# CERBERUS_2100_EasyEDA_Schematics.net
KiCad netlist of a schematic drawn in EasyEDA
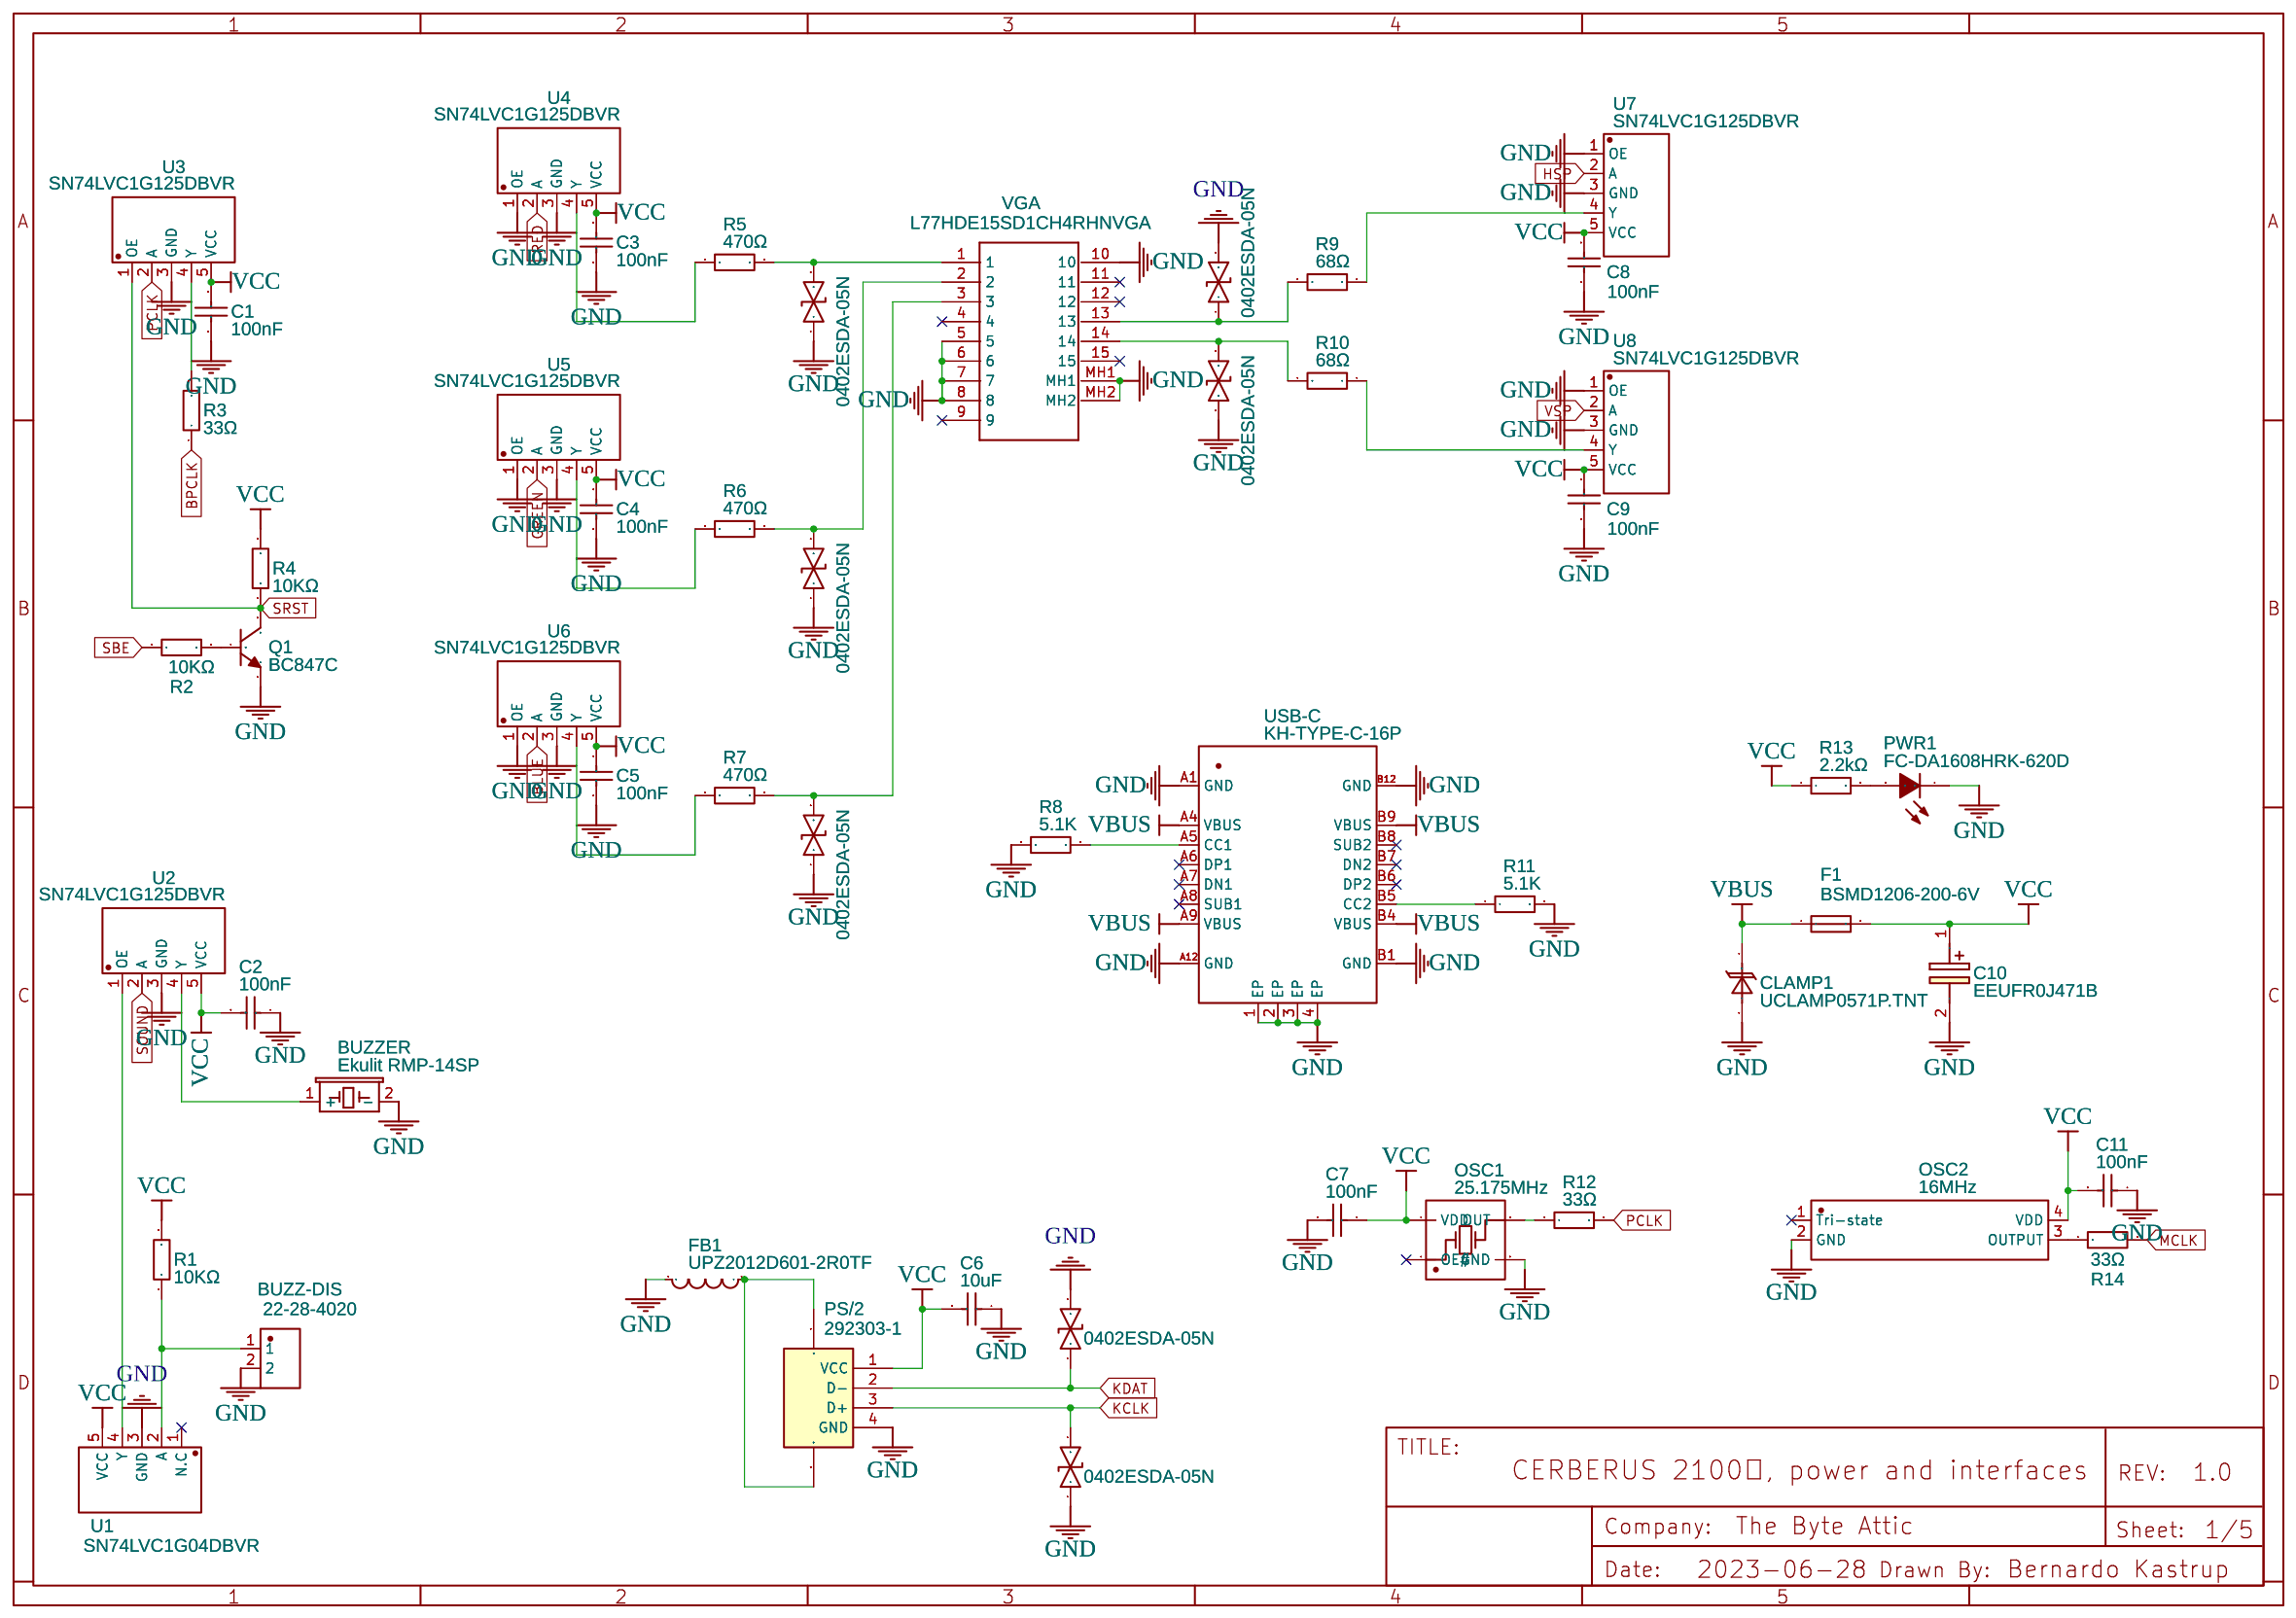
[diagram p0: PSU/IO]
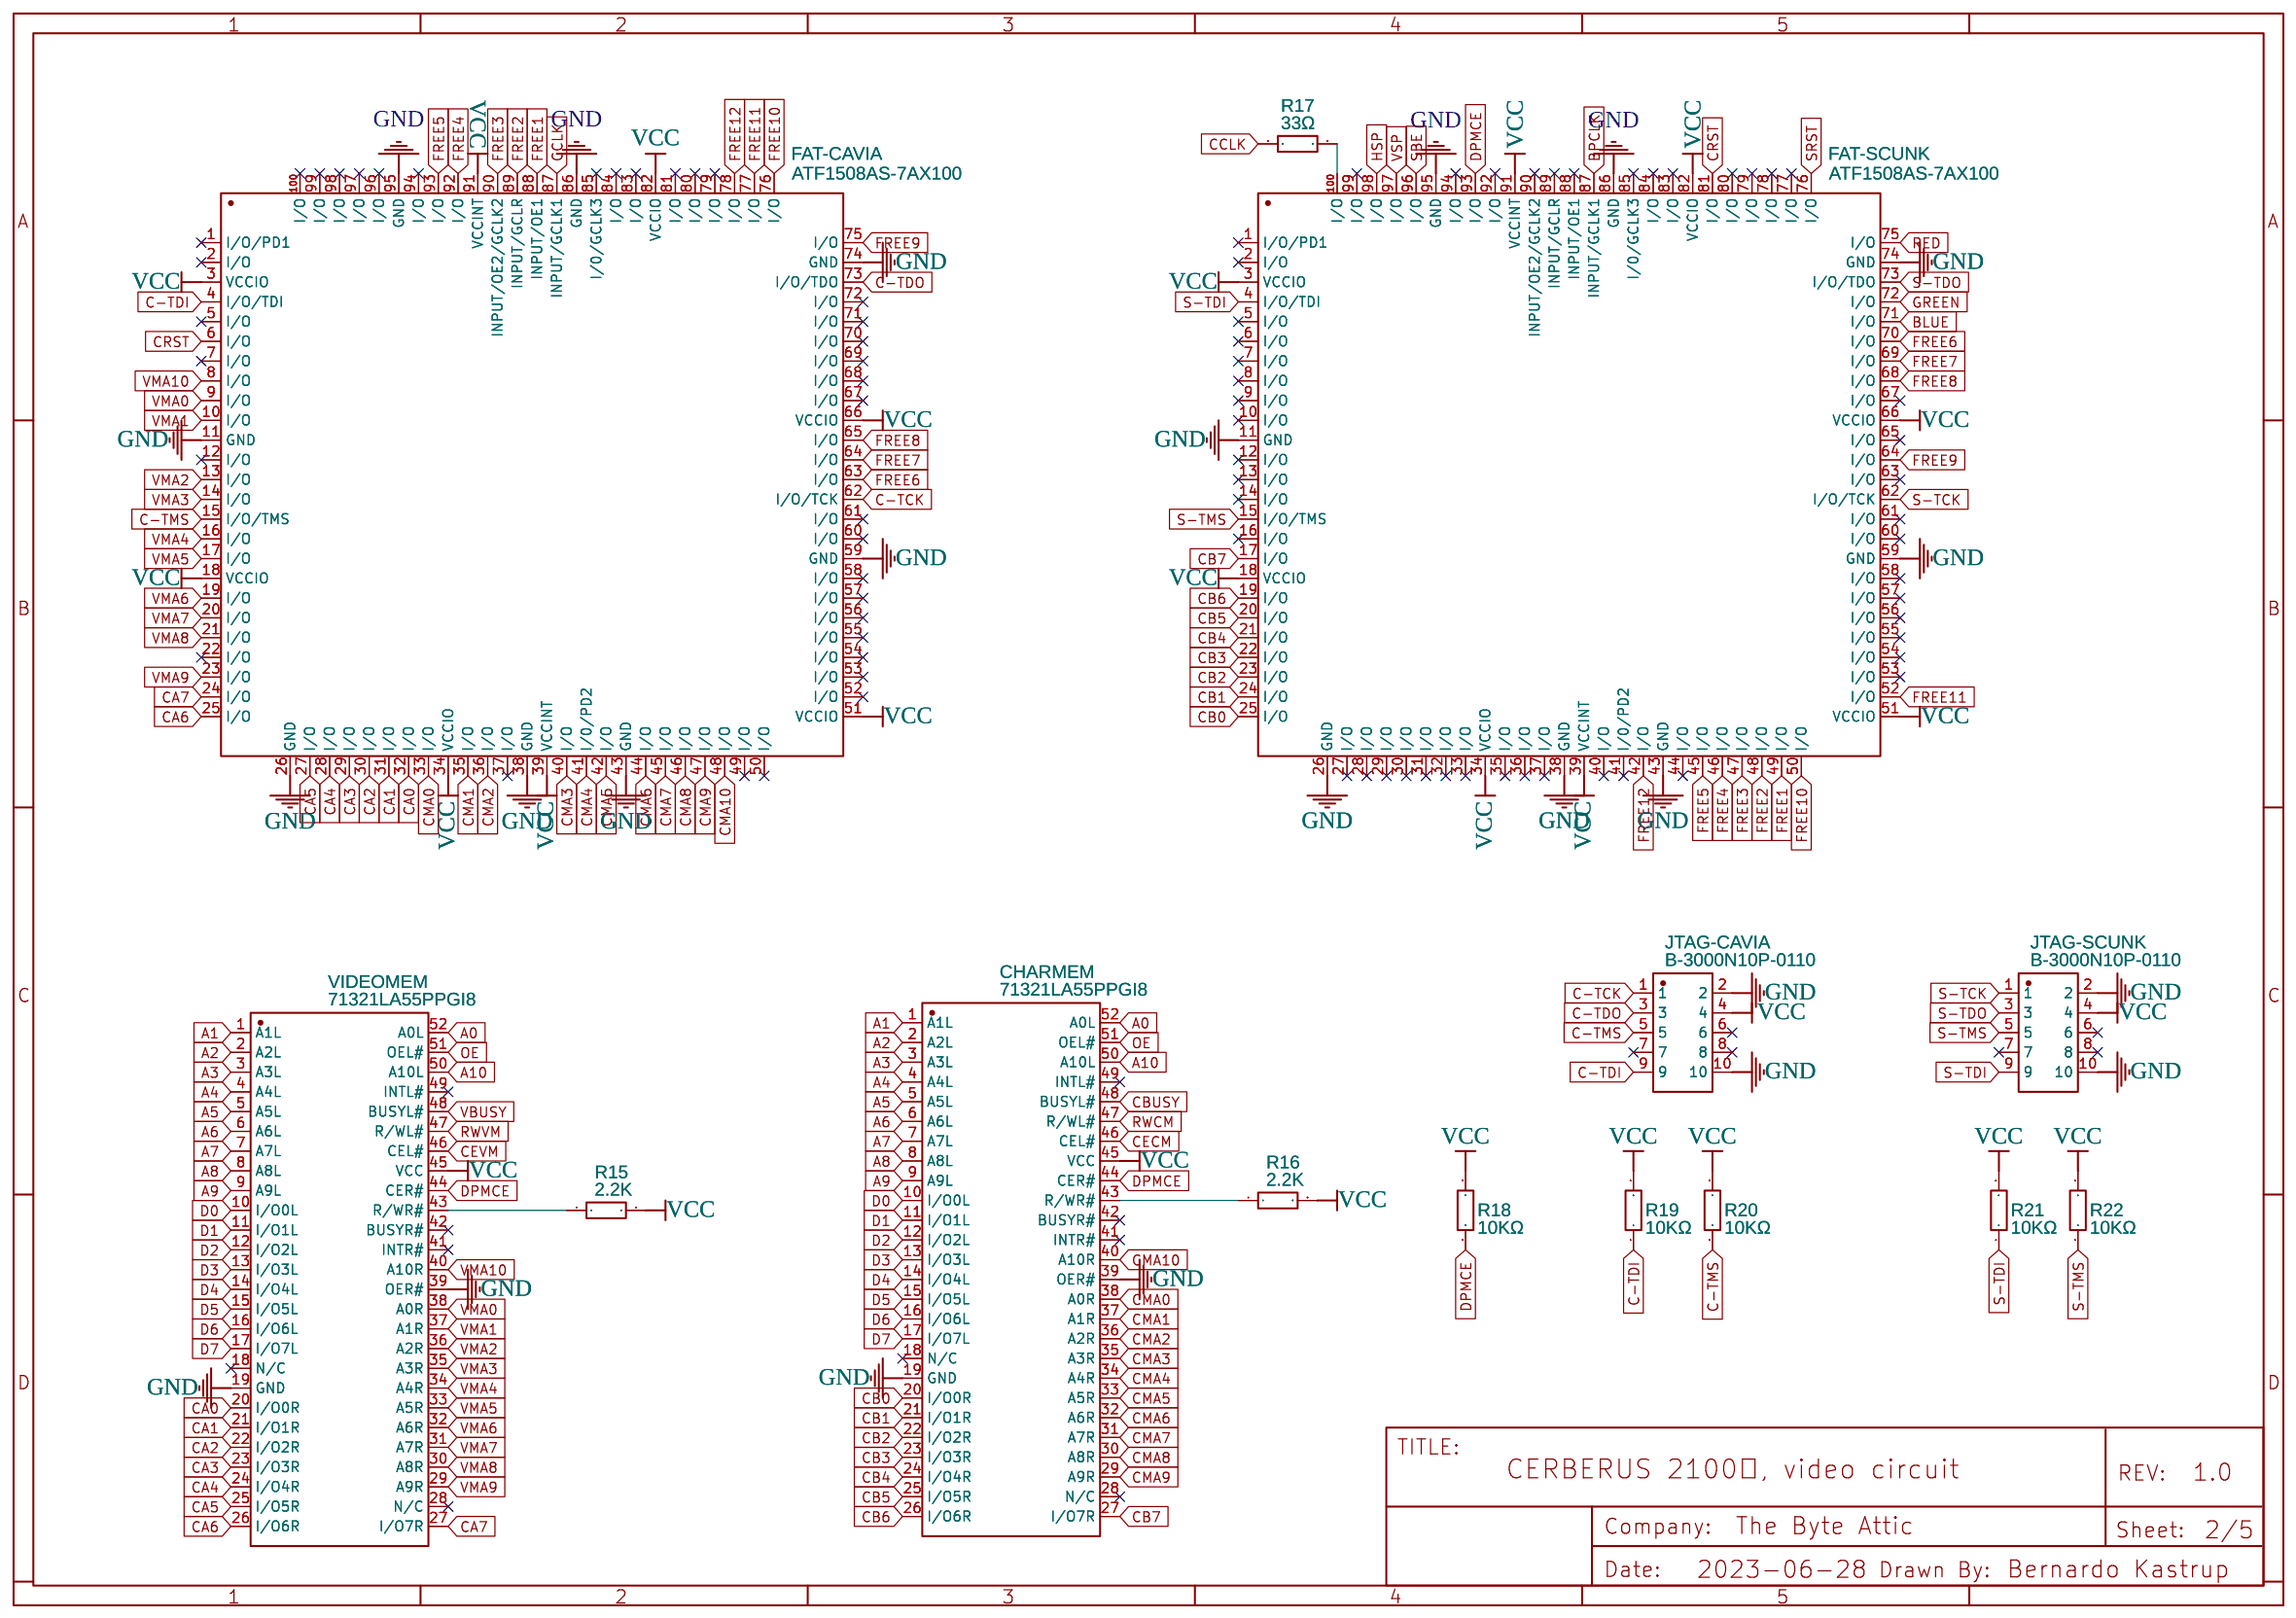
[diagram p1: VIDEO]
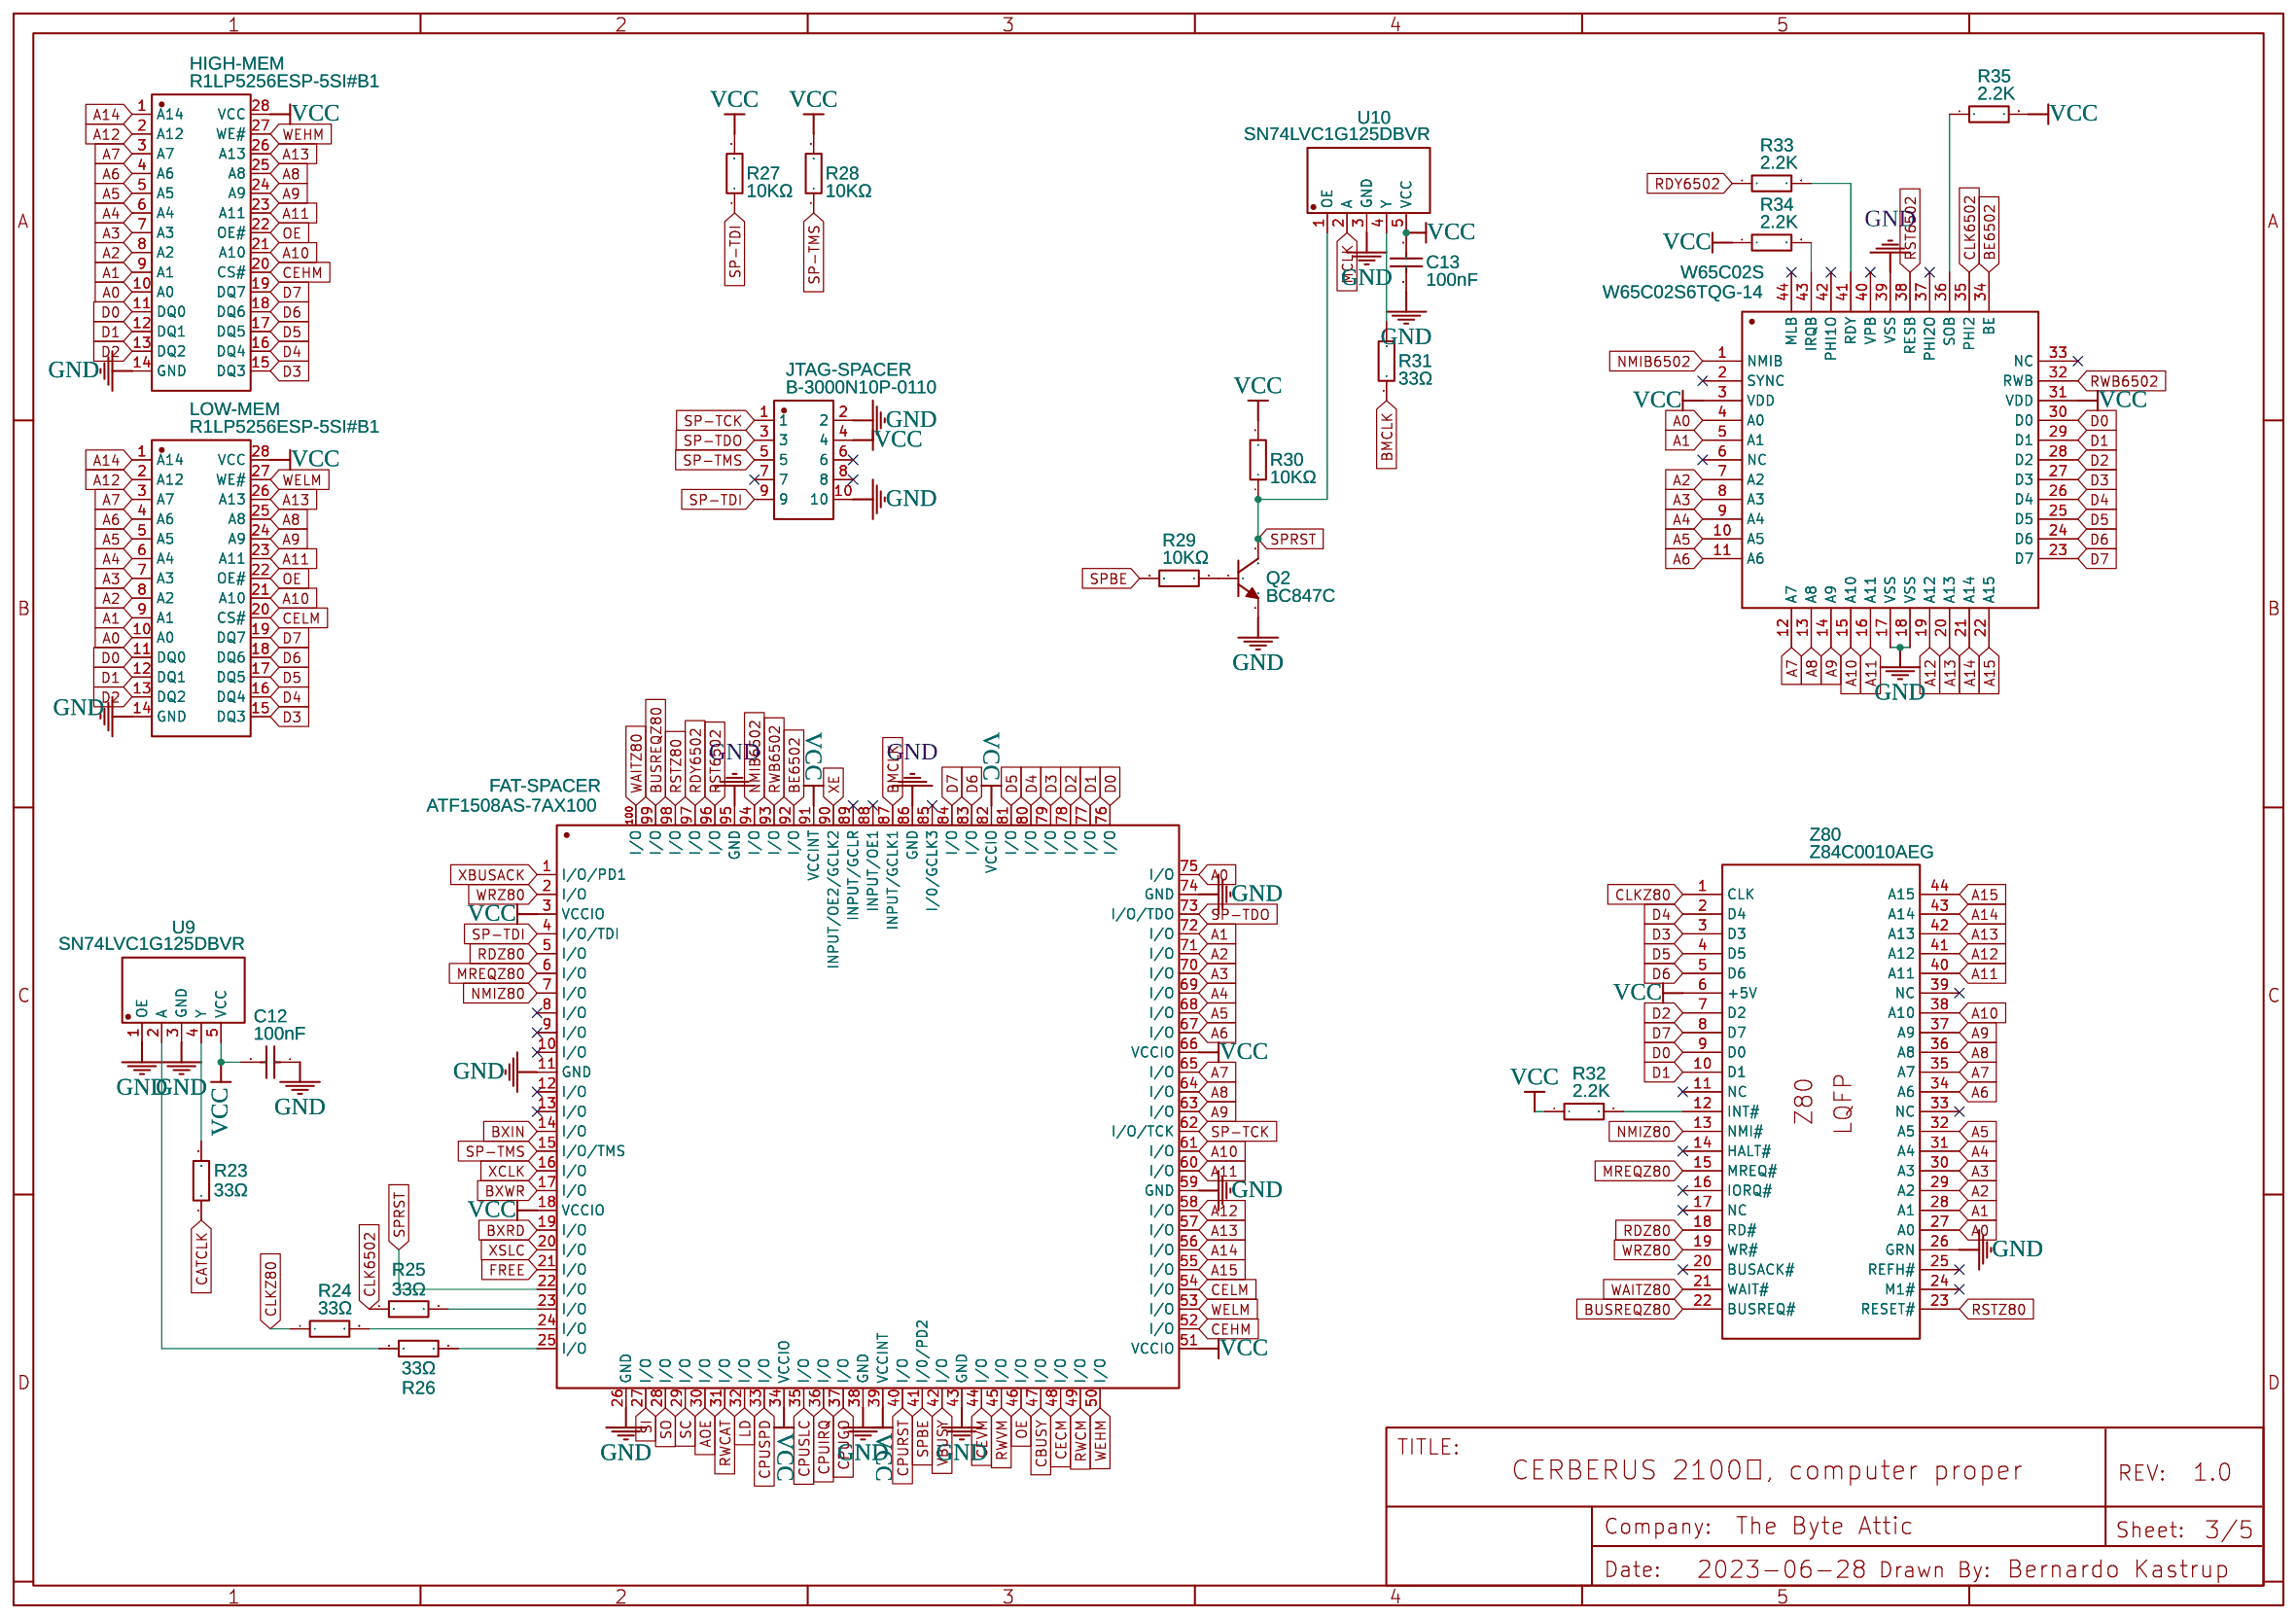
[diagram p2: COMP]
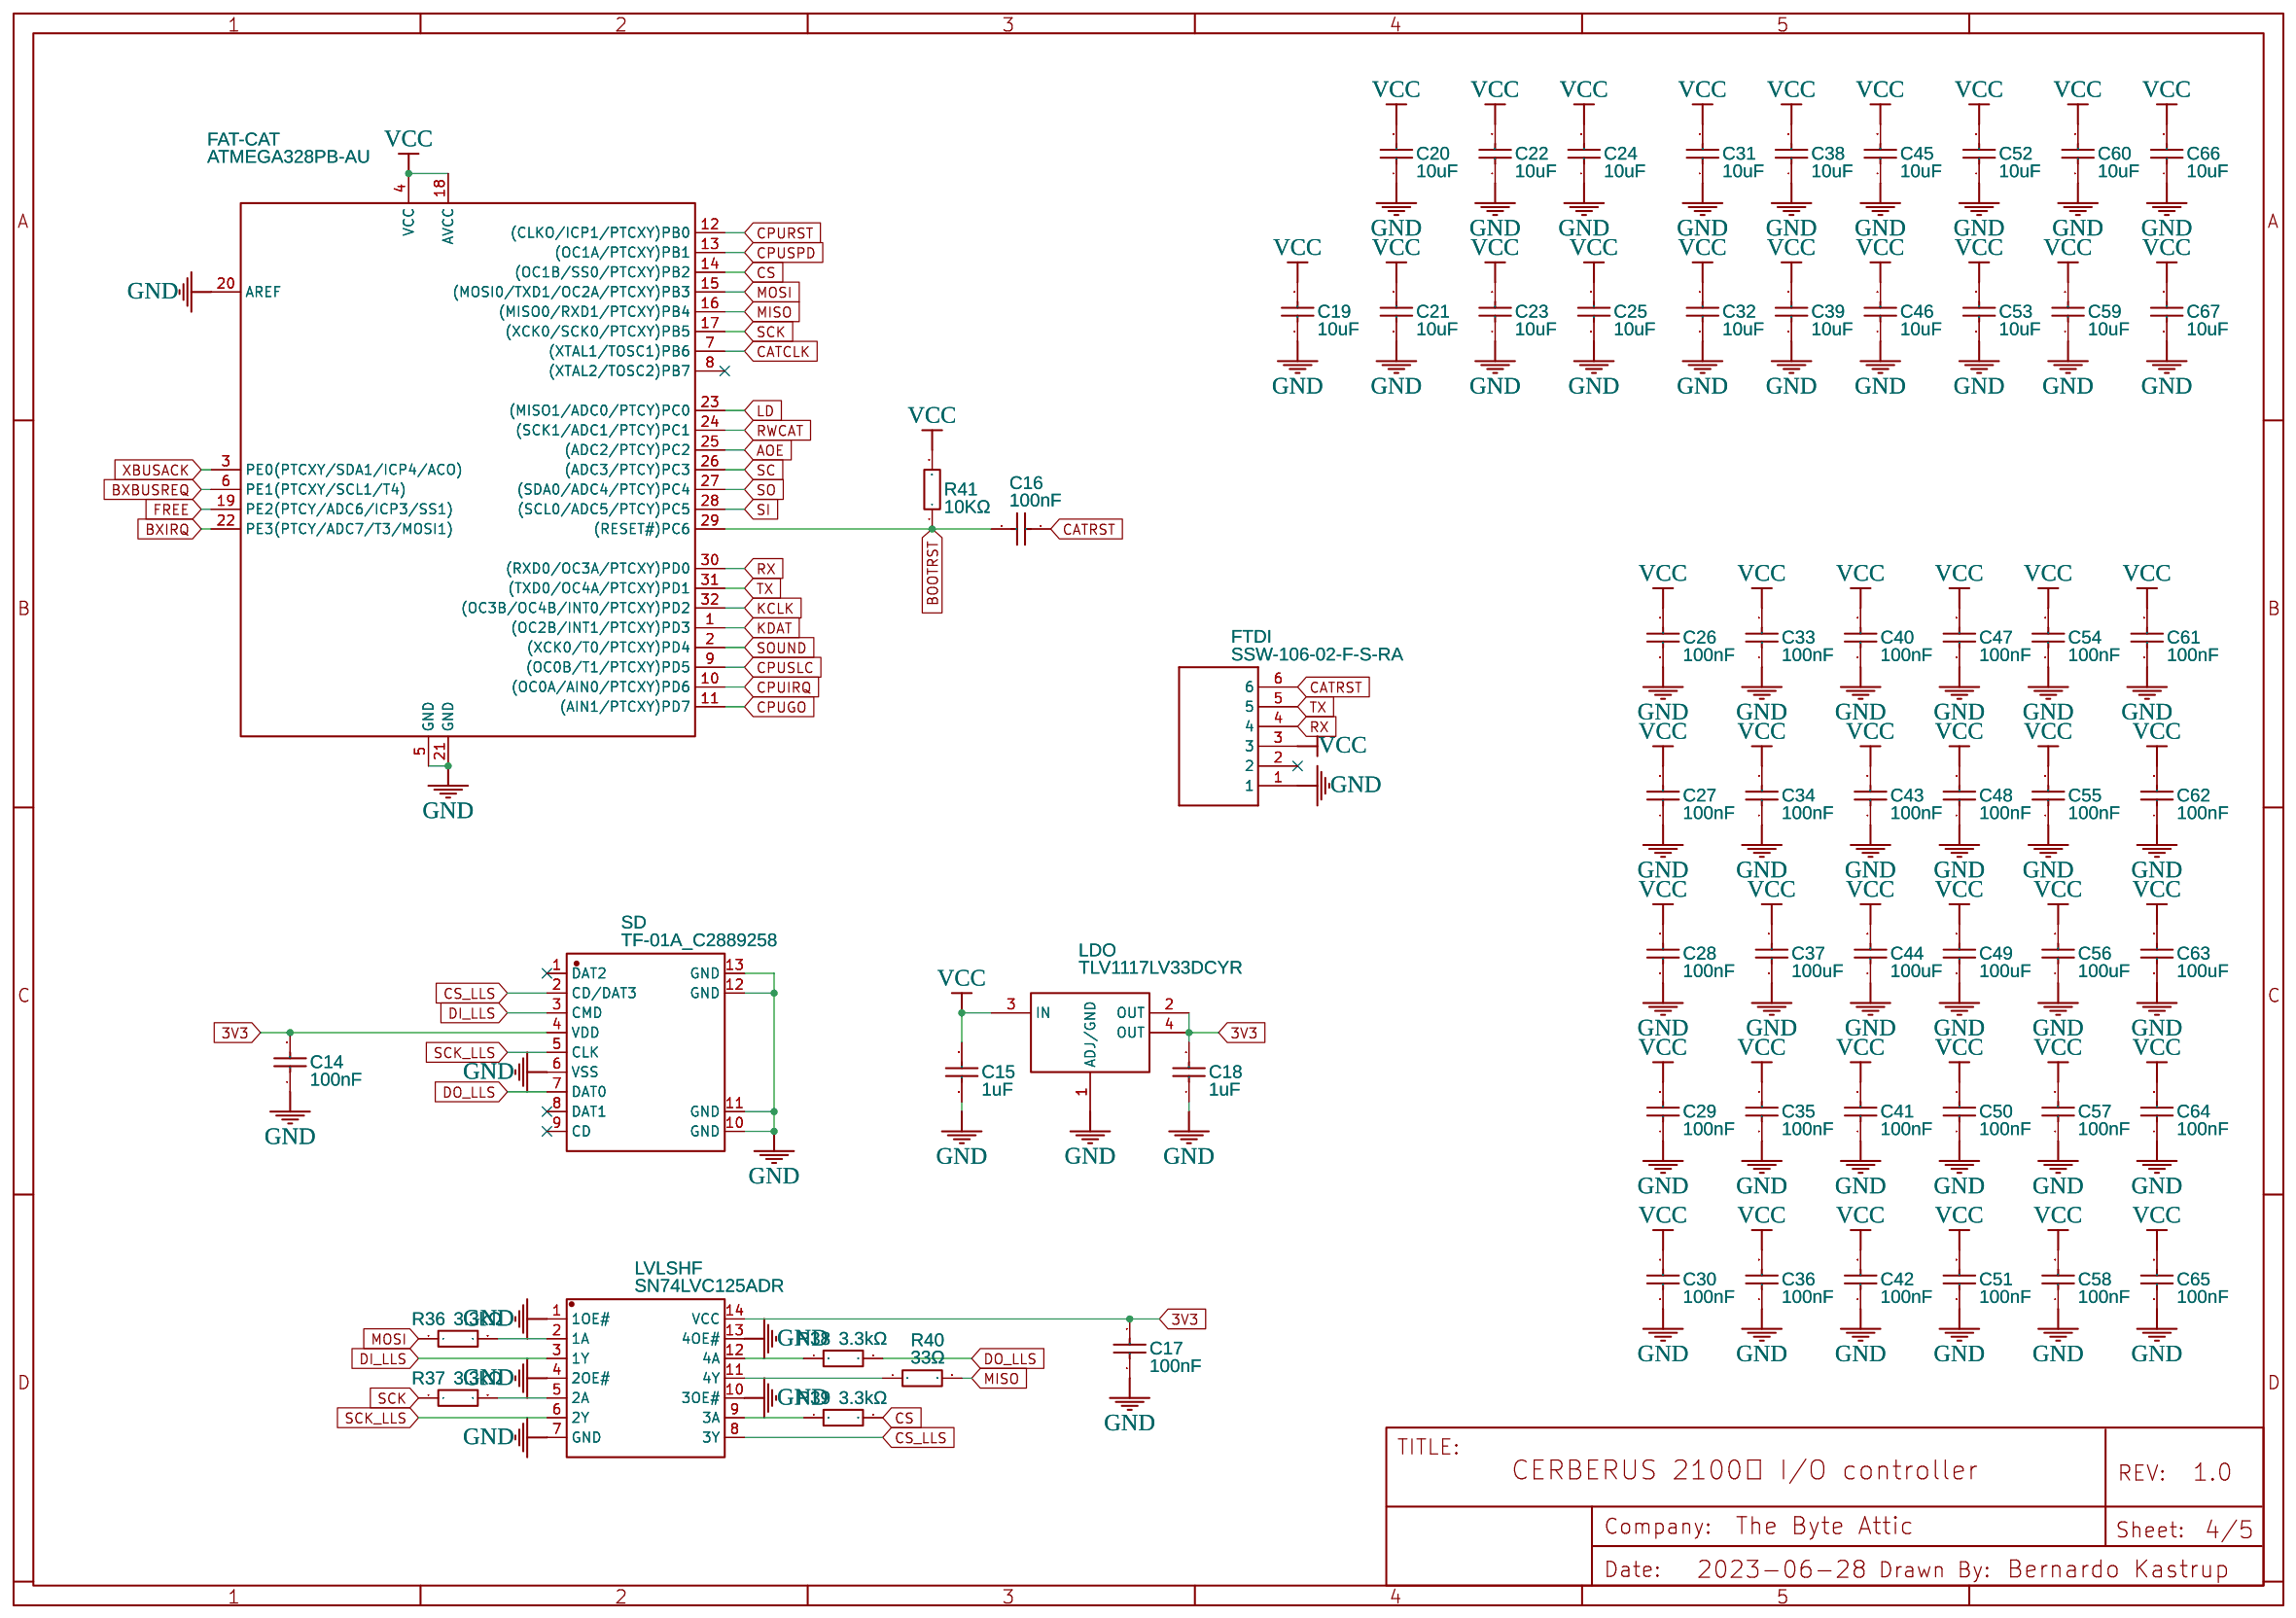
[diagram p3: IO CTRL]
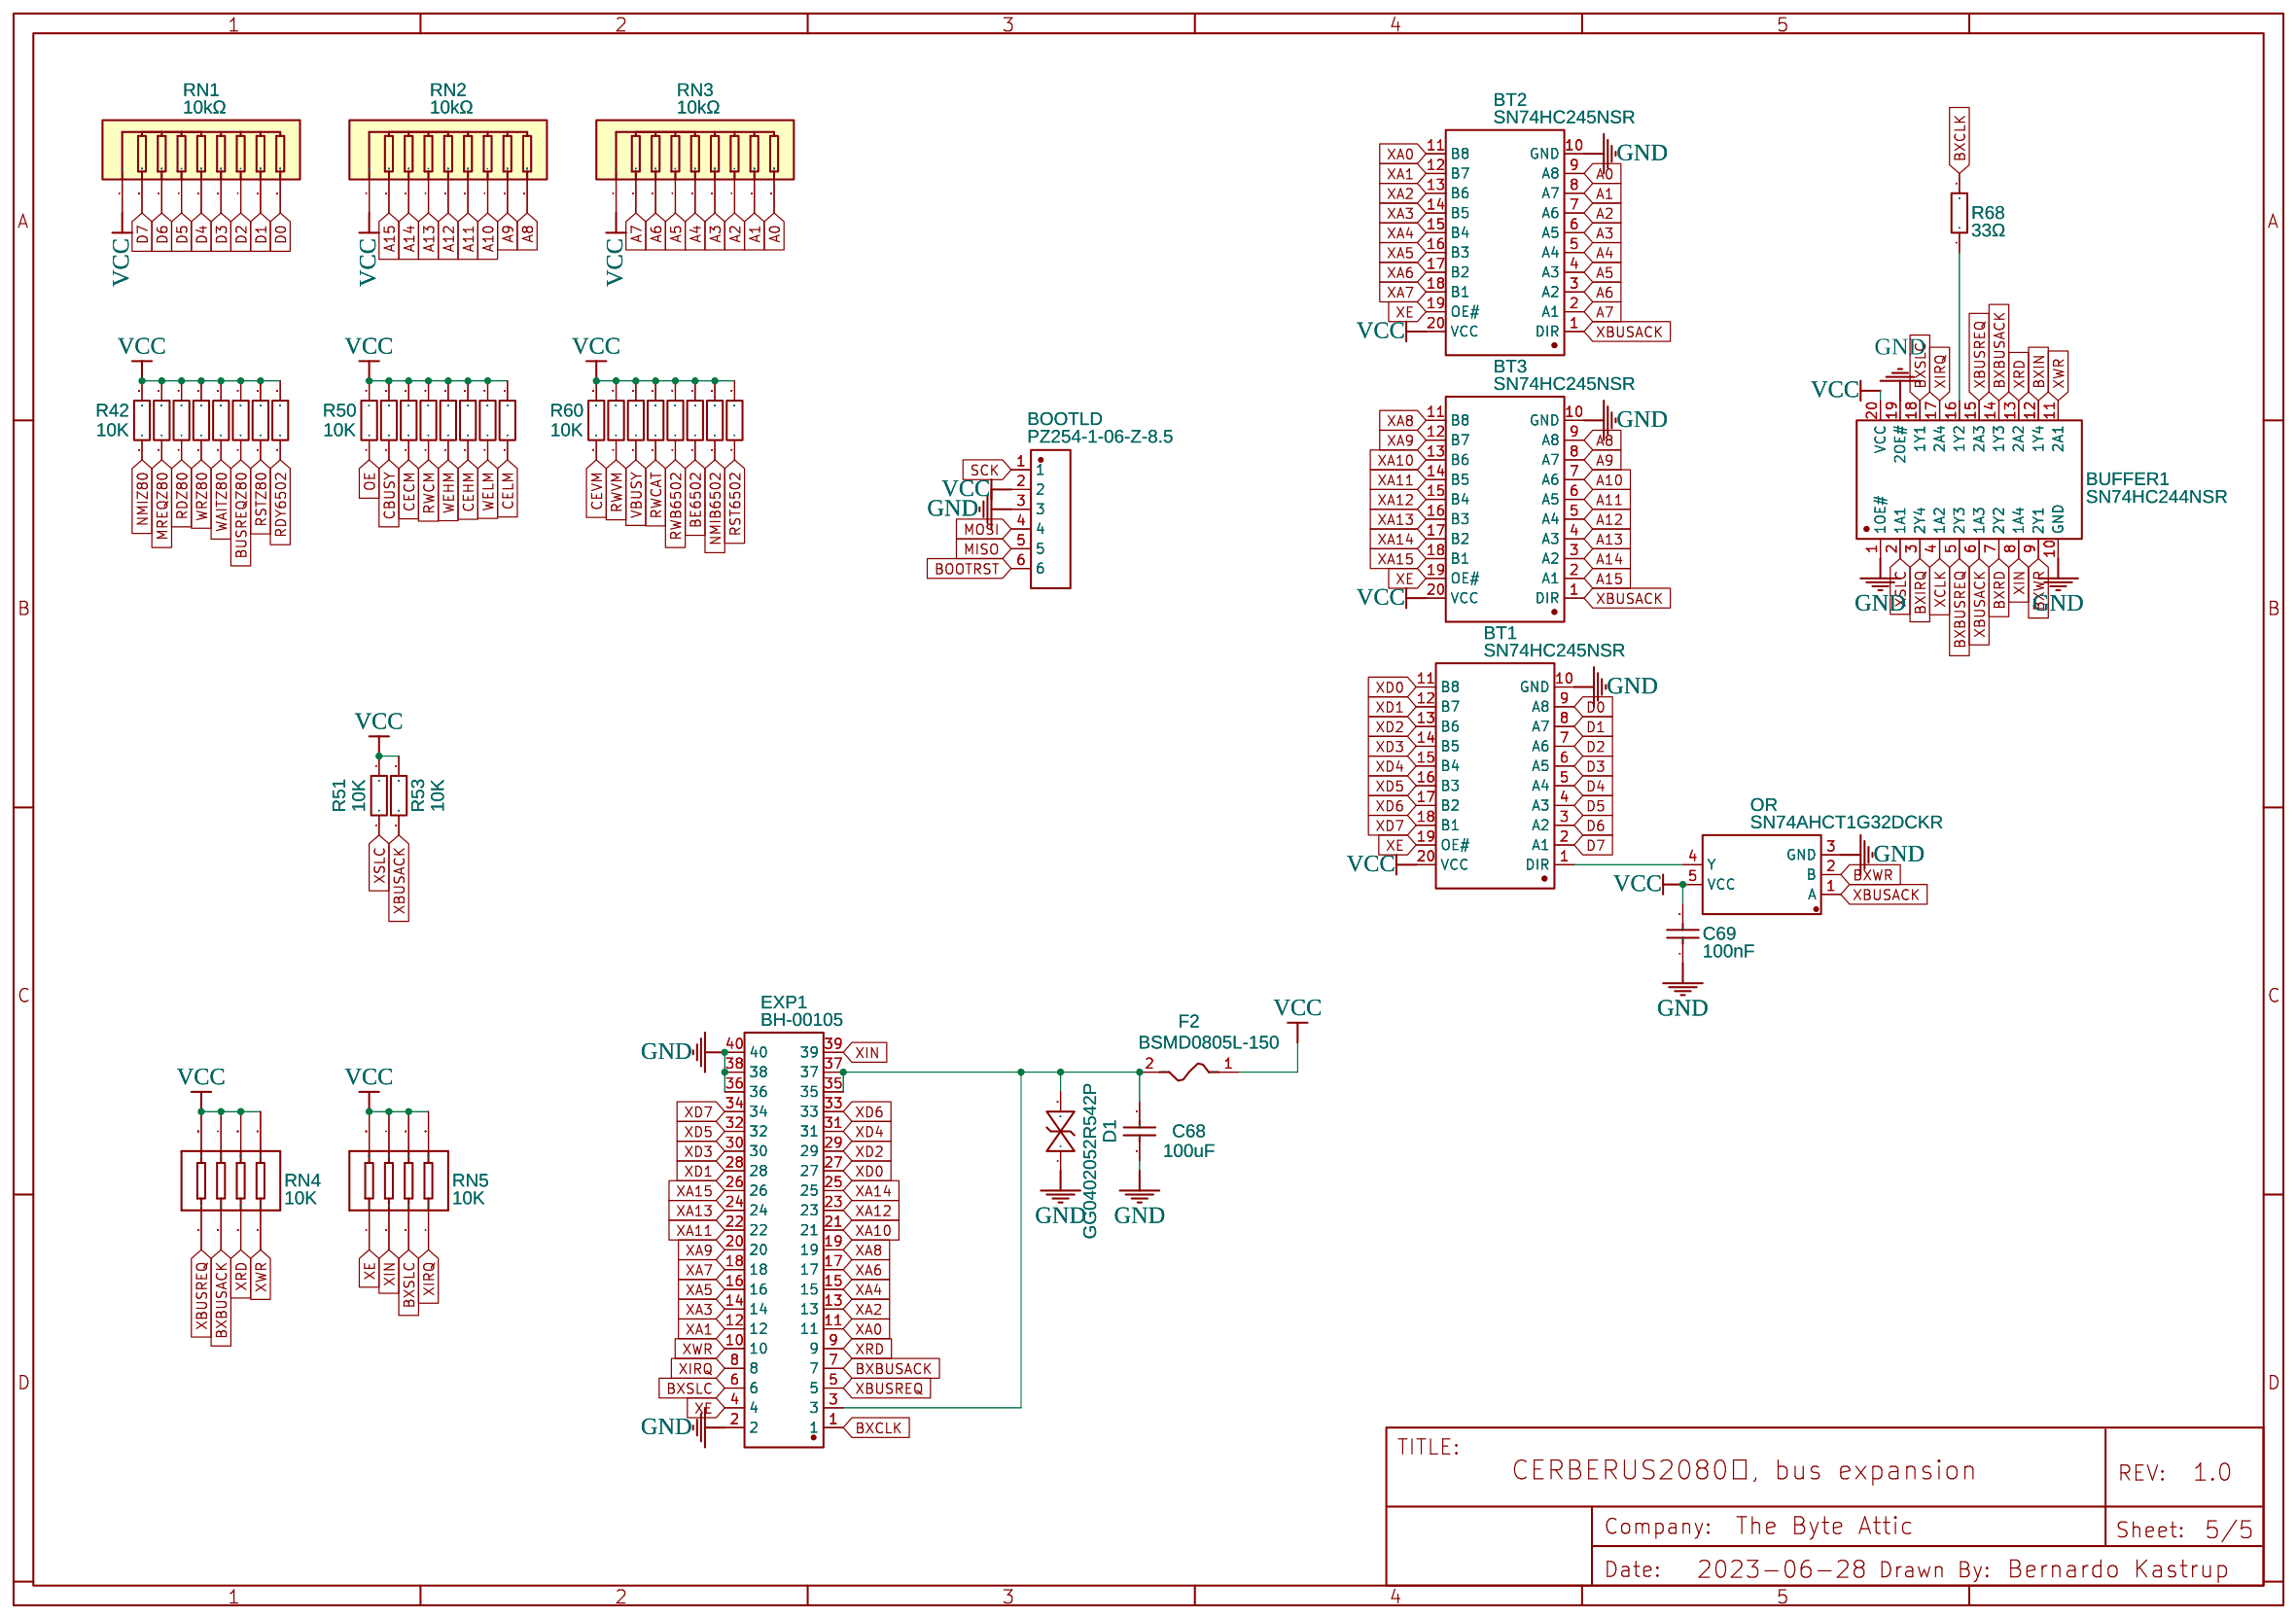
[diagram p4: EXP]

(export (version "E")
  (design (tool "Eeschema 10.0.6"))
  (components
    (comp (ref "BUZZ-DIS")
      (value "22-28-4020")
      (fields (field (name "BOM_Supplier Part") "C234182"))
      (libsource (lib "") (part "22-28-4020"))
    )
    (comp (ref "BUZZER")
      (value "Ekulit RMP-14SP")
      (fields (field (name "BOM_Supplier Part") "RMP-14SP"))
      (libsource (lib "") (part "BUZZER Ekulit RMP-14SP"))
    )
    (comp (ref "C1")
      (value "100nF")
      (fields
        (field (name "BOM_Manufacturer Part") "CL05B104KO5NNNC")
        (field (name "BOM_Supplier Part") "C1525")
      )
      (libsource (lib "") (part "CL05B104KO5NNNC_1"))
    )
    (comp (ref "C2")
      (value "100nF")
      (fields
        (field (name "BOM_Manufacturer Part") "CL05B104KO5NNNC")
        (field (name "BOM_Supplier Part") "C1525")
      )
      (libsource (lib "") (part "CL05B104KO5NNNC"))
    )
    (comp (ref "C3")
      (value "100nF")
      (fields
        (field (name "BOM_Manufacturer Part") "CL05B104KO5NNNC")
        (field (name "BOM_Supplier Part") "C1525")
      )
      (libsource (lib "") (part "CL05B104KO5NNNC_1"))
    )
    (comp (ref "C4")
      (value "100nF")
      (fields
        (field (name "BOM_Manufacturer Part") "CL05B104KO5NNNC")
        (field (name "BOM_Supplier Part") "C1525")
      )
      (libsource (lib "") (part "CL05B104KO5NNNC_1"))
    )
    (comp (ref "C5")
      (value "100nF")
      (fields
        (field (name "BOM_Manufacturer Part") "CL05B104KO5NNNC")
        (field (name "BOM_Supplier Part") "C1525")
      )
      (libsource (lib "") (part "CL05B104KO5NNNC_1"))
    )
    (comp (ref "C6")
      (value "10uF")
      (fields
        (field (name "BOM_Manufacturer Part") "CL05A106MQ5NUNC")
        (field (name "BOM_Supplier Part") "C15525")
      )
      (libsource (lib "") (part "CL05A106MQ5NUNC"))
    )
    (comp (ref "C7")
      (value "100nF")
      (fields
        (field (name "BOM_Manufacturer Part") "CL05B104KO5NNNC")
        (field (name "BOM_Supplier Part") "C1525")
      )
      (libsource (lib "") (part "CL05B104KO5NNNC"))
    )
    (comp (ref "C8")
      (value "100nF")
      (fields
        (field (name "BOM_Manufacturer Part") "CL05B104KO5NNNC")
        (field (name "BOM_Supplier Part") "C1525")
      )
      (libsource (lib "") (part "CL05B104KO5NNNC_1"))
    )
    (comp (ref "C9")
      (value "100nF")
      (fields
        (field (name "BOM_Manufacturer Part") "CL05B104KO5NNNC")
        (field (name "BOM_Supplier Part") "C1525")
      )
      (libsource (lib "") (part "CL05B104KO5NNNC_1"))
    )
    (comp (ref "C10")
      (value "EEUFR0J471B")
      (fields
        (field (name "BOM_Manufacturer Part") "EEU-FR0J471B")
        (field (name "BOM_Supplier Part") "667-EEU-FR0J471B")
      )
      (libsource (lib "") (part "EEUFR0J471B"))
    )
    (comp (ref "C11")
      (value "100nF")
      (fields
        (field (name "BOM_Manufacturer Part") "CL05B104KO5NNNC")
        (field (name "BOM_Supplier Part") "C1525")
      )
      (libsource (lib "") (part "CL05B104KO5NNNC"))
    )
    (comp (ref "CLAMP1")
      (value "UCLAMP0571P.TNT")
      (fields (field (name "BOM_Supplier Part") "C512387"))
      (libsource (lib "") (part "UCLAMP0571P.TNT"))
    )
    (comp (ref "ESD1")
      (value "0402ESDA-05N")
      (fields (field (name "BOM_Supplier Part") "C316049"))
      (libsource (lib "") (part "0402ESDA-05N"))
    )
    (comp (ref "ESD2")
      (value "0402ESDA-05N")
      (fields (field (name "BOM_Supplier Part") "C316049"))
      (libsource (lib "") (part "0402ESDA-05N"))
    )
    (comp (ref "ESD3")
      (value "0402ESDA-05N")
      (fields (field (name "BOM_Supplier Part") "C316049"))
      (libsource (lib "") (part "0402ESDA-05N"))
    )
    (comp (ref "ESD4")
      (value "0402ESDA-05N")
      (fields (field (name "BOM_Supplier Part") "C316049"))
      (libsource (lib "") (part "0402ESDA-05N"))
    )
    (comp (ref "ESD5")
      (value "0402ESDA-05N")
      (fields (field (name "BOM_Supplier Part") "C316049"))
      (libsource (lib "") (part "0402ESDA-05N"))
    )
    (comp (ref "ESD6")
      (value "0402ESDA-05N")
      (fields (field (name "BOM_Supplier Part") "C316049"))
      (libsource (lib "") (part "0402ESDA-05N"))
    )
    (comp (ref "ESD7")
      (value "0402ESDA-05N")
      (fields (field (name "BOM_Supplier Part") "C316049"))
      (libsource (lib "") (part "0402ESDA-05N"))
    )
    (comp (ref "F1")
      (value "BSMD1206-200-6V")
      (fields (field (name "BOM_Supplier Part") "C883134"))
      (libsource (lib "") (part "BSMD1206-200-6V"))
    )
    (comp (ref "FB1")
      (value "UPZ2012D601-2R0TF")
      (fields (field (name "BOM_Supplier Part") "C370578"))
      (libsource (lib "") (part "UPZ2012D601-2R0TF"))
    )
    (comp (ref "OSC1")
      (value "25.175MHz")
      (fields
        (field (name "BOM_Manufacturer Part") "S7D25.175000A20F30T")
        (field (name "BOM_Supplier Part") "C387038")
      )
      (libsource (lib "") (part "S7D25.175000A20F30T"))
    )
    (comp (ref "OSC2")
      (value "16MHz")
      (fields
        (field (name "BOM_Manufacturer Part") "S7D16.000000A20F30T")
        (field (name "BOM_Supplier Part") "C386991")
      )
      (libsource (lib "") (part "S7D16.000000A20F30T"))
    )
    (comp (ref "PS/2")
      (value "292303-1")
      (fields (field (name "BOM_Supplier Part") "C86461"))
      (libsource (lib "") (part "292303-1"))
    )
    (comp (ref "PWR1")
      (value "FC-DA1608HRK-620D")
      (fields (field (name "BOM_Manufacturer Part") "NCD0603R1") (field (name "BOM_Supplier Part") "C84263"))
      (libsource (lib "") (part "FC-DA1608HRK-620D"))
    )
    (comp (ref "Q1")
      (value "BC847C")
      (fields (field (name "BOM_Supplier Part") "C181141"))
      (libsource (lib "") (part "BC847C"))
    )
    (comp (ref "R1")
      (value "10KΩ")
      (fields
        (field (name "BOM_Manufacturer Part") "RC0402FR-0710KL")
        (field (name "BOM_Supplier Part") "C60490")
      )
      (libsource (lib "") (part "RC0402FR-0710KL"))
    )
    (comp (ref "R2")
      (value "10KΩ")
      (fields
        (field (name "BOM_Manufacturer Part") "RC0402FR-0710KL")
        (field (name "BOM_Supplier Part") "C60490")
      )
      (libsource (lib "") (part "RC0402FR-0710KL_1"))
    )
    (comp (ref "R3")
      (value "33Ω")
      (fields
        (field (name "BOM_Manufacturer Part") "0402WGF330JTCE")
        (field (name "BOM_Supplier Part") "C25105")
      )
      (libsource (lib "") (part "0402WGF330JTCE_1"))
    )
    (comp (ref "R4")
      (value "10KΩ")
      (fields
        (field (name "BOM_Manufacturer Part") "RC0402FR-0710KL")
        (field (name "BOM_Supplier Part") "C60490")
      )
      (libsource (lib "") (part "RC0402FR-0710KL"))
    )
    (comp (ref "R5")
      (value "470Ω")
      (fields
        (field (name "BOM_Manufacturer Part") "0603WAF4700T5E")
        (field (name "BOM_Supplier Part") "C23179")
      )
      (libsource (lib "") (part "0603WAF4700T5E"))
    )
    (comp (ref "R6")
      (value "470Ω")
      (fields
        (field (name "BOM_Manufacturer Part") "0603WAF4700T5E")
        (field (name "BOM_Supplier Part") "C23179")
      )
      (libsource (lib "") (part "0603WAF4700T5E"))
    )
    (comp (ref "R7")
      (value "470Ω")
      (fields
        (field (name "BOM_Manufacturer Part") "0603WAF4700T5E")
        (field (name "BOM_Supplier Part") "C23179")
      )
      (libsource (lib "") (part "0603WAF4700T5E"))
    )
    (comp (ref "R8")
      (value "5.1K")
      (fields
        (field (name "BOM_Manufacturer Part") "RC0603FR-075K1L")
        (field (name "BOM_Supplier Part") "C105580")
      )
      (libsource (lib "") (part "RC0603FR-075K1L"))
    )
    (comp (ref "R9")
      (value "68Ω")
      (fields
        (field (name "BOM_Manufacturer Part") "RC0402FR-0768RL")
        (field (name "BOM_Supplier Part") "C163455")
      )
      (libsource (lib "") (part "RC0402FR-0768RL"))
    )
    (comp (ref "R10")
      (value "68Ω")
      (fields
        (field (name "BOM_Manufacturer Part") "RC0402FR-0768RL")
        (field (name "BOM_Supplier Part") "C163455")
      )
      (libsource (lib "") (part "RC0402FR-0768RL"))
    )
    (comp (ref "R11")
      (value "5.1K")
      (fields
        (field (name "BOM_Manufacturer Part") "RC0603FR-075K1L")
        (field (name "BOM_Supplier Part") "C105580")
      )
      (libsource (lib "") (part "RC0603FR-075K1L"))
    )
    (comp (ref "R12")
      (value "33Ω")
      (fields
        (field (name "BOM_Manufacturer Part") "0402WGF330JTCE")
        (field (name "BOM_Supplier Part") "C25105")
      )
      (libsource (lib "") (part "0402WGF330JTCE"))
    )
    (comp (ref "R13")
      (value "2.2kΩ")
      (fields
        (field (name "BOM_Manufacturer Part") "0603WAF2201T5E")
        (field (name "BOM_Supplier Part") "C4190")
      )
      (libsource (lib "") (part "0603WAF2201T5E"))
    )
    (comp (ref "R14")
      (value "33Ω")
      (fields
        (field (name "BOM_Manufacturer Part") "0402WGF330JTCE")
        (field (name "BOM_Supplier Part") "C25105")
      )
      (libsource (lib "") (part "0402WGF330JTCE"))
    )
    (comp (ref "U1")
      (value "SN74LVC1G04DBVR")
      (fields (field (name "BOM_Supplier Part") "C7827"))
      (libsource (lib "") (part "SN74LVC1G04DBVR"))
    )
    (comp (ref "U2")
      (value "SN74LVC1G125DBVR")
      (fields (field (name "BOM_Supplier Part") "C23654"))
      (libsource (lib "") (part "SN74LVC1G125DBVR"))
    )
    (comp (ref "U3")
      (value "SN74LVC1G125DBVR")
      (fields (field (name "BOM_Supplier Part") "C23654"))
      (libsource (lib "") (part "SN74LVC1G125DBVR"))
    )
    (comp (ref "U4")
      (value "SN74LVC1G125DBVR")
      (fields (field (name "BOM_Supplier Part") "C23654"))
      (libsource (lib "") (part "SN74LVC1G125DBVR"))
    )
    (comp (ref "U5")
      (value "SN74LVC1G125DBVR")
      (fields (field (name "BOM_Supplier Part") "C23654"))
      (libsource (lib "") (part "SN74LVC1G125DBVR"))
    )
    (comp (ref "U6")
      (value "SN74LVC1G125DBVR")
      (fields (field (name "BOM_Supplier Part") "C23654"))
      (libsource (lib "") (part "SN74LVC1G125DBVR"))
    )
    (comp (ref "U7")
      (value "SN74LVC1G125DBVR")
      (fields (field (name "BOM_Supplier Part") "C23654"))
      (libsource (lib "") (part "SN74LVC1G125DBVR_1"))
    )
    (comp (ref "U8")
      (value "SN74LVC1G125DBVR")
      (fields (field (name "BOM_Supplier Part") "C23654"))
      (libsource (lib "") (part "SN74LVC1G125DBVR_1"))
    )
    (comp (ref "USB-C")
      (value "KH-TYPE-C-16P")
      (fields (field (name "BOM_Supplier Part") "C709357"))
      (libsource (lib "") (part "KH-TYPE-C-16P"))
    )
    (comp (ref "VGA") (value "L77HDE15SD1CH4RHNVGA") (libsource (lib "") (part "L77HDE15SD1CH4RHNVGA")))
    (comp (ref "CHARMEM")
      (value "71321LA55PPGI8")
      (fields (field (name "BOM_Supplier Part") "C1511714"))
      (libsource (lib "") (part "71321LA55PPGI8"))
    )
    (comp (ref "FAT-CAVIA")
      (value "ATF1508AS-7AX100")
      (fields (field (name "BOM_Supplier Part") "556-AF1508AS7AX100"))
      (libsource (lib "") (part "ATF1508AS-10AU100"))
    )
    (comp (ref "FAT-SCUNK")
      (value "ATF1508AS-7AX100")
      (fields (field (name "BOM_Supplier Part") "556-AF1508AS7AX100"))
      (libsource (lib "") (part "ATF1508AS-10AU100_1"))
    )
    (comp (ref "JTAG-CAVIA")
      (value "B-3000N10P-0110")
      (fields (field (name "BOM_Supplier Part") "C383605"))
      (libsource (lib "") (part "B-3000N10P-0110_1"))
    )
    (comp (ref "JTAG-SCUNK")
      (value "B-3000N10P-0110")
      (fields (field (name "BOM_Supplier Part") "C383605"))
      (libsource (lib "") (part "B-3000N10P-0110"))
    )
    (comp (ref "R15")
      (value "2.2K")
      (fields
        (field (name "BOM_Manufacturer Part") "RC0402FR-072K2L")
        (field (name "BOM_Supplier Part") "C114762")
      )
      (libsource (lib "") (part "RC0402FR-072K2L"))
    )
    (comp (ref "R16")
      (value "2.2K")
      (fields
        (field (name "BOM_Manufacturer Part") "RC0402FR-072K2L")
        (field (name "BOM_Supplier Part") "C114762")
      )
      (libsource (lib "") (part "RC0402FR-072K2L"))
    )
    (comp (ref "R17")
      (value "33Ω")
      (fields
        (field (name "BOM_Manufacturer Part") "0402WGF330JTCE")
        (field (name "BOM_Supplier Part") "C25105")
      )
      (libsource (lib "") (part "0402WGF330JTCE"))
    )
    (comp (ref "R18")
      (value "10KΩ")
      (fields
        (field (name "BOM_Manufacturer Part") "RC0402FR-0710KL")
        (field (name "BOM_Supplier Part") "C60490")
      )
      (libsource (lib "") (part "RC0402FR-0710KL"))
    )
    (comp (ref "R19")
      (value "10KΩ")
      (fields
        (field (name "BOM_Manufacturer Part") "RC0402FR-0710KL")
        (field (name "BOM_Supplier Part") "C60490")
      )
      (libsource (lib "") (part "RC0402FR-0710KL"))
    )
    (comp (ref "R20")
      (value "10KΩ")
      (fields
        (field (name "BOM_Manufacturer Part") "RC0402FR-0710KL")
        (field (name "BOM_Supplier Part") "C60490")
      )
      (libsource (lib "") (part "RC0402FR-0710KL"))
    )
    (comp (ref "R21")
      (value "10KΩ")
      (fields
        (field (name "BOM_Manufacturer Part") "RC0402FR-0710KL")
        (field (name "BOM_Supplier Part") "C60490")
      )
      (libsource (lib "") (part "RC0402FR-0710KL"))
    )
    (comp (ref "R22")
      (value "10KΩ")
      (fields
        (field (name "BOM_Manufacturer Part") "RC0402FR-0710KL")
        (field (name "BOM_Supplier Part") "C60490")
      )
      (libsource (lib "") (part "RC0402FR-0710KL"))
    )
    (comp (ref "VIDEOMEM")
      (value "71321LA55PPGI8")
      (fields (field (name "BOM_Supplier Part") "C1511714"))
      (libsource (lib "") (part "71321LA55PPGI8_1"))
    )
    (comp (ref "C12")
      (value "100nF")
      (fields
        (field (name "BOM_Manufacturer Part") "CL05B104KO5NNNC")
        (field (name "BOM_Supplier Part") "C1525")
      )
      (libsource (lib "") (part "CL05B104KO5NNNC"))
    )
    (comp (ref "C13")
      (value "100nF")
      (fields
        (field (name "BOM_Manufacturer Part") "CL05B104KO5NNNC")
        (field (name "BOM_Supplier Part") "C1525")
      )
      (libsource (lib "") (part "CL05B104KO5NNNC_1"))
    )
    (comp (ref "FAT-SPACER")
      (value "ATF1508AS-7AX100")
      (fields (field (name "BOM_Supplier Part") "556-AF1508AS7AX100"))
      (libsource (lib "") (part "ATF1508AS-10AU100"))
    )
    (comp (ref "HIGH-MEM")
      (value "R1LP5256ESP-5SI#B1")
      (fields (field (name "BOM_Supplier Part") "C1136813"))
      (libsource (lib "") (part "R1LP5256ESP-5SI#B1"))
    )
    (comp (ref "JTAG-SPACER")
      (value "B-3000N10P-0110")
      (fields (field (name "BOM_Supplier Part") "C383605"))
      (libsource (lib "") (part "B-3000N10P-0110"))
    )
    (comp (ref "LOW-MEM")
      (value "R1LP5256ESP-5SI#B1")
      (fields (field (name "BOM_Supplier Part") "C1136813"))
      (libsource (lib "") (part "R1LP5256ESP-5SI#B1_1"))
    )
    (comp (ref "Q2")
      (value "BC847C")
      (fields (field (name "BOM_Supplier Part") "C181141"))
      (libsource (lib "") (part "BC847C"))
    )
    (comp (ref "R23")
      (value "33Ω")
      (fields
        (field (name "BOM_Manufacturer Part") "0402WGF330JTCE")
        (field (name "BOM_Supplier Part") "C25105")
      )
      (libsource (lib "") (part "0402WGF330JTCE_1"))
    )
    (comp (ref "R24")
      (value "33Ω")
      (fields
        (field (name "BOM_Manufacturer Part") "0402WGF330JTCE")
        (field (name "BOM_Supplier Part") "C25105")
      )
      (libsource (lib "") (part "0402WGF330JTCE"))
    )
    (comp (ref "R25")
      (value "33Ω")
      (fields
        (field (name "BOM_Manufacturer Part") "0402WGF330JTCE")
        (field (name "BOM_Supplier Part") "C25105")
      )
      (libsource (lib "") (part "0402WGF330JTCE"))
    )
    (comp (ref "R26")
      (value "33Ω")
      (fields
        (field (name "BOM_Manufacturer Part") "0402WGF330JTCE")
        (field (name "BOM_Supplier Part") "C25105")
      )
      (libsource (lib "") (part "0402WGF330JTCE"))
    )
    (comp (ref "R27")
      (value "10KΩ")
      (fields
        (field (name "BOM_Manufacturer Part") "RC0402FR-0710KL")
        (field (name "BOM_Supplier Part") "C60490")
      )
      (libsource (lib "") (part "RC0402FR-0710KL"))
    )
    (comp (ref "R28")
      (value "10KΩ")
      (fields
        (field (name "BOM_Manufacturer Part") "RC0402FR-0710KL")
        (field (name "BOM_Supplier Part") "C60490")
      )
      (libsource (lib "") (part "RC0402FR-0710KL"))
    )
    (comp (ref "R29")
      (value "10KΩ")
      (fields
        (field (name "BOM_Manufacturer Part") "RC0402FR-0710KL")
        (field (name "BOM_Supplier Part") "C60490")
      )
      (libsource (lib "") (part "RC0402FR-0710KL_1"))
    )
    (comp (ref "R30")
      (value "10KΩ")
      (fields
        (field (name "BOM_Manufacturer Part") "RC0402FR-0710KL")
        (field (name "BOM_Supplier Part") "C60490")
      )
      (libsource (lib "") (part "RC0402FR-0710KL"))
    )
    (comp (ref "R31")
      (value "33Ω")
      (fields
        (field (name "BOM_Manufacturer Part") "0402WGF330JTCE")
        (field (name "BOM_Supplier Part") "C25105")
      )
      (libsource (lib "") (part "0402WGF330JTCE_1"))
    )
    (comp (ref "R32")
      (value "2.2K")
      (fields
        (field (name "BOM_Manufacturer Part") "RC0402FR-072K2L")
        (field (name "BOM_Supplier Part") "C114762")
      )
      (libsource (lib "") (part "RC0402FR-072K2L"))
    )
    (comp (ref "R33")
      (value "2.2K")
      (fields
        (field (name "BOM_Manufacturer Part") "RC0402FR-072K2L")
        (field (name "BOM_Supplier Part") "C114762")
      )
      (libsource (lib "") (part "RC0402FR-072K2L"))
    )
    (comp (ref "R34")
      (value "2.2K")
      (fields
        (field (name "BOM_Manufacturer Part") "RC0402FR-072K2L")
        (field (name "BOM_Supplier Part") "C114762")
      )
      (libsource (lib "") (part "RC0402FR-072K2L"))
    )
    (comp (ref "R35")
      (value "2.2K")
      (fields
        (field (name "BOM_Manufacturer Part") "RC0402FR-072K2L")
        (field (name "BOM_Supplier Part") "C114762")
      )
      (libsource (lib "") (part "RC0402FR-072K2L"))
    )
    (comp (ref "U9")
      (value "SN74LVC1G125DBVR")
      (fields (field (name "BOM_Supplier Part") "C23654"))
      (libsource (lib "") (part "SN74LVC1G125DBVR"))
    )
    (comp (ref "U10")
      (value "SN74LVC1G125DBVR")
      (fields (field (name "BOM_Supplier Part") "C23654"))
      (libsource (lib "") (part "SN74LVC1G125DBVR"))
    )
    (comp (ref "W65C02S")
      (value "W65C02S6TQG-14")
      (fields (field (name "BOM_Supplier Part") "955-W65C02S6TQG-14"))
      (libsource (lib "") (part "W65C02S6TQG-14"))
    )
    (comp (ref "Z80")
      (value "Z84C0010AEG")
      (fields (field (name "BOM_Supplier Part") "692-Z84C0010AEG"))
      (libsource (lib "") (part "Z80 LQFP 44"))
    )
    (comp (ref "C14")
      (value "100nF")
      (fields
        (field (name "BOM_Manufacturer Part") "CL05B104KO5NNNC")
        (field (name "BOM_Supplier Part") "C1525")
      )
      (libsource (lib "") (part "CL05B104KO5NNNC"))
    )
    (comp (ref "C15")
      (value "1uF")
      (fields
        (field (name "BOM_Manufacturer Part") "CL05A105KP5NNNC")
        (field (name "BOM_Supplier Part") "C14445")
      )
      (libsource (lib "") (part "CL05A105KP5NNNC"))
    )
    (comp (ref "C16")
      (value "100nF")
      (fields
        (field (name "BOM_Manufacturer Part") "CL05B104KO5NNNC")
        (field (name "BOM_Supplier Part") "C1525")
      )
      (libsource (lib "") (part "CL05B104KO5NNNC_1"))
    )
    (comp (ref "C17")
      (value "100nF")
      (fields
        (field (name "BOM_Manufacturer Part") "CL05B104KO5NNNC")
        (field (name "BOM_Supplier Part") "C1525")
      )
      (libsource (lib "") (part "CL05B104KO5NNNC"))
    )
    (comp (ref "C18")
      (value "1uF")
      (fields
        (field (name "BOM_Manufacturer Part") "CL05A105KP5NNNC")
        (field (name "BOM_Supplier Part") "C14445")
      )
      (libsource (lib "") (part "CL05A105KP5NNNC"))
    )
    (comp (ref "C19")
      (value "10uF")
      (fields
        (field (name "BOM_Manufacturer Part") "CL05A106MQ5NUNC")
        (field (name "BOM_Supplier Part") "C15525")
      )
      (libsource (lib "") (part "CL05A106MQ5NUNC"))
    )
    (comp (ref "C20")
      (value "10uF")
      (fields
        (field (name "BOM_Manufacturer Part") "CL05A106MQ5NUNC")
        (field (name "BOM_Supplier Part") "C15525")
      )
      (libsource (lib "") (part "CL05A106MQ5NUNC"))
    )
    (comp (ref "C21")
      (value "10uF")
      (fields
        (field (name "BOM_Manufacturer Part") "CL05A106MQ5NUNC")
        (field (name "BOM_Supplier Part") "C15525")
      )
      (libsource (lib "") (part "CL05A106MQ5NUNC"))
    )
    (comp (ref "C22")
      (value "10uF")
      (fields
        (field (name "BOM_Manufacturer Part") "CL05A106MQ5NUNC")
        (field (name "BOM_Supplier Part") "C15525")
      )
      (libsource (lib "") (part "CL05A106MQ5NUNC"))
    )
    (comp (ref "C23")
      (value "10uF")
      (fields
        (field (name "BOM_Manufacturer Part") "CL05A106MQ5NUNC")
        (field (name "BOM_Supplier Part") "C15525")
      )
      (libsource (lib "") (part "CL05A106MQ5NUNC"))
    )
    (comp (ref "C24")
      (value "10uF")
      (fields
        (field (name "BOM_Manufacturer Part") "CL05A106MQ5NUNC")
        (field (name "BOM_Supplier Part") "C15525")
      )
      (libsource (lib "") (part "CL05A106MQ5NUNC"))
    )
    (comp (ref "C25")
      (value "10uF")
      (fields
        (field (name "BOM_Manufacturer Part") "CL05A106MQ5NUNC")
        (field (name "BOM_Supplier Part") "C15525")
      )
      (libsource (lib "") (part "CL05A106MQ5NUNC"))
    )
    (comp (ref "C26")
      (value "100nF")
      (fields
        (field (name "BOM_Manufacturer Part") "CL05B104KO5NNNC")
        (field (name "BOM_Supplier Part") "C1525")
      )
      (libsource (lib "") (part "CL05B104KO5NNNC"))
    )
    (comp (ref "C27")
      (value "100nF")
      (fields
        (field (name "BOM_Manufacturer Part") "CL05B104KO5NNNC")
        (field (name "BOM_Supplier Part") "C1525")
      )
      (libsource (lib "") (part "CL05B104KO5NNNC"))
    )
    (comp (ref "C28")
      (value "100nF")
      (fields
        (field (name "BOM_Manufacturer Part") "CL05B104KO5NNNC")
        (field (name "BOM_Supplier Part") "C1525")
      )
      (libsource (lib "") (part "CL05B104KO5NNNC"))
    )
    (comp (ref "C29")
      (value "100nF")
      (fields
        (field (name "BOM_Manufacturer Part") "CL05B104KO5NNNC")
        (field (name "BOM_Supplier Part") "C1525")
      )
      (libsource (lib "") (part "CL05B104KO5NNNC"))
    )
    (comp (ref "C30")
      (value "100nF")
      (fields
        (field (name "BOM_Manufacturer Part") "CL05B104KO5NNNC")
        (field (name "BOM_Supplier Part") "C1525")
      )
      (libsource (lib "") (part "CL05B104KO5NNNC"))
    )
    (comp (ref "C31")
      (value "10uF")
      (fields
        (field (name "BOM_Manufacturer Part") "CL05A106MQ5NUNC")
        (field (name "BOM_Supplier Part") "C15525")
      )
      (libsource (lib "") (part "CL05A106MQ5NUNC"))
    )
    (comp (ref "C32")
      (value "10uF")
      (fields
        (field (name "BOM_Manufacturer Part") "CL05A106MQ5NUNC")
        (field (name "BOM_Supplier Part") "C15525")
      )
      (libsource (lib "") (part "CL05A106MQ5NUNC"))
    )
    (comp (ref "C33")
      (value "100nF")
      (fields
        (field (name "BOM_Manufacturer Part") "CL05B104KO5NNNC")
        (field (name "BOM_Supplier Part") "C1525")
      )
      (libsource (lib "") (part "CL05B104KO5NNNC"))
    )
    (comp (ref "C34")
      (value "100nF")
      (fields
        (field (name "BOM_Manufacturer Part") "CL05B104KO5NNNC")
        (field (name "BOM_Supplier Part") "C1525")
      )
      (libsource (lib "") (part "CL05B104KO5NNNC"))
    )
    (comp (ref "C35")
      (value "100nF")
      (fields
        (field (name "BOM_Manufacturer Part") "CL05B104KO5NNNC")
        (field (name "BOM_Supplier Part") "C1525")
      )
      (libsource (lib "") (part "CL05B104KO5NNNC"))
    )
    (comp (ref "C36")
      (value "100nF")
      (fields
        (field (name "BOM_Manufacturer Part") "CL05B104KO5NNNC")
        (field (name "BOM_Supplier Part") "C1525")
      )
      (libsource (lib "") (part "CL05B104KO5NNNC"))
    )
    (comp (ref "C37")
      (value "100uF")
      (fields
        (field (name "BOM_Manufacturer Part") "CL32A107MPVNNNE")
        (field (name "BOM_Supplier Part") "C23742")
      )
      (libsource (lib "") (part "CL32A107MPVNNNE"))
    )
    (comp (ref "C38")
      (value "10uF")
      (fields
        (field (name "BOM_Manufacturer Part") "CL05A106MQ5NUNC")
        (field (name "BOM_Supplier Part") "C15525")
      )
      (libsource (lib "") (part "CL05A106MQ5NUNC"))
    )
    (comp (ref "C39")
      (value "10uF")
      (fields
        (field (name "BOM_Manufacturer Part") "CL05A106MQ5NUNC")
        (field (name "BOM_Supplier Part") "C15525")
      )
      (libsource (lib "") (part "CL05A106MQ5NUNC"))
    )
    (comp (ref "C40")
      (value "100nF")
      (fields
        (field (name "BOM_Manufacturer Part") "CL05B104KO5NNNC")
        (field (name "BOM_Supplier Part") "C1525")
      )
      (libsource (lib "") (part "CL05B104KO5NNNC"))
    )
    (comp (ref "C41")
      (value "100nF")
      (fields
        (field (name "BOM_Manufacturer Part") "CL05B104KO5NNNC")
        (field (name "BOM_Supplier Part") "C1525")
      )
      (libsource (lib "") (part "CL05B104KO5NNNC"))
    )
    (comp (ref "C42")
      (value "100nF")
      (fields
        (field (name "BOM_Manufacturer Part") "CL05B104KO5NNNC")
        (field (name "BOM_Supplier Part") "C1525")
      )
      (libsource (lib "") (part "CL05B104KO5NNNC"))
    )
    (comp (ref "C43")
      (value "100nF")
      (fields
        (field (name "BOM_Manufacturer Part") "CL05B104KO5NNNC")
        (field (name "BOM_Supplier Part") "C1525")
      )
      (libsource (lib "") (part "CL05B104KO5NNNC"))
    )
    (comp (ref "C44")
      (value "100uF")
      (fields
        (field (name "BOM_Manufacturer Part") "CL32A107MPVNNNE")
        (field (name "BOM_Supplier Part") "C23742")
      )
      (libsource (lib "") (part "CL32A107MPVNNNE"))
    )
    (comp (ref "C45")
      (value "10uF")
      (fields
        (field (name "BOM_Manufacturer Part") "CL05A106MQ5NUNC")
        (field (name "BOM_Supplier Part") "C15525")
      )
      (libsource (lib "") (part "CL05A106MQ5NUNC"))
    )
    (comp (ref "C46")
      (value "10uF")
      (fields
        (field (name "BOM_Manufacturer Part") "CL05A106MQ5NUNC")
        (field (name "BOM_Supplier Part") "C15525")
      )
      (libsource (lib "") (part "CL05A106MQ5NUNC"))
    )
    (comp (ref "C47")
      (value "100nF")
      (fields
        (field (name "BOM_Manufacturer Part") "CL05B104KO5NNNC")
        (field (name "BOM_Supplier Part") "C1525")
      )
      (libsource (lib "") (part "CL05B104KO5NNNC"))
    )
    (comp (ref "C48")
      (value "100nF")
      (fields
        (field (name "BOM_Manufacturer Part") "CL05B104KO5NNNC")
        (field (name "BOM_Supplier Part") "C1525")
      )
      (libsource (lib "") (part "CL05B104KO5NNNC"))
    )
    (comp (ref "C49")
      (value "100uF")
      (fields
        (field (name "BOM_Manufacturer Part") "CL32A107MPVNNNE")
        (field (name "BOM_Supplier Part") "C23742")
      )
      (libsource (lib "") (part "CL32A107MPVNNNE"))
    )
    (comp (ref "C50")
      (value "100nF")
      (fields
        (field (name "BOM_Manufacturer Part") "CL05B104KO5NNNC")
        (field (name "BOM_Supplier Part") "C1525")
      )
      (libsource (lib "") (part "CL05B104KO5NNNC"))
    )
    (comp (ref "C51")
      (value "100nF")
      (fields
        (field (name "BOM_Manufacturer Part") "CL05B104KO5NNNC")
        (field (name "BOM_Supplier Part") "C1525")
      )
      (libsource (lib "") (part "CL05B104KO5NNNC"))
    )
    (comp (ref "C52")
      (value "10uF")
      (fields
        (field (name "BOM_Manufacturer Part") "CL05A106MQ5NUNC")
        (field (name "BOM_Supplier Part") "C15525")
      )
      (libsource (lib "") (part "CL05A106MQ5NUNC"))
    )
    (comp (ref "C53")
      (value "10uF")
      (fields
        (field (name "BOM_Manufacturer Part") "CL05A106MQ5NUNC")
        (field (name "BOM_Supplier Part") "C15525")
      )
      (libsource (lib "") (part "CL05A106MQ5NUNC"))
    )
    (comp (ref "C54")
      (value "100nF")
      (fields
        (field (name "BOM_Manufacturer Part") "CL05B104KO5NNNC")
        (field (name "BOM_Supplier Part") "C1525")
      )
      (libsource (lib "") (part "CL05B104KO5NNNC"))
    )
    (comp (ref "C55")
      (value "100nF")
      (fields
        (field (name "BOM_Manufacturer Part") "CL05B104KO5NNNC")
        (field (name "BOM_Supplier Part") "C1525")
      )
      (libsource (lib "") (part "CL05B104KO5NNNC"))
    )
    (comp (ref "C56")
      (value "100uF")
      (fields
        (field (name "BOM_Manufacturer Part") "CL32A107MPVNNNE")
        (field (name "BOM_Supplier Part") "C23742")
      )
      (libsource (lib "") (part "CL32A107MPVNNNE"))
    )
    (comp (ref "C57")
      (value "100nF")
      (fields
        (field (name "BOM_Manufacturer Part") "CL05B104KO5NNNC")
        (field (name "BOM_Supplier Part") "C1525")
      )
      (libsource (lib "") (part "CL05B104KO5NNNC"))
    )
    (comp (ref "C58")
      (value "100nF")
      (fields
        (field (name "BOM_Manufacturer Part") "CL05B104KO5NNNC")
        (field (name "BOM_Supplier Part") "C1525")
      )
      (libsource (lib "") (part "CL05B104KO5NNNC"))
    )
    (comp (ref "C59")
      (value "10uF")
      (fields
        (field (name "BOM_Manufacturer Part") "CL05A106MQ5NUNC")
        (field (name "BOM_Supplier Part") "C15525")
      )
      (libsource (lib "") (part "CL05A106MQ5NUNC"))
    )
    (comp (ref "C60")
      (value "10uF")
      (fields
        (field (name "BOM_Manufacturer Part") "CL05A106MQ5NUNC")
        (field (name "BOM_Supplier Part") "C15525")
      )
      (libsource (lib "") (part "CL05A106MQ5NUNC"))
    )
    (comp (ref "C61")
      (value "100nF")
      (fields
        (field (name "BOM_Manufacturer Part") "CL05B104KO5NNNC")
        (field (name "BOM_Supplier Part") "C1525")
      )
      (libsource (lib "") (part "CL05B104KO5NNNC"))
    )
    (comp (ref "C62")
      (value "100nF")
      (fields
        (field (name "BOM_Manufacturer Part") "CL05B104KO5NNNC")
        (field (name "BOM_Supplier Part") "C1525")
      )
      (libsource (lib "") (part "CL05B104KO5NNNC"))
    )
    (comp (ref "C63")
      (value "100uF")
      (fields
        (field (name "BOM_Manufacturer Part") "CL32A107MPVNNNE")
        (field (name "BOM_Supplier Part") "C23742")
      )
      (libsource (lib "") (part "CL32A107MPVNNNE"))
    )
    (comp (ref "C64")
      (value "100nF")
      (fields
        (field (name "BOM_Manufacturer Part") "CL05B104KO5NNNC")
        (field (name "BOM_Supplier Part") "C1525")
      )
      (libsource (lib "") (part "CL05B104KO5NNNC"))
    )
    (comp (ref "C65")
      (value "100nF")
      (fields
        (field (name "BOM_Manufacturer Part") "CL05B104KO5NNNC")
        (field (name "BOM_Supplier Part") "C1525")
      )
      (libsource (lib "") (part "CL05B104KO5NNNC"))
    )
    (comp (ref "C66")
      (value "10uF")
      (fields
        (field (name "BOM_Manufacturer Part") "CL05A106MQ5NUNC")
        (field (name "BOM_Supplier Part") "C15525")
      )
      (libsource (lib "") (part "CL05A106MQ5NUNC"))
    )
    (comp (ref "C67")
      (value "10uF")
      (fields
        (field (name "BOM_Manufacturer Part") "CL05A106MQ5NUNC")
        (field (name "BOM_Supplier Part") "C15525")
      )
      (libsource (lib "") (part "CL05A106MQ5NUNC"))
    )
    (comp (ref "FAT-CAT")
      (value "ATMEGA328PB-AU")
      (fields (field (name "BOM_Supplier Part") "C132230"))
      (libsource (lib "") (part "ATMEGA328PB-AU"))
    )
    (comp (ref "FTDI") (value "SSW-106-02-F-S-RA") (libsource (lib "") (part "SSW-106-02-F-S-RA")))
    (comp (ref "LDO")
      (value "TLV1117LV33DCYR")
      (fields (field (name "BOM_Supplier Part") "C15578"))
      (libsource (lib "") (part "TLV1117LV33DCYR"))
    )
    (comp (ref "LVLSHF")
      (value "SN74LVC125ADR")
      (fields (field (name "BOM_Supplier Part") "C7661"))
      (libsource (lib "") (part "SN74LVC125ADR"))
    )
    (comp (ref "R36")
      (value "3.3kΩ")
      (fields
        (field (name "BOM_Manufacturer Part") "0402WGF3301TCE")
        (field (name "BOM_Supplier Part") "C25890")
      )
      (libsource (lib "") (part "0402WGF3301TCE"))
    )
    (comp (ref "R37")
      (value "3.3kΩ")
      (fields
        (field (name "BOM_Manufacturer Part") "0402WGF3301TCE")
        (field (name "BOM_Supplier Part") "C25890")
      )
      (libsource (lib "") (part "0402WGF3301TCE"))
    )
    (comp (ref "R38")
      (value "3.3kΩ")
      (fields
        (field (name "BOM_Manufacturer Part") "0402WGF3301TCE")
        (field (name "BOM_Supplier Part") "C25890")
      )
      (libsource (lib "") (part "0402WGF3301TCE"))
    )
    (comp (ref "R39")
      (value "3.3kΩ")
      (fields
        (field (name "BOM_Manufacturer Part") "0402WGF3301TCE")
        (field (name "BOM_Supplier Part") "C25890")
      )
      (libsource (lib "") (part "0402WGF3301TCE"))
    )
    (comp (ref "R40")
      (value "33Ω")
      (fields
        (field (name "BOM_Manufacturer Part") "0402WGF330JTCE")
        (field (name "BOM_Supplier Part") "C25105")
      )
      (libsource (lib "") (part "0402WGF330JTCE"))
    )
    (comp (ref "R41")
      (value "10KΩ")
      (fields
        (field (name "BOM_Manufacturer Part") "RC0402FR-0710KL")
        (field (name "BOM_Supplier Part") "C60490")
      )
      (libsource (lib "") (part "RC0402FR-0710KL"))
    )
    (comp (ref "SD")
      (value "TF-01A_C2889258")
      (fields (field (name "BOM_Manufacturer Part") "TF-01A") (field (name "BOM_Supplier Part") "C2889258"))
      (libsource (lib "") (part "TF-01A_C2889258"))
    )
    (comp (ref "BOOTLD")
      (value "PZ254-1-06-Z-8.5")
      (fields (field (name "BOM_Supplier Part") "C2894929"))
      (libsource (lib "") (part "PZ254-1-06-Z-8.5"))
    )
    (comp (ref "BT1")
      (value "SN74HC245NSR")
      (fields (field (name "BOM_Supplier Part") "C88578"))
      (libsource (lib "") (part "SN74HC245NSR"))
    )
    (comp (ref "BT2")
      (value "SN74HC245NSR")
      (fields (field (name "BOM_Supplier Part") "C88578"))
      (libsource (lib "") (part "SN74HC245NSR"))
    )
    (comp (ref "BT3")
      (value "SN74HC245NSR")
      (fields (field (name "BOM_Supplier Part") "C88578"))
      (libsource (lib "") (part "SN74HC245NSR"))
    )
    (comp (ref "BUFFER1")
      (value "SN74HC244NSR")
      (fields (field (name "BOM_Supplier Part") "C10094"))
      (libsource (lib "") (part "SN74HC244NSR"))
    )
    (comp (ref "C68")
      (value "100uF")
      (fields
        (field (name "BOM_Manufacturer Part") "CL32A107MPVNNNE")
        (field (name "BOM_Supplier Part") "C23742")
      )
      (libsource (lib "") (part "CL32A107MPVNNNE"))
    )
    (comp (ref "C69")
      (value "100nF")
      (fields
        (field (name "BOM_Manufacturer Part") "CL05B104KO5NNNC")
        (field (name "BOM_Supplier Part") "C1525")
      )
      (libsource (lib "") (part "CL05B104KO5NNNC"))
    )
    (comp (ref "D1")
      (value "GG0402052R542P")
      (fields (field (name "BOM_Supplier Part") "C1973257"))
      (libsource (lib "") (part "GG0402052R542P"))
    )
    (comp (ref "EXP1")
      (value "BH-00105")
      (fields (field (name "BOM_Supplier Part") "C2685065"))
      (libsource (lib "") (part "BH-00105"))
    )
    (comp (ref "F2")
      (value "BSMD0805L-150")
      (fields (field (name "BOM_Supplier Part") "C914095"))
      (libsource (lib "") (part "BSMD0805L-150"))
    )
    (comp (ref "OR")
      (value "SN74AHCT1G32DCKR")
      (fields (field (name "BOM_Supplier Part") "C350558"))
      (libsource (lib "") (part "SN74AHCT1G32DCKR"))
    )
    (comp (ref "R42")
      (value "10K")
      (fields
        (field (name "BOM_Manufacturer Part") "RC0402FR-0710KL")
        (field (name "BOM_Supplier Part") "C60490")
      )
      (libsource (lib "") (part "RC0402FR-0710KL"))
    )
    (comp (ref "R43")
      (value "10K")
      (fields
        (field (name "BOM_Manufacturer Part") "RC0402FR-0710KL")
        (field (name "BOM_Supplier Part") "C60490")
      )
      (libsource (lib "") (part "RC0402FR-0710KL"))
    )
    (comp (ref "R44")
      (value "10K")
      (fields
        (field (name "BOM_Manufacturer Part") "RC0402FR-0710KL")
        (field (name "BOM_Supplier Part") "C60490")
      )
      (libsource (lib "") (part "RC0402FR-0710KL"))
    )
    (comp (ref "R45")
      (value "10K")
      (fields
        (field (name "BOM_Manufacturer Part") "RC0402FR-0710KL")
        (field (name "BOM_Supplier Part") "C60490")
      )
      (libsource (lib "") (part "RC0402FR-0710KL"))
    )
    (comp (ref "R46")
      (value "10K")
      (fields
        (field (name "BOM_Manufacturer Part") "RC0402FR-0710KL")
        (field (name "BOM_Supplier Part") "C60490")
      )
      (libsource (lib "") (part "RC0402FR-0710KL"))
    )
    (comp (ref "R47")
      (value "10K")
      (fields
        (field (name "BOM_Manufacturer Part") "RC0402FR-0710KL")
        (field (name "BOM_Supplier Part") "C60490")
      )
      (libsource (lib "") (part "RC0402FR-0710KL"))
    )
    (comp (ref "R48")
      (value "10K")
      (fields
        (field (name "BOM_Manufacturer Part") "RC0402FR-0710KL")
        (field (name "BOM_Supplier Part") "C60490")
      )
      (libsource (lib "") (part "RC0402FR-0710KL"))
    )
    (comp (ref "R49")
      (value "10K")
      (fields
        (field (name "BOM_Manufacturer Part") "RC0402FR-0710KL")
        (field (name "BOM_Supplier Part") "C60490")
      )
      (libsource (lib "") (part "RC0402FR-0710KL"))
    )
    (comp (ref "R50")
      (value "10K")
      (fields
        (field (name "BOM_Manufacturer Part") "RC0402FR-0710KL")
        (field (name "BOM_Supplier Part") "C60490")
      )
      (libsource (lib "") (part "RC0402FR-0710KL"))
    )
    (comp (ref "R51")
      (value "10K")
      (fields
        (field (name "BOM_Manufacturer Part") "RC0402FR-0710KL")
        (field (name "BOM_Supplier Part") "C60490")
      )
      (libsource (lib "") (part "RC0402FR-0710KL_1"))
    )
    (comp (ref "R52")
      (value "10K")
      (fields
        (field (name "BOM_Manufacturer Part") "RC0402FR-0710KL")
        (field (name "BOM_Supplier Part") "C60490")
      )
      (libsource (lib "") (part "RC0402FR-0710KL"))
    )
    (comp (ref "R53")
      (value "10K")
      (fields
        (field (name "BOM_Manufacturer Part") "RC0402FR-0710KL")
        (field (name "BOM_Supplier Part") "C60490")
      )
      (libsource (lib "") (part "RC0402FR-0710KL_1"))
    )
    (comp (ref "R54")
      (value "10K")
      (fields
        (field (name "BOM_Manufacturer Part") "RC0402FR-0710KL")
        (field (name "BOM_Supplier Part") "C60490")
      )
      (libsource (lib "") (part "RC0402FR-0710KL"))
    )
    (comp (ref "R55")
      (value "10K")
      (fields
        (field (name "BOM_Manufacturer Part") "RC0402FR-0710KL")
        (field (name "BOM_Supplier Part") "C60490")
      )
      (libsource (lib "") (part "RC0402FR-0710KL"))
    )
    (comp (ref "R56")
      (value "10K")
      (fields
        (field (name "BOM_Manufacturer Part") "RC0402FR-0710KL")
        (field (name "BOM_Supplier Part") "C60490")
      )
      (libsource (lib "") (part "RC0402FR-0710KL"))
    )
    (comp (ref "R57")
      (value "10K")
      (fields
        (field (name "BOM_Manufacturer Part") "RC0402FR-0710KL")
        (field (name "BOM_Supplier Part") "C60490")
      )
      (libsource (lib "") (part "RC0402FR-0710KL"))
    )
    (comp (ref "R58")
      (value "10K")
      (fields
        (field (name "BOM_Manufacturer Part") "RC0402FR-0710KL")
        (field (name "BOM_Supplier Part") "C60490")
      )
      (libsource (lib "") (part "RC0402FR-0710KL"))
    )
    (comp (ref "R59")
      (value "10K")
      (fields
        (field (name "BOM_Manufacturer Part") "RC0402FR-0710KL")
        (field (name "BOM_Supplier Part") "C60490")
      )
      (libsource (lib "") (part "RC0402FR-0710KL"))
    )
    (comp (ref "R60")
      (value "10K")
      (fields
        (field (name "BOM_Manufacturer Part") "RC0402FR-0710KL")
        (field (name "BOM_Supplier Part") "C60490")
      )
      (libsource (lib "") (part "RC0402FR-0710KL"))
    )
    (comp (ref "R61")
      (value "10K")
      (fields
        (field (name "BOM_Manufacturer Part") "RC0402FR-0710KL")
        (field (name "BOM_Supplier Part") "C60490")
      )
      (libsource (lib "") (part "RC0402FR-0710KL"))
    )
    (comp (ref "R62")
      (value "10K")
      (fields
        (field (name "BOM_Manufacturer Part") "RC0402FR-0710KL")
        (field (name "BOM_Supplier Part") "C60490")
      )
      (libsource (lib "") (part "RC0402FR-0710KL"))
    )
    (comp (ref "R63")
      (value "10K")
      (fields
        (field (name "BOM_Manufacturer Part") "RC0402FR-0710KL")
        (field (name "BOM_Supplier Part") "C60490")
      )
      (libsource (lib "") (part "RC0402FR-0710KL"))
    )
    (comp (ref "R64")
      (value "10K")
      (fields
        (field (name "BOM_Manufacturer Part") "RC0402FR-0710KL")
        (field (name "BOM_Supplier Part") "C60490")
      )
      (libsource (lib "") (part "RC0402FR-0710KL"))
    )
    (comp (ref "R65")
      (value "10K")
      (fields
        (field (name "BOM_Manufacturer Part") "RC0402FR-0710KL")
        (field (name "BOM_Supplier Part") "C60490")
      )
      (libsource (lib "") (part "RC0402FR-0710KL"))
    )
    (comp (ref "R66")
      (value "10K")
      (fields
        (field (name "BOM_Manufacturer Part") "RC0402FR-0710KL")
        (field (name "BOM_Supplier Part") "C60490")
      )
      (libsource (lib "") (part "RC0402FR-0710KL"))
    )
    (comp (ref "R67")
      (value "10K")
      (fields
        (field (name "BOM_Manufacturer Part") "RC0402FR-0710KL")
        (field (name "BOM_Supplier Part") "C60490")
      )
      (libsource (lib "") (part "RC0402FR-0710KL"))
    )
    (comp (ref "R68")
      (value "33Ω")
      (fields
        (field (name "BOM_Manufacturer Part") "0402WGF330JTCE")
        (field (name "BOM_Supplier Part") "C25105")
      )
      (libsource (lib "") (part "0402WGF330JTCE"))
    )
    (comp (ref "RN1")
      (value "10kΩ")
      (fields (field (name "BOM_Manufacturer Part") "A09-103JP") (field (name "BOM_Supplier Part") "C8692"))
      (libsource (lib "") (part "A09-103JP"))
    )
    (comp (ref "RN2")
      (value "10kΩ")
      (fields (field (name "BOM_Manufacturer Part") "A09-103JP") (field (name "BOM_Supplier Part") "C8692"))
      (libsource (lib "") (part "A09-103JP"))
    )
    (comp (ref "RN3")
      (value "10kΩ")
      (fields (field (name "BOM_Manufacturer Part") "A09-103JP") (field (name "BOM_Supplier Part") "C8692"))
      (libsource (lib "") (part "A09-103JP"))
    )
    (comp (ref "RN4")
      (value "10K")
      (fields
        (field (name "BOM_Manufacturer Part") "YC164-FR-0710KL")
        (field (name "BOM_Supplier Part") "C110924")
      )
      (libsource (lib "") (part "YC164-FR-0710KL"))
    )
    (comp (ref "RN5")
      (value "10K")
      (fields
        (field (name "BOM_Manufacturer Part") "YC164-FR-0710KL")
        (field (name "BOM_Supplier Part") "C110924")
      )
      (libsource (lib "") (part "YC164-FR-0710KL"))
    )
  )
  (nets
    (net (code "1") (name "3V3") (class "Default")
      (node (ref "C14") (pin "2") (pinfunction "2_2") (pintype "input"))
      (node (ref "C17") (pin "2") (pinfunction "2_2") (pintype "input"))
      (node (ref "C18") (pin "2") (pinfunction "2_2") (pintype "input"))
      (node (ref "LDO") (pin "2") (pinfunction "OUT_2") (pintype "passive"))
      (node (ref "LDO") (pin "4") (pinfunction "OUT_4") (pintype "passive"))
      (node (ref "LVLSHF") (pin "14") (pinfunction "VCC_14") (pintype "unspecified"))
      (node (ref "SD") (pin "4") (pinfunction "VDD_4") (pintype "unspecified"))
    )
    (net (code "2") (name "A0") (class "Default")
      (node (ref "BT2") (pin "9") (pinfunction "A8_9") (pintype "unspecified"))
      (node (ref "CHARMEM") (pin "52") (pinfunction "A0L_52") (pintype "unspecified"))
      (node (ref "FAT-SPACER") (pin "75") (pinfunction "I/O_75") (pintype "unspecified"))
      (node (ref "HIGH-MEM") (pin "10") (pinfunction "A0_10") (pintype "unspecified"))
      (node (ref "LOW-MEM") (pin "10") (pinfunction "A0_10") (pintype "unspecified"))
      (node (ref "RN3") (pin "9") (pinfunction "9_9") (pintype "input"))
      (node (ref "VIDEOMEM") (pin "52") (pinfunction "A0L_52") (pintype "unspecified"))
      (node (ref "W65C02S") (pin "4") (pinfunction "A0_4") (pintype "unspecified"))
      (node (ref "Z80") (pin "27") (pinfunction "A0_27") (pintype "unspecified"))
    )
    (net (code "3") (name "A1") (class "Default")
      (node (ref "BT2") (pin "8") (pinfunction "A7_8") (pintype "unspecified"))
      (node (ref "CHARMEM") (pin "1") (pinfunction "A1L_1") (pintype "unspecified"))
      (node (ref "FAT-SPACER") (pin "72") (pinfunction "I/O_72") (pintype "unspecified"))
      (node (ref "HIGH-MEM") (pin "9") (pinfunction "A1_9") (pintype "unspecified"))
      (node (ref "LOW-MEM") (pin "9") (pinfunction "A1_9") (pintype "unspecified"))
      (node (ref "RN3") (pin "8") (pinfunction "8_8") (pintype "input"))
      (node (ref "VIDEOMEM") (pin "1") (pinfunction "A1L_1") (pintype "unspecified"))
      (node (ref "W65C02S") (pin "5") (pinfunction "A1_5") (pintype "unspecified"))
      (node (ref "Z80") (pin "28") (pinfunction "A1_28") (pintype "unspecified"))
    )
    (net (code "4") (name "A2") (class "Default")
      (node (ref "BT2") (pin "7") (pinfunction "A6_7") (pintype "unspecified"))
      (node (ref "CHARMEM") (pin "2") (pinfunction "A2L_2") (pintype "unspecified"))
      (node (ref "FAT-SPACER") (pin "71") (pinfunction "I/O_71") (pintype "unspecified"))
      (node (ref "HIGH-MEM") (pin "8") (pinfunction "A2_8") (pintype "unspecified"))
      (node (ref "LOW-MEM") (pin "8") (pinfunction "A2_8") (pintype "unspecified"))
      (node (ref "RN3") (pin "7") (pinfunction "7_7") (pintype "input"))
      (node (ref "VIDEOMEM") (pin "2") (pinfunction "A2L_2") (pintype "unspecified"))
      (node (ref "W65C02S") (pin "7") (pinfunction "A2_7") (pintype "unspecified"))
      (node (ref "Z80") (pin "29") (pinfunction "A2_29") (pintype "unspecified"))
    )
    (net (code "5") (name "A3") (class "Default")
      (node (ref "BT2") (pin "6") (pinfunction "A5_6") (pintype "unspecified"))
      (node (ref "CHARMEM") (pin "3") (pinfunction "A3L_3") (pintype "unspecified"))
      (node (ref "FAT-SPACER") (pin "70") (pinfunction "I/O_70") (pintype "unspecified"))
      (node (ref "HIGH-MEM") (pin "7") (pinfunction "A3_7") (pintype "unspecified"))
      (node (ref "LOW-MEM") (pin "7") (pinfunction "A3_7") (pintype "unspecified"))
      (node (ref "RN3") (pin "6") (pinfunction "6_6") (pintype "input"))
      (node (ref "VIDEOMEM") (pin "3") (pinfunction "A3L_3") (pintype "unspecified"))
      (node (ref "W65C02S") (pin "8") (pinfunction "A3_8") (pintype "unspecified"))
      (node (ref "Z80") (pin "30") (pinfunction "A3_30") (pintype "unspecified"))
    )
    (net (code "6") (name "A4") (class "Default")
      (node (ref "BT2") (pin "5") (pinfunction "A4_5") (pintype "unspecified"))
      (node (ref "CHARMEM") (pin "4") (pinfunction "A4L_4") (pintype "unspecified"))
      (node (ref "FAT-SPACER") (pin "69") (pinfunction "I/O_69") (pintype "unspecified"))
      (node (ref "HIGH-MEM") (pin "6") (pinfunction "A4_6") (pintype "unspecified"))
      (node (ref "LOW-MEM") (pin "6") (pinfunction "A4_6") (pintype "unspecified"))
      (node (ref "RN3") (pin "5") (pinfunction "5_5") (pintype "input"))
      (node (ref "VIDEOMEM") (pin "4") (pinfunction "A4L_4") (pintype "unspecified"))
      (node (ref "W65C02S") (pin "9") (pinfunction "A4_9") (pintype "unspecified"))
      (node (ref "Z80") (pin "31") (pinfunction "A4_31") (pintype "unspecified"))
    )
    (net (code "7") (name "A5") (class "Default")
      (node (ref "BT2") (pin "4") (pinfunction "A3_4") (pintype "unspecified"))
      (node (ref "CHARMEM") (pin "5") (pinfunction "A5L_5") (pintype "unspecified"))
      (node (ref "FAT-SPACER") (pin "68") (pinfunction "I/O_68") (pintype "unspecified"))
      (node (ref "HIGH-MEM") (pin "5") (pinfunction "A5_5") (pintype "unspecified"))
      (node (ref "LOW-MEM") (pin "5") (pinfunction "A5_5") (pintype "unspecified"))
      (node (ref "RN3") (pin "4") (pinfunction "4_4") (pintype "input"))
      (node (ref "VIDEOMEM") (pin "5") (pinfunction "A5L_5") (pintype "unspecified"))
      (node (ref "W65C02S") (pin "10") (pinfunction "A5_10") (pintype "unspecified"))
      (node (ref "Z80") (pin "32") (pinfunction "A5_32") (pintype "unspecified"))
    )
    (net (code "8") (name "A6") (class "Default")
      (node (ref "BT2") (pin "3") (pinfunction "A2_3") (pintype "unspecified"))
      (node (ref "CHARMEM") (pin "6") (pinfunction "A6L_6") (pintype "unspecified"))
      (node (ref "FAT-SPACER") (pin "67") (pinfunction "I/O_67") (pintype "unspecified"))
      (node (ref "HIGH-MEM") (pin "4") (pinfunction "A6_4") (pintype "unspecified"))
      (node (ref "LOW-MEM") (pin "4") (pinfunction "A6_4") (pintype "unspecified"))
      (node (ref "RN3") (pin "3") (pinfunction "3_3") (pintype "input"))
      (node (ref "VIDEOMEM") (pin "6") (pinfunction "A6L_6") (pintype "unspecified"))
      (node (ref "W65C02S") (pin "11") (pinfunction "A6_11") (pintype "unspecified"))
      (node (ref "Z80") (pin "34") (pinfunction "A6_34") (pintype "unspecified"))
    )
    (net (code "9") (name "A7") (class "Default")
      (node (ref "BT2") (pin "2") (pinfunction "A1_2") (pintype "unspecified"))
      (node (ref "CHARMEM") (pin "7") (pinfunction "A7L_7") (pintype "unspecified"))
      (node (ref "FAT-SPACER") (pin "65") (pinfunction "I/O_65") (pintype "unspecified"))
      (node (ref "HIGH-MEM") (pin "3") (pinfunction "A7_3") (pintype "unspecified"))
      (node (ref "LOW-MEM") (pin "3") (pinfunction "A7_3") (pintype "unspecified"))
      (node (ref "RN3") (pin "2") (pinfunction "2_2") (pintype "input"))
      (node (ref "VIDEOMEM") (pin "7") (pinfunction "A7L_7") (pintype "unspecified"))
      (node (ref "W65C02S") (pin "12") (pinfunction "A7_12") (pintype "unspecified"))
      (node (ref "Z80") (pin "35") (pinfunction "A7_35") (pintype "unspecified"))
    )
    (net (code "10") (name "A8") (class "Default")
      (node (ref "BT3") (pin "9") (pinfunction "A8_9") (pintype "unspecified"))
      (node (ref "CHARMEM") (pin "8") (pinfunction "A8L_8") (pintype "unspecified"))
      (node (ref "FAT-SPACER") (pin "64") (pinfunction "I/O_64") (pintype "unspecified"))
      (node (ref "HIGH-MEM") (pin "25") (pinfunction "A8_25") (pintype "unspecified"))
      (node (ref "LOW-MEM") (pin "25") (pinfunction "A8_25") (pintype "unspecified"))
      (node (ref "RN2") (pin "9") (pinfunction "9_9") (pintype "input"))
      (node (ref "VIDEOMEM") (pin "8") (pinfunction "A8L_8") (pintype "unspecified"))
      (node (ref "W65C02S") (pin "13") (pinfunction "A8_13") (pintype "unspecified"))
      (node (ref "Z80") (pin "36") (pinfunction "A8_36") (pintype "unspecified"))
    )
    (net (code "11") (name "A9") (class "Default")
      (node (ref "BT3") (pin "8") (pinfunction "A7_8") (pintype "unspecified"))
      (node (ref "CHARMEM") (pin "9") (pinfunction "A9L_9") (pintype "unspecified"))
      (node (ref "FAT-SPACER") (pin "63") (pinfunction "I/O_63") (pintype "unspecified"))
      (node (ref "HIGH-MEM") (pin "24") (pinfunction "A9_24") (pintype "unspecified"))
      (node (ref "LOW-MEM") (pin "24") (pinfunction "A9_24") (pintype "unspecified"))
      (node (ref "RN2") (pin "8") (pinfunction "8_8") (pintype "input"))
      (node (ref "VIDEOMEM") (pin "9") (pinfunction "A9L_9") (pintype "unspecified"))
      (node (ref "W65C02S") (pin "14") (pinfunction "A9_14") (pintype "unspecified"))
      (node (ref "Z80") (pin "37") (pinfunction "A9_37") (pintype "unspecified"))
    )
    (net (code "12") (name "A10") (class "Default")
      (node (ref "BT3") (pin "7") (pinfunction "A6_7") (pintype "unspecified"))
      (node (ref "CHARMEM") (pin "50") (pinfunction "A10L_50") (pintype "unspecified"))
      (node (ref "FAT-SPACER") (pin "61") (pinfunction "I/O_61") (pintype "unspecified"))
      (node (ref "HIGH-MEM") (pin "21") (pinfunction "A10_21") (pintype "unspecified"))
      (node (ref "LOW-MEM") (pin "21") (pinfunction "A10_21") (pintype "unspecified"))
      (node (ref "RN2") (pin "7") (pinfunction "7_7") (pintype "input"))
      (node (ref "VIDEOMEM") (pin "50") (pinfunction "A10L_50") (pintype "unspecified"))
      (node (ref "W65C02S") (pin "15") (pinfunction "A10_15") (pintype "unspecified"))
      (node (ref "Z80") (pin "38") (pinfunction "A10_38") (pintype "unspecified"))
    )
    (net (code "13") (name "A11") (class "Default")
      (node (ref "BT3") (pin "6") (pinfunction "A5_6") (pintype "unspecified"))
      (node (ref "FAT-SPACER") (pin "60") (pinfunction "I/O_60") (pintype "unspecified"))
      (node (ref "HIGH-MEM") (pin "23") (pinfunction "A11_23") (pintype "unspecified"))
      (node (ref "LOW-MEM") (pin "23") (pinfunction "A11_23") (pintype "unspecified"))
      (node (ref "RN2") (pin "6") (pinfunction "6_6") (pintype "input"))
      (node (ref "W65C02S") (pin "16") (pinfunction "A11_16") (pintype "unspecified"))
      (node (ref "Z80") (pin "40") (pinfunction "A11_40") (pintype "unspecified"))
    )
    (net (code "14") (name "A12") (class "Default")
      (node (ref "BT3") (pin "5") (pinfunction "A4_5") (pintype "unspecified"))
      (node (ref "FAT-SPACER") (pin "58") (pinfunction "I/O_58") (pintype "unspecified"))
      (node (ref "HIGH-MEM") (pin "2") (pinfunction "A12_2") (pintype "unspecified"))
      (node (ref "LOW-MEM") (pin "2") (pinfunction "A12_2") (pintype "unspecified"))
      (node (ref "RN2") (pin "5") (pinfunction "5_5") (pintype "input"))
      (node (ref "W65C02S") (pin "19") (pinfunction "A12_19") (pintype "unspecified"))
      (node (ref "Z80") (pin "41") (pinfunction "A12_41") (pintype "unspecified"))
    )
    (net (code "15") (name "A13") (class "Default")
      (node (ref "BT3") (pin "4") (pinfunction "A3_4") (pintype "unspecified"))
      (node (ref "FAT-SPACER") (pin "57") (pinfunction "I/O_57") (pintype "unspecified"))
      (node (ref "HIGH-MEM") (pin "26") (pinfunction "A13_26") (pintype "unspecified"))
      (node (ref "LOW-MEM") (pin "26") (pinfunction "A13_26") (pintype "unspecified"))
      (node (ref "RN2") (pin "4") (pinfunction "4_4") (pintype "input"))
      (node (ref "W65C02S") (pin "20") (pinfunction "A13_20") (pintype "unspecified"))
      (node (ref "Z80") (pin "42") (pinfunction "A13_42") (pintype "unspecified"))
    )
    (net (code "16") (name "A14") (class "Default")
      (node (ref "BT3") (pin "3") (pinfunction "A2_3") (pintype "unspecified"))
      (node (ref "FAT-SPACER") (pin "56") (pinfunction "I/O_56") (pintype "unspecified"))
      (node (ref "HIGH-MEM") (pin "1") (pinfunction "A14_1") (pintype "unspecified"))
      (node (ref "LOW-MEM") (pin "1") (pinfunction "A14_1") (pintype "unspecified"))
      (node (ref "RN2") (pin "3") (pinfunction "3_3") (pintype "input"))
      (node (ref "W65C02S") (pin "21") (pinfunction "A14_21") (pintype "unspecified"))
      (node (ref "Z80") (pin "43") (pinfunction "A14_43") (pintype "unspecified"))
    )
    (net (code "17") (name "A15") (class "Default")
      (node (ref "BT3") (pin "2") (pinfunction "A1_2") (pintype "unspecified"))
      (node (ref "FAT-SPACER") (pin "55") (pinfunction "I/O_55") (pintype "unspecified"))
      (node (ref "RN2") (pin "2") (pinfunction "2_2") (pintype "input"))
      (node (ref "W65C02S") (pin "22") (pinfunction "A15_22") (pintype "unspecified"))
      (node (ref "Z80") (pin "44") (pinfunction "A15_44") (pintype "unspecified"))
    )
    (net (code "18") (name "AOE") (class "Default")
      (node (ref "FAT-CAT") (pin "25") (pinfunction "(ADC2/PTCY)PC2_25") (pintype "bidirectional"))
      (node (ref "FAT-SPACER") (pin "30") (pinfunction "I/O_30") (pintype "unspecified"))
    )
    (net (code "19") (name "BE6502") (class "Default")
      (node (ref "FAT-SPACER") (pin "92") (pinfunction "I/O_92") (pintype "unspecified"))
      (node (ref "R65") (pin "1") (pinfunction "1_1") (pintype "input"))
      (node (ref "W65C02S") (pin "34") (pinfunction "BE_34") (pintype "unspecified"))
    )
    (net (code "20") (name "BLUE") (class "Default")
      (node (ref "FAT-SCUNK") (pin "71") (pinfunction "I/O_71") (pintype "unspecified"))
      (node (ref "U6") (pin "2") (pinfunction "A_2") (pintype "unspecified"))
    )
    (net (code "21") (name "BMCLK") (class "Default")
      (node (ref "FAT-SPACER") (pin "87") (pinfunction "INPUT/GCLK1_87") (pintype "unspecified"))
      (node (ref "R31") (pin "1") (pinfunction "1_1") (pintype "input"))
    )
    (net (code "22") (name "BOOTRST") (class "Default")
      (node (ref "BOOTLD") (pin "6") (pinfunction "6_6") (pintype "unspecified"))
      (node (ref "C16") (pin "2") (pinfunction "2_2") (pintype "input"))
      (node (ref "FAT-CAT") (pin "29") (pinfunction "(RESET#)PC6_29") (pintype "bidirectional"))
      (node (ref "R41") (pin "1") (pinfunction "1_1") (pintype "input"))
    )
    (net (code "23") (name "BPCLK") (class "Default")
      (node (ref "FAT-SCUNK") (pin "87") (pinfunction "INPUT/GCLK1_87") (pintype "unspecified"))
      (node (ref "R3") (pin "1") (pinfunction "1_1") (pintype "input"))
    )
    (net (code "24") (name "BUSREQZ80") (class "Default")
      (node (ref "FAT-SPACER") (pin "99") (pinfunction "I/O_99") (pintype "unspecified"))
      (node (ref "R47") (pin "1") (pinfunction "1_1") (pintype "input"))
      (node (ref "Z80") (pin "22") (pinfunction "BUSREQ#_22") (pintype "unspecified"))
    )
    (net (code "25") (name "BXBUSACK") (class "Default")
      (node (ref "BUFFER1") (pin "14") (pinfunction "1Y3_14") (pintype "unspecified"))
      (node (ref "EXP1") (pin "7") (pinfunction "7_7") (pintype "unspecified"))
      (node (ref "RN4") (pin "2") (pinfunction "2_2") (pintype "input"))
    )
    (net (code "26") (name "BXBUSREQ") (class "Default")
      (node (ref "BUFFER1") (pin "5") (pinfunction "2Y3_5") (pintype "unspecified"))
      (node (ref "FAT-CAT") (pin "6") (pinfunction "PE1(PTCXY/SCL1/T4)_6") (pintype "bidirectional"))
    )
    (net (code "27") (name "BXCLK") (class "Default")
      (node (ref "EXP1") (pin "1") (pinfunction "1_1") (pintype "unspecified"))
      (node (ref "R68") (pin "2") (pinfunction "2_2") (pintype "input"))
    )
    (net (code "28") (name "BXIN") (class "Default")
      (node (ref "BUFFER1") (pin "12") (pinfunction "1Y4_12") (pintype "unspecified"))
      (node (ref "FAT-SPACER") (pin "14") (pinfunction "I/O_14") (pintype "unspecified"))
    )
    (net (code "29") (name "BXIRQ") (class "Default")
      (node (ref "BUFFER1") (pin "3") (pinfunction "2Y4_3") (pintype "unspecified"))
      (node (ref "FAT-CAT") (pin "22") (pinfunction "PE3(PTCY/ADC7/T3/MOSI1)_22") (pintype "bidirectional"))
    )
    (net (code "30") (name "BXRD") (class "Default")
      (node (ref "BUFFER1") (pin "7") (pinfunction "2Y2_7") (pintype "unspecified"))
      (node (ref "FAT-SPACER") (pin "19") (pinfunction "I/O_19") (pintype "unspecified"))
    )
    (net (code "31") (name "BXSLC") (class "Default")
      (node (ref "BUFFER1") (pin "18") (pinfunction "1Y1_18") (pintype "unspecified"))
      (node (ref "EXP1") (pin "6") (pinfunction "6_6") (pintype "unspecified"))
      (node (ref "RN5") (pin "3") (pinfunction "3_3") (pintype "input"))
    )
    (net (code "32") (name "BXWR") (class "Default")
      (node (ref "BUFFER1") (pin "9") (pinfunction "2Y1_9") (pintype "unspecified"))
      (node (ref "FAT-SPACER") (pin "17") (pinfunction "I/O_17") (pintype "unspecified"))
      (node (ref "OR") (pin "2") (pinfunction "B_2") (pintype "unspecified"))
    )
    (net (code "33") (name "C-TCK") (class "Default")
      (node (ref "FAT-CAVIA") (pin "62") (pinfunction "I/O/TCK_62") (pintype "unspecified"))
      (node (ref "JTAG-CAVIA") (pin "1") (pinfunction "1_1") (pintype "unspecified"))
    )
    (net (code "34") (name "C-TDI") (class "Default")
      (node (ref "FAT-CAVIA") (pin "4") (pinfunction "I/O/TDI_4") (pintype "unspecified"))
      (node (ref "JTAG-CAVIA") (pin "9") (pinfunction "9_9") (pintype "unspecified"))
      (node (ref "R19") (pin "1") (pinfunction "1_1") (pintype "input"))
    )
    (net (code "35") (name "C-TDO") (class "Default")
      (node (ref "FAT-CAVIA") (pin "73") (pinfunction "I/O/TDO_73") (pintype "unspecified"))
      (node (ref "JTAG-CAVIA") (pin "3") (pinfunction "3_3") (pintype "unspecified"))
    )
    (net (code "36") (name "C-TMS") (class "Default")
      (node (ref "FAT-CAVIA") (pin "15") (pinfunction "I/O/TMS_15") (pintype "unspecified"))
      (node (ref "JTAG-CAVIA") (pin "5") (pinfunction "5_5") (pintype "unspecified"))
      (node (ref "R20") (pin "1") (pinfunction "1_1") (pintype "input"))
    )
    (net (code "37") (name "CA0") (class "Default")
      (node (ref "FAT-CAVIA") (pin "32") (pinfunction "I/O_32") (pintype "unspecified"))
      (node (ref "VIDEOMEM") (pin "20") (pinfunction "I/O0R_20") (pintype "unspecified"))
    )
    (net (code "38") (name "CA1") (class "Default")
      (node (ref "FAT-CAVIA") (pin "31") (pinfunction "I/O_31") (pintype "unspecified"))
      (node (ref "VIDEOMEM") (pin "21") (pinfunction "I/O1R_21") (pintype "unspecified"))
    )
    (net (code "39") (name "CA2") (class "Default")
      (node (ref "FAT-CAVIA") (pin "30") (pinfunction "I/O_30") (pintype "unspecified"))
      (node (ref "VIDEOMEM") (pin "22") (pinfunction "I/O2R_22") (pintype "unspecified"))
    )
    (net (code "40") (name "CA3") (class "Default")
      (node (ref "FAT-CAVIA") (pin "29") (pinfunction "I/O_29") (pintype "unspecified"))
      (node (ref "VIDEOMEM") (pin "23") (pinfunction "I/O3R_23") (pintype "unspecified"))
    )
    (net (code "41") (name "CA4") (class "Default")
      (node (ref "FAT-CAVIA") (pin "28") (pinfunction "I/O_28") (pintype "unspecified"))
      (node (ref "VIDEOMEM") (pin "24") (pinfunction "I/O4R_24") (pintype "unspecified"))
    )
    (net (code "42") (name "CA5") (class "Default")
      (node (ref "FAT-CAVIA") (pin "27") (pinfunction "I/O_27") (pintype "unspecified"))
      (node (ref "VIDEOMEM") (pin "25") (pinfunction "I/O5R_25") (pintype "unspecified"))
    )
    (net (code "43") (name "CA6") (class "Default")
      (node (ref "FAT-CAVIA") (pin "25") (pinfunction "I/O_25") (pintype "unspecified"))
      (node (ref "VIDEOMEM") (pin "26") (pinfunction "I/O6R_26") (pintype "unspecified"))
    )
    (net (code "44") (name "CA7") (class "Default")
      (node (ref "FAT-CAVIA") (pin "24") (pinfunction "I/O_24") (pintype "unspecified"))
      (node (ref "VIDEOMEM") (pin "27") (pinfunction "I/O7R_27") (pintype "unspecified"))
    )
    (net (code "45") (name "CATCLK") (class "Default")
      (node (ref "FAT-CAT") (pin "7") (pinfunction "(XTAL1/TOSC1)PB6_7") (pintype "bidirectional"))
      (node (ref "R23") (pin "1") (pinfunction "1_1") (pintype "input"))
    )
    (net (code "46") (name "CATRST") (class "Default")
      (node (ref "C16") (pin "1") (pinfunction "1_1") (pintype "input"))
      (node (ref "FTDI") (pin "6") (pinfunction "6_6") (pintype "bidirectional"))
    )
    (net (code "47") (name "CB0") (class "Default")
      (node (ref "CHARMEM") (pin "20") (pinfunction "I/O0R_20") (pintype "unspecified"))
      (node (ref "FAT-SCUNK") (pin "25") (pinfunction "I/O_25") (pintype "unspecified"))
    )
    (net (code "48") (name "CB1") (class "Default")
      (node (ref "CHARMEM") (pin "21") (pinfunction "I/O1R_21") (pintype "unspecified"))
      (node (ref "FAT-SCUNK") (pin "24") (pinfunction "I/O_24") (pintype "unspecified"))
    )
    (net (code "49") (name "CB2") (class "Default")
      (node (ref "CHARMEM") (pin "22") (pinfunction "I/O2R_22") (pintype "unspecified"))
      (node (ref "FAT-SCUNK") (pin "23") (pinfunction "I/O_23") (pintype "unspecified"))
    )
    (net (code "50") (name "CB3") (class "Default")
      (node (ref "CHARMEM") (pin "23") (pinfunction "I/O3R_23") (pintype "unspecified"))
      (node (ref "FAT-SCUNK") (pin "22") (pinfunction "I/O_22") (pintype "unspecified"))
    )
    (net (code "51") (name "CB4") (class "Default")
      (node (ref "CHARMEM") (pin "24") (pinfunction "I/O4R_24") (pintype "unspecified"))
      (node (ref "FAT-SCUNK") (pin "21") (pinfunction "I/O_21") (pintype "unspecified"))
    )
    (net (code "52") (name "CB5") (class "Default")
      (node (ref "CHARMEM") (pin "25") (pinfunction "I/O5R_25") (pintype "unspecified"))
      (node (ref "FAT-SCUNK") (pin "20") (pinfunction "I/O_20") (pintype "unspecified"))
    )
    (net (code "53") (name "CB6") (class "Default")
      (node (ref "CHARMEM") (pin "26") (pinfunction "I/O6R_26") (pintype "unspecified"))
      (node (ref "FAT-SCUNK") (pin "19") (pinfunction "I/O_19") (pintype "unspecified"))
    )
    (net (code "54") (name "CB7") (class "Default")
      (node (ref "CHARMEM") (pin "27") (pinfunction "I/O7R_27") (pintype "unspecified"))
      (node (ref "FAT-SCUNK") (pin "17") (pinfunction "I/O_17") (pintype "unspecified"))
    )
    (net (code "55") (name "CBUSY") (class "Default")
      (node (ref "CHARMEM") (pin "48") (pinfunction "BUSYL#_48") (pintype "unspecified"))
      (node (ref "FAT-SPACER") (pin "47") (pinfunction "I/O_47") (pintype "unspecified"))
      (node (ref "R52") (pin "1") (pinfunction "1_1") (pintype "input"))
    )
    (net (code "56") (name "CCLK") (class "Default")
      (node (ref "FAT-CAVIA") (pin "87") (pinfunction "INPUT/GCLK1_87") (pintype "unspecified"))
      (node (ref "R17") (pin "1") (pinfunction "1_1") (pintype "input"))
    )
    (net (code "57") (name "CECM") (class "Default")
      (node (ref "CHARMEM") (pin "46") (pinfunction "CEL#_46") (pintype "unspecified"))
      (node (ref "FAT-SPACER") (pin "48") (pinfunction "I/O_48") (pintype "unspecified"))
      (node (ref "R54") (pin "1") (pinfunction "1_1") (pintype "input"))
    )
    (net (code "58") (name "CEHM") (class "Default")
      (node (ref "FAT-SPACER") (pin "52") (pinfunction "I/O_52") (pintype "unspecified"))
      (node (ref "HIGH-MEM") (pin "20") (pinfunction "CS#_20") (pintype "unspecified"))
      (node (ref "R57") (pin "1") (pinfunction "1_1") (pintype "input"))
    )
    (net (code "59") (name "CELM") (class "Default")
      (node (ref "FAT-SPACER") (pin "54") (pinfunction "I/O_54") (pintype "unspecified"))
      (node (ref "LOW-MEM") (pin "20") (pinfunction "CS#_20") (pintype "unspecified"))
      (node (ref "R59") (pin "1") (pinfunction "1_1") (pintype "input"))
    )
    (net (code "60") (name "CEVM") (class "Default")
      (node (ref "FAT-SPACER") (pin "44") (pinfunction "I/O_44") (pintype "unspecified"))
      (node (ref "R60") (pin "1") (pinfunction "1_1") (pintype "input"))
      (node (ref "VIDEOMEM") (pin "46") (pinfunction "CEL#_46") (pintype "unspecified"))
    )
    (net (code "61") (name "CLK6502") (class "Default")
      (node (ref "R25") (pin "1") (pinfunction "1_1") (pintype "input"))
      (node (ref "W65C02S") (pin "35") (pinfunction "PHI2_35") (pintype "unspecified"))
    )
    (net (code "62") (name "CLKZ80") (class "Default")
      (node (ref "R24") (pin "1") (pinfunction "1_1") (pintype "input"))
      (node (ref "Z80") (pin "1") (pinfunction "CLK_1") (pintype "unspecified"))
    )
    (net (code "63") (name "CMA0") (class "Default")
      (node (ref "CHARMEM") (pin "38") (pinfunction "A0R_38") (pintype "unspecified"))
      (node (ref "FAT-CAVIA") (pin "33") (pinfunction "I/O_33") (pintype "unspecified"))
    )
    (net (code "64") (name "CMA1") (class "Default")
      (node (ref "CHARMEM") (pin "37") (pinfunction "A1R_37") (pintype "unspecified"))
      (node (ref "FAT-CAVIA") (pin "35") (pinfunction "I/O_35") (pintype "unspecified"))
    )
    (net (code "65") (name "CMA2") (class "Default")
      (node (ref "CHARMEM") (pin "36") (pinfunction "A2R_36") (pintype "unspecified"))
      (node (ref "FAT-CAVIA") (pin "36") (pinfunction "I/O_36") (pintype "unspecified"))
    )
    (net (code "66") (name "CMA3") (class "Default")
      (node (ref "CHARMEM") (pin "35") (pinfunction "A3R_35") (pintype "unspecified"))
      (node (ref "FAT-CAVIA") (pin "40") (pinfunction "I/O_40") (pintype "unspecified"))
    )
    (net (code "67") (name "CMA4") (class "Default")
      (node (ref "CHARMEM") (pin "34") (pinfunction "A4R_34") (pintype "unspecified"))
      (node (ref "FAT-CAVIA") (pin "41") (pinfunction "I/0/PD2_41") (pintype "unspecified"))
    )
    (net (code "68") (name "CMA5") (class "Default")
      (node (ref "CHARMEM") (pin "33") (pinfunction "A5R_33") (pintype "unspecified"))
      (node (ref "FAT-CAVIA") (pin "42") (pinfunction "I/O_42") (pintype "unspecified"))
    )
    (net (code "69") (name "CMA6") (class "Default")
      (node (ref "CHARMEM") (pin "32") (pinfunction "A6R_32") (pintype "unspecified"))
      (node (ref "FAT-CAVIA") (pin "44") (pinfunction "I/O_44") (pintype "unspecified"))
    )
    (net (code "70") (name "CMA7") (class "Default")
      (node (ref "CHARMEM") (pin "31") (pinfunction "A7R_31") (pintype "unspecified"))
      (node (ref "FAT-CAVIA") (pin "45") (pinfunction "I/O_45") (pintype "unspecified"))
    )
    (net (code "71") (name "CMA8") (class "Default")
      (node (ref "CHARMEM") (pin "30") (pinfunction "A8R_30") (pintype "unspecified"))
      (node (ref "FAT-CAVIA") (pin "46") (pinfunction "I/O_46") (pintype "unspecified"))
    )
    (net (code "72") (name "CMA9") (class "Default")
      (node (ref "CHARMEM") (pin "29") (pinfunction "A9R_29") (pintype "unspecified"))
      (node (ref "FAT-CAVIA") (pin "47") (pinfunction "I/O_47") (pintype "unspecified"))
    )
    (net (code "73") (name "CMA10") (class "Default")
      (node (ref "CHARMEM") (pin "40") (pinfunction "A10R_40") (pintype "unspecified"))
      (node (ref "FAT-CAVIA") (pin "48") (pinfunction "I/O_48") (pintype "unspecified"))
    )
    (net (code "74") (name "CPUGO") (class "Default")
      (node (ref "FAT-CAT") (pin "11") (pinfunction "(AIN1/PTCXY)PD7_11") (pintype "bidirectional"))
      (node (ref "FAT-SPACER") (pin "37") (pinfunction "I/O_37") (pintype "unspecified"))
    )
    (net (code "75") (name "CPUIRQ") (class "Default")
      (node (ref "FAT-CAT") (pin "10") (pinfunction "(OC0A/AIN0/PTCXY)PD6_10") (pintype "bidirectional"))
      (node (ref "FAT-SPACER") (pin "36") (pinfunction "I/O_36") (pintype "unspecified"))
    )
    (net (code "76") (name "CPURST") (class "Default")
      (node (ref "FAT-CAT") (pin "12") (pinfunction "(CLKO/ICP1/PTCXY)PB0_12") (pintype "bidirectional"))
      (node (ref "FAT-SPACER") (pin "40") (pinfunction "I/O_40") (pintype "unspecified"))
    )
    (net (code "77") (name "CPUSLC") (class "Default")
      (node (ref "FAT-CAT") (pin "9") (pinfunction "(OC0B/T1/PTCXY)PD5_9") (pintype "bidirectional"))
      (node (ref "FAT-SPACER") (pin "35") (pinfunction "I/O_35") (pintype "unspecified"))
    )
    (net (code "78") (name "CPUSPD") (class "Default")
      (node (ref "FAT-CAT") (pin "13") (pinfunction "(OC1A/PTCXY)PB1_13") (pintype "bidirectional"))
      (node (ref "FAT-SPACER") (pin "33") (pinfunction "I/O_33") (pintype "unspecified"))
    )
    (net (code "79") (name "CRST") (class "Default")
      (node (ref "FAT-CAVIA") (pin "6") (pinfunction "I/O_6") (pintype "unspecified"))
      (node (ref "FAT-SCUNK") (pin "81") (pinfunction "I/O_81") (pintype "unspecified"))
    )
    (net (code "80") (name "CS") (class "Default")
      (node (ref "FAT-CAT") (pin "14") (pinfunction "(OC1B/SS0/PTCXY)PB2_14") (pintype "bidirectional"))
      (node (ref "R39") (pin "2") (pinfunction "2_2") (pintype "input"))
    )
    (net (code "81") (name "CS_LLS") (class "Default")
      (node (ref "LVLSHF") (pin "8") (pinfunction "3Y_8") (pintype "unspecified"))
      (node (ref "SD") (pin "2") (pinfunction "CD/DAT3_2") (pintype "unspecified"))
    )
    (net (code "82") (name "D0") (class "Default")
      (node (ref "BT1") (pin "9") (pinfunction "A8_9") (pintype "unspecified"))
      (node (ref "CHARMEM") (pin "10") (pinfunction "I/O0L_10") (pintype "unspecified"))
      (node (ref "FAT-SPACER") (pin "76") (pinfunction "I/O_76") (pintype "unspecified"))
      (node (ref "HIGH-MEM") (pin "11") (pinfunction "DQ0_11") (pintype "unspecified"))
      (node (ref "LOW-MEM") (pin "11") (pinfunction "DQ0_11") (pintype "unspecified"))
      (node (ref "RN1") (pin "9") (pinfunction "9_9") (pintype "input"))
      (node (ref "VIDEOMEM") (pin "10") (pinfunction "I/O0L_10") (pintype "unspecified"))
      (node (ref "W65C02S") (pin "30") (pinfunction "D0_30") (pintype "unspecified"))
      (node (ref "Z80") (pin "9") (pinfunction "D0_9") (pintype "unspecified"))
    )
    (net (code "83") (name "D1") (class "Default")
      (node (ref "BT1") (pin "8") (pinfunction "A7_8") (pintype "unspecified"))
      (node (ref "CHARMEM") (pin "11") (pinfunction "I/O1L_11") (pintype "unspecified"))
      (node (ref "FAT-SPACER") (pin "77") (pinfunction "I/O_77") (pintype "unspecified"))
      (node (ref "HIGH-MEM") (pin "12") (pinfunction "DQ1_12") (pintype "unspecified"))
      (node (ref "LOW-MEM") (pin "12") (pinfunction "DQ1_12") (pintype "unspecified"))
      (node (ref "RN1") (pin "8") (pinfunction "8_8") (pintype "input"))
      (node (ref "VIDEOMEM") (pin "11") (pinfunction "I/O1L_11") (pintype "unspecified"))
      (node (ref "W65C02S") (pin "29") (pinfunction "D1_29") (pintype "unspecified"))
      (node (ref "Z80") (pin "10") (pinfunction "D1_10") (pintype "unspecified"))
    )
    (net (code "84") (name "D2") (class "Default")
      (node (ref "BT1") (pin "7") (pinfunction "A6_7") (pintype "unspecified"))
      (node (ref "CHARMEM") (pin "12") (pinfunction "I/O2L_12") (pintype "unspecified"))
      (node (ref "FAT-SPACER") (pin "78") (pinfunction "I/O_78") (pintype "unspecified"))
      (node (ref "HIGH-MEM") (pin "13") (pinfunction "DQ2_13") (pintype "unspecified"))
      (node (ref "LOW-MEM") (pin "13") (pinfunction "DQ2_13") (pintype "unspecified"))
      (node (ref "RN1") (pin "7") (pinfunction "7_7") (pintype "input"))
      (node (ref "VIDEOMEM") (pin "12") (pinfunction "I/O2L_12") (pintype "unspecified"))
      (node (ref "W65C02S") (pin "28") (pinfunction "D2_28") (pintype "unspecified"))
      (node (ref "Z80") (pin "7") (pinfunction "D2_7") (pintype "unspecified"))
    )
    (net (code "85") (name "D3") (class "Default")
      (node (ref "BT1") (pin "6") (pinfunction "A5_6") (pintype "unspecified"))
      (node (ref "CHARMEM") (pin "13") (pinfunction "I/O3L_13") (pintype "unspecified"))
      (node (ref "FAT-SPACER") (pin "79") (pinfunction "I/O_79") (pintype "unspecified"))
      (node (ref "HIGH-MEM") (pin "15") (pinfunction "DQ3_15") (pintype "unspecified"))
      (node (ref "LOW-MEM") (pin "15") (pinfunction "DQ3_15") (pintype "unspecified"))
      (node (ref "RN1") (pin "6") (pinfunction "6_6") (pintype "input"))
      (node (ref "VIDEOMEM") (pin "13") (pinfunction "I/O3L_13") (pintype "unspecified"))
      (node (ref "W65C02S") (pin "27") (pinfunction "D3_27") (pintype "unspecified"))
      (node (ref "Z80") (pin "3") (pinfunction "D3_3") (pintype "unspecified"))
    )
    (net (code "86") (name "D4") (class "Default")
      (node (ref "BT1") (pin "5") (pinfunction "A4_5") (pintype "unspecified"))
      (node (ref "CHARMEM") (pin "14") (pinfunction "I/O4L_14") (pintype "unspecified"))
      (node (ref "FAT-SPACER") (pin "80") (pinfunction "I/O_80") (pintype "unspecified"))
      (node (ref "HIGH-MEM") (pin "16") (pinfunction "DQ4_16") (pintype "unspecified"))
      (node (ref "LOW-MEM") (pin "16") (pinfunction "DQ4_16") (pintype "unspecified"))
      (node (ref "RN1") (pin "5") (pinfunction "5_5") (pintype "input"))
      (node (ref "VIDEOMEM") (pin "14") (pinfunction "I/O4L_14") (pintype "unspecified"))
      (node (ref "W65C02S") (pin "26") (pinfunction "D4_26") (pintype "unspecified"))
      (node (ref "Z80") (pin "2") (pinfunction "D4_2") (pintype "unspecified"))
    )
    (net (code "87") (name "D5") (class "Default")
      (node (ref "BT1") (pin "4") (pinfunction "A3_4") (pintype "unspecified"))
      (node (ref "CHARMEM") (pin "15") (pinfunction "I/O5L_15") (pintype "unspecified"))
      (node (ref "FAT-SPACER") (pin "81") (pinfunction "I/O_81") (pintype "unspecified"))
      (node (ref "HIGH-MEM") (pin "17") (pinfunction "DQ5_17") (pintype "unspecified"))
      (node (ref "LOW-MEM") (pin "17") (pinfunction "DQ5_17") (pintype "unspecified"))
      (node (ref "RN1") (pin "4") (pinfunction "4_4") (pintype "input"))
      (node (ref "VIDEOMEM") (pin "15") (pinfunction "I/O5L_15") (pintype "unspecified"))
      (node (ref "W65C02S") (pin "25") (pinfunction "D5_25") (pintype "unspecified"))
      (node (ref "Z80") (pin "4") (pinfunction "D5_4") (pintype "unspecified"))
    )
    (net (code "88") (name "D6") (class "Default")
      (node (ref "BT1") (pin "3") (pinfunction "A2_3") (pintype "unspecified"))
      (node (ref "CHARMEM") (pin "16") (pinfunction "I/O6L_16") (pintype "unspecified"))
      (node (ref "FAT-SPACER") (pin "83") (pinfunction "I/O_83") (pintype "unspecified"))
      (node (ref "HIGH-MEM") (pin "18") (pinfunction "DQ6_18") (pintype "unspecified"))
      (node (ref "LOW-MEM") (pin "18") (pinfunction "DQ6_18") (pintype "unspecified"))
      (node (ref "RN1") (pin "3") (pinfunction "3_3") (pintype "input"))
      (node (ref "VIDEOMEM") (pin "16") (pinfunction "I/O6L_16") (pintype "unspecified"))
      (node (ref "W65C02S") (pin "24") (pinfunction "D6_24") (pintype "unspecified"))
      (node (ref "Z80") (pin "5") (pinfunction "D6_5") (pintype "unspecified"))
    )
    (net (code "89") (name "D7") (class "Default")
      (node (ref "BT1") (pin "2") (pinfunction "A1_2") (pintype "unspecified"))
      (node (ref "CHARMEM") (pin "17") (pinfunction "I/O7L_17") (pintype "unspecified"))
      (node (ref "FAT-SPACER") (pin "84") (pinfunction "I/O_84") (pintype "unspecified"))
      (node (ref "HIGH-MEM") (pin "19") (pinfunction "DQ7_19") (pintype "unspecified"))
      (node (ref "LOW-MEM") (pin "19") (pinfunction "DQ7_19") (pintype "unspecified"))
      (node (ref "RN1") (pin "2") (pinfunction "2_2") (pintype "input"))
      (node (ref "VIDEOMEM") (pin "17") (pinfunction "I/O7L_17") (pintype "unspecified"))
      (node (ref "W65C02S") (pin "23") (pinfunction "D7_23") (pintype "unspecified"))
      (node (ref "Z80") (pin "8") (pinfunction "D7_8") (pintype "unspecified"))
    )
    (net (code "90") (name "DI_LLS") (class "Default")
      (node (ref "LVLSHF") (pin "3") (pinfunction "1Y_3") (pintype "unspecified"))
      (node (ref "SD") (pin "3") (pinfunction "CMD_3") (pintype "unspecified"))
    )
    (net (code "91") (name "DO_LLS") (class "Default")
      (node (ref "R38") (pin "2") (pinfunction "2_2") (pintype "input"))
      (node (ref "SD") (pin "7") (pinfunction "DAT0_7") (pintype "unspecified"))
    )
    (net (code "92") (name "DPMCE") (class "Default")
      (node (ref "CHARMEM") (pin "44") (pinfunction "CER#_44") (pintype "unspecified"))
      (node (ref "FAT-SCUNK") (pin "93") (pinfunction "I/O_93") (pintype "unspecified"))
      (node (ref "R18") (pin "1") (pinfunction "1_1") (pintype "input"))
      (node (ref "VIDEOMEM") (pin "44") (pinfunction "CER#_44") (pintype "unspecified"))
    )
    (net (code "93") (name "FREE") (class "Default")
      (node (ref "FAT-CAT") (pin "19") (pinfunction "PE2(PTCY/ADC6/ICP3/SS1)_19") (pintype "bidirectional"))
      (node (ref "FAT-SPACER") (pin "21") (pinfunction "I/O_21") (pintype "unspecified"))
    )
    (net (code "94") (name "FREE1") (class "Default")
      (node (ref "FAT-CAVIA") (pin "88") (pinfunction "INPUT/OE1_88") (pintype "unspecified"))
      (node (ref "FAT-SCUNK") (pin "49") (pinfunction "I/O_49") (pintype "unspecified"))
    )
    (net (code "95") (name "FREE2") (class "Default")
      (node (ref "FAT-CAVIA") (pin "89") (pinfunction "INPUT/GCLR_89") (pintype "unspecified"))
      (node (ref "FAT-SCUNK") (pin "48") (pinfunction "I/O_48") (pintype "unspecified"))
    )
    (net (code "96") (name "FREE3") (class "Default")
      (node (ref "FAT-CAVIA") (pin "90") (pinfunction "INPUT/OE2/GCLK2_90") (pintype "unspecified"))
      (node (ref "FAT-SCUNK") (pin "47") (pinfunction "I/O_47") (pintype "unspecified"))
    )
    (net (code "97") (name "FREE4") (class "Default")
      (node (ref "FAT-CAVIA") (pin "92") (pinfunction "I/O_92") (pintype "unspecified"))
      (node (ref "FAT-SCUNK") (pin "46") (pinfunction "I/O_46") (pintype "unspecified"))
    )
    (net (code "98") (name "FREE5") (class "Default")
      (node (ref "FAT-CAVIA") (pin "93") (pinfunction "I/O_93") (pintype "unspecified"))
      (node (ref "FAT-SCUNK") (pin "45") (pinfunction "I/O_45") (pintype "unspecified"))
    )
    (net (code "99") (name "FREE6") (class "Default")
      (node (ref "FAT-CAVIA") (pin "63") (pinfunction "I/O_63") (pintype "unspecified"))
      (node (ref "FAT-SCUNK") (pin "70") (pinfunction "I/O_70") (pintype "unspecified"))
    )
    (net (code "100") (name "FREE7") (class "Default")
      (node (ref "FAT-CAVIA") (pin "64") (pinfunction "I/O_64") (pintype "unspecified"))
      (node (ref "FAT-SCUNK") (pin "69") (pinfunction "I/O_69") (pintype "unspecified"))
    )
    (net (code "101") (name "FREE8") (class "Default")
      (node (ref "FAT-CAVIA") (pin "65") (pinfunction "I/O_65") (pintype "unspecified"))
      (node (ref "FAT-SCUNK") (pin "68") (pinfunction "I/O_68") (pintype "unspecified"))
    )
    (net (code "102") (name "FREE9") (class "Default")
      (node (ref "FAT-CAVIA") (pin "75") (pinfunction "I/O_75") (pintype "unspecified"))
      (node (ref "FAT-SCUNK") (pin "64") (pinfunction "I/O_64") (pintype "unspecified"))
    )
    (net (code "103") (name "FREE10") (class "Default")
      (node (ref "FAT-CAVIA") (pin "76") (pinfunction "I/O_76") (pintype "unspecified"))
      (node (ref "FAT-SCUNK") (pin "50") (pinfunction "I/O_50") (pintype "unspecified"))
    )
    (net (code "104") (name "FREE11") (class "Default")
      (node (ref "FAT-CAVIA") (pin "77") (pinfunction "I/O_77") (pintype "unspecified"))
      (node (ref "FAT-SCUNK") (pin "52") (pinfunction "I/O_52") (pintype "unspecified"))
    )
    (net (code "105") (name "FREE12") (class "Default")
      (node (ref "FAT-CAVIA") (pin "78") (pinfunction "I/O_78") (pintype "unspecified"))
      (node (ref "FAT-SCUNK") (pin "42") (pinfunction "I/O_42") (pintype "unspecified"))
    )
    (net (code "106") (name "GND") (class "Default")
      (node (ref "BOOTLD") (pin "3") (pinfunction "3_3") (pintype "unspecified"))
      (node (ref "BT1") (pin "10") (pinfunction "GND_10") (pintype "unspecified"))
      (node (ref "BT2") (pin "10") (pinfunction "GND_10") (pintype "unspecified"))
      (node (ref "BT3") (pin "10") (pinfunction "GND_10") (pintype "unspecified"))
      (node (ref "BUFFER1") (pin "1") (pinfunction "1OE#_1") (pintype "unspecified"))
      (node (ref "BUFFER1") (pin "10") (pinfunction "GND_10") (pintype "unspecified"))
      (node (ref "BUFFER1") (pin "19") (pinfunction "2OE#_19") (pintype "unspecified"))
      (node (ref "BUZZ-DIS") (pin "2") (pinfunction "2_2") (pintype "unspecified"))
      (node (ref "BUZZER") (pin "2") (pinfunction "-_2") (pintype "unspecified"))
      (node (ref "C1") (pin "1") (pinfunction "1_1") (pintype "input"))
      (node (ref "C10") (pin "2") (pinfunction "-_2") (pintype "bidirectional"))
      (node (ref "C11") (pin "1") (pinfunction "1_1") (pintype "input"))
      (node (ref "C12") (pin "1") (pinfunction "1_1") (pintype "input"))
      (node (ref "C13") (pin "1") (pinfunction "1_1") (pintype "input"))
      (node (ref "C14") (pin "1") (pinfunction "1_1") (pintype "input"))
      (node (ref "C15") (pin "1") (pinfunction "1_1") (pintype "input"))
      (node (ref "C17") (pin "1") (pinfunction "1_1") (pintype "input"))
      (node (ref "C18") (pin "1") (pinfunction "1_1") (pintype "input"))
      (node (ref "C19") (pin "1") (pinfunction "1_1") (pintype "input"))
      (node (ref "C2") (pin "1") (pinfunction "1_1") (pintype "input"))
      (node (ref "C20") (pin "1") (pinfunction "1_1") (pintype "input"))
      (node (ref "C21") (pin "1") (pinfunction "1_1") (pintype "input"))
      (node (ref "C22") (pin "1") (pinfunction "1_1") (pintype "input"))
      (node (ref "C23") (pin "1") (pinfunction "1_1") (pintype "input"))
      (node (ref "C24") (pin "1") (pinfunction "1_1") (pintype "input"))
      (node (ref "C25") (pin "1") (pinfunction "1_1") (pintype "input"))
      (node (ref "C26") (pin "1") (pinfunction "1_1") (pintype "input"))
      (node (ref "C27") (pin "1") (pinfunction "1_1") (pintype "input"))
      (node (ref "C28") (pin "1") (pinfunction "1_1") (pintype "input"))
      (node (ref "C29") (pin "1") (pinfunction "1_1") (pintype "input"))
      (node (ref "C3") (pin "1") (pinfunction "1_1") (pintype "input"))
      (node (ref "C30") (pin "1") (pinfunction "1_1") (pintype "input"))
      (node (ref "C31") (pin "1") (pinfunction "1_1") (pintype "input"))
      (node (ref "C32") (pin "1") (pinfunction "1_1") (pintype "input"))
      (node (ref "C33") (pin "1") (pinfunction "1_1") (pintype "input"))
      (node (ref "C34") (pin "1") (pinfunction "1_1") (pintype "input"))
      (node (ref "C35") (pin "1") (pinfunction "1_1") (pintype "input"))
      (node (ref "C36") (pin "1") (pinfunction "1_1") (pintype "input"))
      (node (ref "C37") (pin "1") (pinfunction "1_1") (pintype "input"))
      (node (ref "C38") (pin "1") (pinfunction "1_1") (pintype "input"))
      (node (ref "C39") (pin "1") (pinfunction "1_1") (pintype "input"))
      (node (ref "C4") (pin "1") (pinfunction "1_1") (pintype "input"))
      (node (ref "C40") (pin "1") (pinfunction "1_1") (pintype "input"))
      (node (ref "C41") (pin "1") (pinfunction "1_1") (pintype "input"))
      (node (ref "C42") (pin "1") (pinfunction "1_1") (pintype "input"))
      (node (ref "C43") (pin "1") (pinfunction "1_1") (pintype "input"))
      (node (ref "C44") (pin "1") (pinfunction "1_1") (pintype "input"))
      (node (ref "C45") (pin "1") (pinfunction "1_1") (pintype "input"))
      (node (ref "C46") (pin "1") (pinfunction "1_1") (pintype "input"))
      (node (ref "C47") (pin "1") (pinfunction "1_1") (pintype "input"))
      (node (ref "C48") (pin "1") (pinfunction "1_1") (pintype "input"))
      (node (ref "C49") (pin "1") (pinfunction "1_1") (pintype "input"))
      (node (ref "C5") (pin "1") (pinfunction "1_1") (pintype "input"))
      (node (ref "C50") (pin "1") (pinfunction "1_1") (pintype "input"))
      (node (ref "C51") (pin "1") (pinfunction "1_1") (pintype "input"))
      (node (ref "C52") (pin "1") (pinfunction "1_1") (pintype "input"))
      (node (ref "C53") (pin "1") (pinfunction "1_1") (pintype "input"))
      (node (ref "C54") (pin "1") (pinfunction "1_1") (pintype "input"))
      (node (ref "C55") (pin "1") (pinfunction "1_1") (pintype "input"))
      (node (ref "C56") (pin "1") (pinfunction "1_1") (pintype "input"))
      (node (ref "C57") (pin "1") (pinfunction "1_1") (pintype "input"))
      (node (ref "C58") (pin "1") (pinfunction "1_1") (pintype "input"))
      (node (ref "C59") (pin "1") (pinfunction "1_1") (pintype "input"))
      (node (ref "C6") (pin "1") (pinfunction "1_1") (pintype "input"))
      (node (ref "C60") (pin "1") (pinfunction "1_1") (pintype "input"))
      (node (ref "C61") (pin "1") (pinfunction "1_1") (pintype "input"))
      (node (ref "C62") (pin "1") (pinfunction "1_1") (pintype "input"))
      (node (ref "C63") (pin "1") (pinfunction "1_1") (pintype "input"))
      (node (ref "C64") (pin "1") (pinfunction "1_1") (pintype "input"))
      (node (ref "C65") (pin "1") (pinfunction "1_1") (pintype "input"))
      (node (ref "C66") (pin "1") (pinfunction "1_1") (pintype "input"))
      (node (ref "C67") (pin "1") (pinfunction "1_1") (pintype "input"))
      (node (ref "C68") (pin "1") (pinfunction "1_1") (pintype "input"))
      (node (ref "C69") (pin "1") (pinfunction "1_1") (pintype "input"))
      (node (ref "C7") (pin "2") (pinfunction "2_2") (pintype "input"))
      (node (ref "C8") (pin "1") (pinfunction "1_1") (pintype "input"))
      (node (ref "C9") (pin "1") (pinfunction "1_1") (pintype "input"))
      (node (ref "CHARMEM") (pin "19") (pinfunction "GND_19") (pintype "unspecified"))
      (node (ref "CHARMEM") (pin "39") (pinfunction "OER#_39") (pintype "unspecified"))
      (node (ref "CLAMP1") (pin "2") (pinfunction "A_2") (pintype "unspecified"))
      (node (ref "D1") (pin "1") (pinfunction "1_1") (pintype "unspecified"))
      (node (ref "ESD1") (pin "1") (pinfunction "1_1") (pintype "unspecified"))
      (node (ref "ESD2") (pin "1") (pinfunction "1_1") (pintype "unspecified"))
      (node (ref "ESD3") (pin "1") (pinfunction "1_1") (pintype "unspecified"))
      (node (ref "ESD4") (pin "2") (pinfunction "2_2") (pintype "unspecified"))
      (node (ref "ESD5") (pin "1") (pinfunction "1_1") (pintype "unspecified"))
      (node (ref "ESD6") (pin "2") (pinfunction "2_2") (pintype "unspecified"))
      (node (ref "ESD7") (pin "1") (pinfunction "1_1") (pintype "unspecified"))
      (node (ref "EXP1") (pin "2") (pinfunction "2_2") (pintype "unspecified"))
      (node (ref "EXP1") (pin "36") (pinfunction "36_36") (pintype "unspecified"))
      (node (ref "EXP1") (pin "38") (pinfunction "38_38") (pintype "unspecified"))
      (node (ref "EXP1") (pin "40") (pinfunction "40_40") (pintype "unspecified"))
      (node (ref "FAT-CAT") (pin "20") (pinfunction "AREF_20") (pintype "bidirectional"))
      (node (ref "FAT-CAT") (pin "21") (pinfunction "GND_21") (pintype "bidirectional"))
      (node (ref "FAT-CAT") (pin "5") (pinfunction "GND_5") (pintype "bidirectional"))
      (node (ref "FAT-CAVIA") (pin "11") (pinfunction "GND_11") (pintype "unspecified"))
      (node (ref "FAT-CAVIA") (pin "26") (pinfunction "GND_26") (pintype "unspecified"))
      (node (ref "FAT-CAVIA") (pin "38") (pinfunction "GND_38") (pintype "unspecified"))
      (node (ref "FAT-CAVIA") (pin "43") (pinfunction "GND_43") (pintype "unspecified"))
      (node (ref "FAT-CAVIA") (pin "59") (pinfunction "GND_59") (pintype "unspecified"))
      (node (ref "FAT-CAVIA") (pin "74") (pinfunction "GND_74") (pintype "unspecified"))
      (node (ref "FAT-CAVIA") (pin "86") (pinfunction "GND_86") (pintype "unspecified"))
      (node (ref "FAT-CAVIA") (pin "95") (pinfunction "GND_95") (pintype "unspecified"))
      (node (ref "FAT-SCUNK") (pin "11") (pinfunction "GND_11") (pintype "unspecified"))
      (node (ref "FAT-SCUNK") (pin "26") (pinfunction "GND_26") (pintype "unspecified"))
      (node (ref "FAT-SCUNK") (pin "38") (pinfunction "GND_38") (pintype "unspecified"))
      (node (ref "FAT-SCUNK") (pin "43") (pinfunction "GND_43") (pintype "unspecified"))
      (node (ref "FAT-SCUNK") (pin "59") (pinfunction "GND_59") (pintype "unspecified"))
      (node (ref "FAT-SCUNK") (pin "74") (pinfunction "GND_74") (pintype "unspecified"))
      (node (ref "FAT-SCUNK") (pin "86") (pinfunction "GND_86") (pintype "unspecified"))
      (node (ref "FAT-SCUNK") (pin "95") (pinfunction "GND_95") (pintype "unspecified"))
      (node (ref "FAT-SPACER") (pin "11") (pinfunction "GND_11") (pintype "unspecified"))
      (node (ref "FAT-SPACER") (pin "26") (pinfunction "GND_26") (pintype "unspecified"))
      (node (ref "FAT-SPACER") (pin "38") (pinfunction "GND_38") (pintype "unspecified"))
      (node (ref "FAT-SPACER") (pin "43") (pinfunction "GND_43") (pintype "unspecified"))
      (node (ref "FAT-SPACER") (pin "59") (pinfunction "GND_59") (pintype "unspecified"))
      (node (ref "FAT-SPACER") (pin "74") (pinfunction "GND_74") (pintype "unspecified"))
      (node (ref "FAT-SPACER") (pin "86") (pinfunction "GND_86") (pintype "unspecified"))
      (node (ref "FAT-SPACER") (pin "95") (pinfunction "GND_95") (pintype "unspecified"))
      (node (ref "FB1") (pin "2") (pinfunction "2_2") (pintype "unspecified"))
      (node (ref "FTDI") (pin "1") (pinfunction "1_1") (pintype "bidirectional"))
      (node (ref "HIGH-MEM") (pin "14") (pinfunction "GND_14") (pintype "unspecified"))
      (node (ref "JTAG-CAVIA") (pin "10") (pinfunction "10_10") (pintype "unspecified"))
      (node (ref "JTAG-CAVIA") (pin "2") (pinfunction "2_2") (pintype "unspecified"))
      (node (ref "JTAG-SCUNK") (pin "10") (pinfunction "10_10") (pintype "unspecified"))
      (node (ref "JTAG-SCUNK") (pin "2") (pinfunction "2_2") (pintype "unspecified"))
      (node (ref "JTAG-SPACER") (pin "10") (pinfunction "10_10") (pintype "unspecified"))
      (node (ref "JTAG-SPACER") (pin "2") (pinfunction "2_2") (pintype "unspecified"))
      (node (ref "LDO") (pin "1") (pinfunction "ADJ/GND_1") (pintype "passive"))
      (node (ref "LOW-MEM") (pin "14") (pinfunction "GND_14") (pintype "unspecified"))
      (node (ref "LVLSHF") (pin "1") (pinfunction "1OE#_1") (pintype "unspecified"))
      (node (ref "LVLSHF") (pin "10") (pinfunction "3OE#_10") (pintype "unspecified"))
      (node (ref "LVLSHF") (pin "13") (pinfunction "4OE#_13") (pintype "unspecified"))
      (node (ref "LVLSHF") (pin "4") (pinfunction "2OE#_4") (pintype "unspecified"))
      (node (ref "LVLSHF") (pin "7") (pinfunction "GND_7") (pintype "unspecified"))
      (node (ref "OR") (pin "3") (pinfunction "GND_3") (pintype "unspecified"))
      (node (ref "OSC1") (pin "2") (pinfunction "GND_2") (pintype "input"))
      (node (ref "OSC2") (pin "2") (pinfunction "GND_2") (pintype "unspecified"))
      (node (ref "PS/2") (pin "4") (pinfunction "GND_4") (pintype "unspecified"))
      (node (ref "PWR1") (pin "1") (pinfunction "K_1") (pintype "input"))
      (node (ref "Q1") (pin "2") (pinfunction "E_2") (pintype "input"))
      (node (ref "Q2") (pin "2") (pinfunction "E_2") (pintype "input"))
      (node (ref "R11") (pin "2") (pinfunction "2_2") (pintype "input"))
      (node (ref "R8") (pin "1") (pinfunction "1_1") (pintype "input"))
      (node (ref "SD") (pin "10") (pinfunction "GND_10") (pintype "unspecified"))
      (node (ref "SD") (pin "11") (pinfunction "GND_11") (pintype "unspecified"))
      (node (ref "SD") (pin "12") (pinfunction "GND_12") (pintype "unspecified"))
      (node (ref "SD") (pin "13") (pinfunction "GND_13") (pintype "unspecified"))
      (node (ref "SD") (pin "6") (pinfunction "VSS_6") (pintype "unspecified"))
      (node (ref "U1") (pin "3") (pinfunction "GND_3") (pintype "unspecified"))
      (node (ref "U10") (pin "3") (pinfunction "GND_3") (pintype "unspecified"))
      (node (ref "U2") (pin "3") (pinfunction "GND_3") (pintype "unspecified"))
      (node (ref "U3") (pin "3") (pinfunction "GND_3") (pintype "unspecified"))
      (node (ref "U4") (pin "1") (pinfunction "OE_1") (pintype "unspecified"))
      (node (ref "U4") (pin "3") (pinfunction "GND_3") (pintype "unspecified"))
      (node (ref "U5") (pin "1") (pinfunction "OE_1") (pintype "unspecified"))
      (node (ref "U5") (pin "3") (pinfunction "GND_3") (pintype "unspecified"))
      (node (ref "U6") (pin "1") (pinfunction "OE_1") (pintype "unspecified"))
      (node (ref "U6") (pin "3") (pinfunction "GND_3") (pintype "unspecified"))
      (node (ref "U7") (pin "1") (pinfunction "OE_1") (pintype "unspecified"))
      (node (ref "U7") (pin "3") (pinfunction "GND_3") (pintype "unspecified"))
      (node (ref "U8") (pin "1") (pinfunction "OE_1") (pintype "unspecified"))
      (node (ref "U8") (pin "3") (pinfunction "GND_3") (pintype "unspecified"))
      (node (ref "U9") (pin "1") (pinfunction "OE_1") (pintype "unspecified"))
      (node (ref "U9") (pin "3") (pinfunction "GND_3") (pintype "unspecified"))
      (node (ref "USB-C") (pin "1") (pinfunction "EP_1") (pintype "unspecified"))
      (node (ref "USB-C") (pin "2") (pinfunction "EP_2") (pintype "unspecified"))
      (node (ref "USB-C") (pin "3") (pinfunction "EP_3") (pintype "unspecified"))
      (node (ref "USB-C") (pin "4") (pinfunction "EP_4") (pintype "unspecified"))
      (node (ref "USB-C") (pin "A1") (pinfunction "GND_A1") (pintype "unspecified"))
      (node (ref "USB-C") (pin "A12") (pinfunction "GND_A12") (pintype "unspecified"))
      (node (ref "USB-C") (pin "B1") (pinfunction "GND_B1") (pintype "unspecified"))
      (node (ref "USB-C") (pin "B12") (pinfunction "GND_B12") (pintype "unspecified"))
      (node (ref "VGA") (pin "10") (pinfunction "10_10") (pintype "bidirectional"))
      (node (ref "VGA") (pin "5") (pinfunction "5_5") (pintype "bidirectional"))
      (node (ref "VGA") (pin "6") (pinfunction "6_6") (pintype "bidirectional"))
      (node (ref "VGA") (pin "7") (pinfunction "7_7") (pintype "bidirectional"))
      (node (ref "VGA") (pin "8") (pinfunction "8_8") (pintype "bidirectional"))
      (node (ref "VGA") (pin "MH1") (pinfunction "MH1_MH1") (pintype "bidirectional"))
      (node (ref "VGA") (pin "MH2") (pinfunction "MH2_MH2") (pintype "bidirectional"))
      (node (ref "VIDEOMEM") (pin "19") (pinfunction "GND_19") (pintype "unspecified"))
      (node (ref "VIDEOMEM") (pin "39") (pinfunction "OER#_39") (pintype "unspecified"))
      (node (ref "W65C02S") (pin "17") (pinfunction "VSS_17") (pintype "unspecified"))
      (node (ref "W65C02S") (pin "18") (pinfunction "VSS_18") (pintype "unspecified"))
      (node (ref "W65C02S") (pin "39") (pinfunction "VSS_39") (pintype "unspecified"))
      (node (ref "Z80") (pin "26") (pinfunction "GRN_26") (pintype "unspecified"))
    )
    (net (code "107") (name "GREEN") (class "Default")
      (node (ref "FAT-SCUNK") (pin "72") (pinfunction "I/O_72") (pintype "unspecified"))
      (node (ref "U5") (pin "2") (pinfunction "A_2") (pintype "unspecified"))
    )
    (net (code "108") (name "HSP") (class "Default")
      (node (ref "FAT-SCUNK") (pin "98") (pinfunction "I/O_98") (pintype "unspecified"))
      (node (ref "U7") (pin "2") (pinfunction "A_2") (pintype "unspecified"))
    )
    (net (code "109") (name "KCLK") (class "Default")
      (node (ref "ESD5") (pin "2") (pinfunction "2_2") (pintype "unspecified"))
      (node (ref "FAT-CAT") (pin "32") (pinfunction "(OC3B/OC4B/INT0/PTCXY)PD2_32") (pintype "bidirectional"))
      (node (ref "PS/2") (pin "3") (pinfunction "D+_3") (pintype "unspecified"))
    )
    (net (code "110") (name "KDAT") (class "Default")
      (node (ref "ESD4") (pin "1") (pinfunction "1_1") (pintype "unspecified"))
      (node (ref "FAT-CAT") (pin "1") (pinfunction "(OC2B/INT1/PTCXY)PD3_1") (pintype "bidirectional"))
      (node (ref "PS/2") (pin "2") (pinfunction "D-_2") (pintype "unspecified"))
    )
    (net (code "111") (name "LD") (class "Default")
      (node (ref "FAT-CAT") (pin "23") (pinfunction "(MISO1/ADC0/PTCY)PC0_23") (pintype "bidirectional"))
      (node (ref "FAT-SPACER") (pin "32") (pinfunction "I/O_32") (pintype "unspecified"))
    )
    (net (code "112") (name "MCLK") (class "Default")
      (node (ref "R14") (pin "2") (pinfunction "2_2") (pintype "input"))
      (node (ref "U10") (pin "2") (pinfunction "A_2") (pintype "unspecified"))
    )
    (net (code "113") (name "MISO") (class "Default")
      (node (ref "BOOTLD") (pin "5") (pinfunction "5_5") (pintype "unspecified"))
      (node (ref "FAT-CAT") (pin "16") (pinfunction "(MISO0/RXD1/PTCXY)PB4_16") (pintype "bidirectional"))
      (node (ref "R40") (pin "2") (pinfunction "2_2") (pintype "input"))
    )
    (net (code "114") (name "MOSI") (class "Default")
      (node (ref "BOOTLD") (pin "4") (pinfunction "4_4") (pintype "unspecified"))
      (node (ref "FAT-CAT") (pin "15") (pinfunction "(MOSI0/TXD1/OC2A/PTCXY)PB3_15") (pintype "bidirectional"))
      (node (ref "R36") (pin "1") (pinfunction "1_1") (pintype "input"))
    )
    (net (code "115") (name "MREQZ80") (class "Default")
      (node (ref "FAT-SPACER") (pin "6") (pinfunction "I/O_6") (pintype "unspecified"))
      (node (ref "R43") (pin "1") (pinfunction "1_1") (pintype "input"))
      (node (ref "Z80") (pin "15") (pinfunction "MREQ#_15") (pintype "unspecified"))
    )
    (net (code "116") (name "NMIB6502") (class "Default")
      (node (ref "FAT-SPACER") (pin "94") (pinfunction "I/O_94") (pintype "unspecified"))
      (node (ref "R66") (pin "1") (pinfunction "1_1") (pintype "input"))
      (node (ref "W65C02S") (pin "1") (pinfunction "NMIB_1") (pintype "unspecified"))
    )
    (net (code "117") (name "NMIZ80") (class "Default")
      (node (ref "FAT-SPACER") (pin "7") (pinfunction "I/O_7") (pintype "unspecified"))
      (node (ref "R42") (pin "1") (pinfunction "1_1") (pintype "input"))
      (node (ref "Z80") (pin "13") (pinfunction "NMI#_13") (pintype "unspecified"))
    )
    (net (code "118") (name "Net-(BT1-DIR)") (class "Default")
      (node (ref "BT1") (pin "1") (pinfunction "DIR_1") (pintype "unspecified"))
      (node (ref "OR") (pin "4") (pinfunction "Y_4") (pintype "unspecified"))
    )
    (net (code "119") (name "Net-(BUFFER1-1Y2)") (class "Default")
      (node (ref "BUFFER1") (pin "16") (pinfunction "1Y2_16") (pintype "unspecified"))
      (node (ref "R68") (pin "1") (pinfunction "1_1") (pintype "input"))
    )
    (net (code "120") (name "Net-(BUZZER-+)") (class "Default")
      (node (ref "BUZZER") (pin "1") (pinfunction "+_1") (pintype "unspecified"))
      (node (ref "U2") (pin "4") (pinfunction "Y_4") (pintype "unspecified"))
    )
    (net (code "121") (name "Net-(C68-Pad2)") (class "Default")
      (node (ref "C68") (pin "2") (pinfunction "2_2") (pintype "input"))
      (node (ref "D1") (pin "2") (pinfunction "2_2") (pintype "unspecified"))
      (node (ref "EXP1") (pin "3") (pinfunction "3_3") (pintype "unspecified"))
      (node (ref "EXP1") (pin "35") (pinfunction "35_35") (pintype "unspecified"))
      (node (ref "EXP1") (pin "37") (pinfunction "37_37") (pintype "unspecified"))
      (node (ref "F2") (pin "2") (pinfunction "2_2") (pintype "unspecified"))
    )
    (net (code "122") (name "Net-(CHARMEM-R{slash}WR#)") (class "Default")
      (node (ref "CHARMEM") (pin "43") (pinfunction "R/WR#_43") (pintype "unspecified"))
      (node (ref "R16") (pin "1") (pinfunction "1_1") (pintype "input"))
    )
    (net (code "123") (name "Net-(ESD1-Pad2)") (class "Default")
      (node (ref "ESD1") (pin "2") (pinfunction "2_2") (pintype "unspecified"))
      (node (ref "R5") (pin "2") (pinfunction "2_2") (pintype "input"))
      (node (ref "VGA") (pin "1") (pinfunction "1_1") (pintype "bidirectional"))
    )
    (net (code "124") (name "Net-(ESD2-Pad2)") (class "Default")
      (node (ref "ESD2") (pin "2") (pinfunction "2_2") (pintype "unspecified"))
      (node (ref "R6") (pin "2") (pinfunction "2_2") (pintype "input"))
      (node (ref "VGA") (pin "2") (pinfunction "2_2") (pintype "bidirectional"))
    )
    (net (code "125") (name "Net-(ESD3-Pad2)") (class "Default")
      (node (ref "ESD3") (pin "2") (pinfunction "2_2") (pintype "unspecified"))
      (node (ref "R7") (pin "2") (pinfunction "2_2") (pintype "input"))
      (node (ref "VGA") (pin "3") (pinfunction "3_3") (pintype "bidirectional"))
    )
    (net (code "126") (name "Net-(ESD6-Pad1)") (class "Default")
      (node (ref "ESD6") (pin "1") (pinfunction "1_1") (pintype "unspecified"))
      (node (ref "R9") (pin "2") (pinfunction "2_2") (pintype "unspecified"))
      (node (ref "VGA") (pin "13") (pinfunction "13_13") (pintype "bidirectional"))
    )
    (net (code "127") (name "Net-(ESD7-Pad2)") (class "Default")
      (node (ref "ESD7") (pin "2") (pinfunction "2_2") (pintype "unspecified"))
      (node (ref "R10") (pin "2") (pinfunction "2_2") (pintype "unspecified"))
      (node (ref "VGA") (pin "14") (pinfunction "14_14") (pintype "bidirectional"))
    )
    (net (code "128") (name "Net-(FAT-SCUNK-I{slash}O-Pad100)") (class "Default")
      (node (ref "FAT-SCUNK") (pin "100") (pinfunction "I/O_100") (pintype "unspecified"))
      (node (ref "R17") (pin "2") (pinfunction "2_2") (pintype "input"))
    )
    (net (code "129") (name "Net-(FAT-SPACER-I{slash}O-Pad23)") (class "Default")
      (node (ref "FAT-SPACER") (pin "23") (pinfunction "I/O_23") (pintype "unspecified"))
      (node (ref "R25") (pin "2") (pinfunction "2_2") (pintype "input"))
    )
    (net (code "130") (name "Net-(FAT-SPACER-I{slash}O-Pad24)") (class "Default")
      (node (ref "FAT-SPACER") (pin "24") (pinfunction "I/O_24") (pintype "unspecified"))
      (node (ref "R24") (pin "2") (pinfunction "2_2") (pintype "input"))
    )
    (net (code "131") (name "Net-(FAT-SPACER-I{slash}O-Pad25)") (class "Default")
      (node (ref "FAT-SPACER") (pin "25") (pinfunction "I/O_25") (pintype "unspecified"))
      (node (ref "R26") (pin "2") (pinfunction "2_2") (pintype "input"))
    )
    (net (code "132") (name "Net-(FB1-Pad1)") (class "Default")
      (node (ref "FB1") (pin "1") (pinfunction "1_1") (pintype "unspecified"))
      (node (ref "PS/2") (pin "5") (pinfunction "5_5") (pintype "unspecified"))
      (node (ref "PS/2") (pin "6") (pinfunction "6_6") (pintype "unspecified"))
    )
    (net (code "133") (name "Net-(LVLSHF-1A)") (class "Default")
      (node (ref "LVLSHF") (pin "2") (pinfunction "1A_2") (pintype "unspecified"))
      (node (ref "R36") (pin "2") (pinfunction "2_2") (pintype "input"))
    )
    (net (code "134") (name "Net-(LVLSHF-2A)") (class "Default")
      (node (ref "LVLSHF") (pin "5") (pinfunction "2A_5") (pintype "unspecified"))
      (node (ref "R37") (pin "2") (pinfunction "2_2") (pintype "input"))
    )
    (net (code "135") (name "Net-(LVLSHF-3A)") (class "Default")
      (node (ref "LVLSHF") (pin "9") (pinfunction "3A_9") (pintype "unspecified"))
      (node (ref "R39") (pin "1") (pinfunction "1_1") (pintype "input"))
    )
    (net (code "136") (name "Net-(LVLSHF-4A)") (class "Default")
      (node (ref "LVLSHF") (pin "12") (pinfunction "4A_12") (pintype "unspecified"))
      (node (ref "R38") (pin "1") (pinfunction "1_1") (pintype "input"))
    )
    (net (code "137") (name "Net-(LVLSHF-4Y)") (class "Default")
      (node (ref "LVLSHF") (pin "11") (pinfunction "4Y_11") (pintype "unspecified"))
      (node (ref "R40") (pin "1") (pinfunction "1_1") (pintype "input"))
    )
    (net (code "138") (name "Net-(OSC1-OUT)") (class "Default")
      (node (ref "OSC1") (pin "3") (pinfunction "OUT_3") (pintype "input"))
      (node (ref "R12") (pin "1") (pinfunction "1_1") (pintype "input"))
    )
    (net (code "139") (name "Net-(OSC2-OUTPUT)") (class "Default")
      (node (ref "OSC2") (pin "3") (pinfunction "OUTPUT_3") (pintype "unspecified"))
      (node (ref "R14") (pin "1") (pinfunction "1_1") (pintype "input"))
    )
    (net (code "140") (name "Net-(PWR1-A)") (class "Default")
      (node (ref "PWR1") (pin "2") (pinfunction "A_2") (pintype "input"))
      (node (ref "R13") (pin "2") (pinfunction "2_2") (pintype "input"))
    )
    (net (code "141") (name "Net-(Q1-B)") (class "Default")
      (node (ref "Q1") (pin "1") (pinfunction "B_1") (pintype "input"))
      (node (ref "R2") (pin "2") (pinfunction "2_2") (pintype "input"))
    )
    (net (code "142") (name "Net-(Q2-B)") (class "Default")
      (node (ref "Q2") (pin "1") (pinfunction "B_1") (pintype "input"))
      (node (ref "R29") (pin "1") (pinfunction "1_1") (pintype "input"))
    )
    (net (code "143") (name "Net-(U1-A)") (class "Default")
      (node (ref "BUZZ-DIS") (pin "1") (pinfunction "1_1") (pintype "unspecified"))
      (node (ref "R1") (pin "1") (pinfunction "1_1") (pintype "input"))
      (node (ref "U1") (pin "2") (pinfunction "A_2") (pintype "unspecified"))
    )
    (net (code "144") (name "Net-(U1-Y)") (class "Default")
      (node (ref "U1") (pin "4") (pinfunction "Y_4") (pintype "unspecified"))
      (node (ref "U2") (pin "1") (pinfunction "OE_1") (pintype "unspecified"))
    )
    (net (code "145") (name "Net-(U3-Y)") (class "Default")
      (node (ref "R3") (pin "2") (pinfunction "2_2") (pintype "input"))
      (node (ref "U3") (pin "4") (pinfunction "Y_4") (pintype "unspecified"))
    )
    (net (code "146") (name "Net-(U4-Y)") (class "Default")
      (node (ref "R5") (pin "1") (pinfunction "1_1") (pintype "input"))
      (node (ref "U4") (pin "4") (pinfunction "Y_4") (pintype "unspecified"))
    )
    (net (code "147") (name "Net-(U5-Y)") (class "Default")
      (node (ref "R6") (pin "1") (pinfunction "1_1") (pintype "input"))
      (node (ref "U5") (pin "4") (pinfunction "Y_4") (pintype "unspecified"))
    )
    (net (code "148") (name "Net-(U6-Y)") (class "Default")
      (node (ref "R7") (pin "1") (pinfunction "1_1") (pintype "input"))
      (node (ref "U6") (pin "4") (pinfunction "Y_4") (pintype "unspecified"))
    )
    (net (code "149") (name "Net-(U7-Y)") (class "Default")
      (node (ref "R9") (pin "1") (pinfunction "1_1") (pintype "unspecified"))
      (node (ref "U7") (pin "4") (pinfunction "Y_4") (pintype "unspecified"))
    )
    (net (code "150") (name "Net-(U8-Y)") (class "Default")
      (node (ref "R10") (pin "1") (pinfunction "1_1") (pintype "unspecified"))
      (node (ref "U8") (pin "4") (pinfunction "Y_4") (pintype "unspecified"))
    )
    (net (code "151") (name "Net-(U9-A)") (class "Default")
      (node (ref "R26") (pin "1") (pinfunction "1_1") (pintype "input"))
      (node (ref "U9") (pin "2") (pinfunction "A_2") (pintype "unspecified"))
    )
    (net (code "152") (name "Net-(U9-Y)") (class "Default")
      (node (ref "R23") (pin "2") (pinfunction "2_2") (pintype "input"))
      (node (ref "U9") (pin "4") (pinfunction "Y_4") (pintype "unspecified"))
    )
    (net (code "153") (name "Net-(U10-Y)") (class "Default")
      (node (ref "R31") (pin "2") (pinfunction "2_2") (pintype "input"))
      (node (ref "U10") (pin "4") (pinfunction "Y_4") (pintype "unspecified"))
    )
    (net (code "154") (name "Net-(USB-C-CC1)") (class "Default")
      (node (ref "R8") (pin "2") (pinfunction "2_2") (pintype "input"))
      (node (ref "USB-C") (pin "A5") (pinfunction "CC1_A5") (pintype "unspecified"))
    )
    (net (code "155") (name "Net-(USB-C-CC2)") (class "Default")
      (node (ref "R11") (pin "1") (pinfunction "1_1") (pintype "input"))
      (node (ref "USB-C") (pin "B5") (pinfunction "CC2_B5") (pintype "unspecified"))
    )
    (net (code "156") (name "Net-(VIDEOMEM-R{slash}WR#)") (class "Default")
      (node (ref "R15") (pin "1") (pinfunction "1_1") (pintype "input"))
      (node (ref "VIDEOMEM") (pin "43") (pinfunction "R/WR#_43") (pintype "unspecified"))
    )
    (net (code "157") (name "Net-(W65C02S-IRQB)") (class "Default")
      (node (ref "R34") (pin "2") (pinfunction "2_2") (pintype "input"))
      (node (ref "W65C02S") (pin "43") (pinfunction "IRQB_43") (pintype "unspecified"))
    )
    (net (code "158") (name "Net-(W65C02S-RDY)") (class "Default")
      (node (ref "R33") (pin "2") (pinfunction "2_2") (pintype "input"))
      (node (ref "W65C02S") (pin "41") (pinfunction "RDY_41") (pintype "unspecified"))
    )
    (net (code "159") (name "Net-(W65C02S-SOB)") (class "Default")
      (node (ref "R35") (pin "1") (pinfunction "1_1") (pintype "input"))
      (node (ref "W65C02S") (pin "36") (pinfunction "SOB_36") (pintype "unspecified"))
    )
    (net (code "160") (name "Net-(Z80-INT#)") (class "Default")
      (node (ref "R32") (pin "2") (pinfunction "2_2") (pintype "input"))
      (node (ref "Z80") (pin "12") (pinfunction "INT#_12") (pintype "unspecified"))
    )
    (net (code "161") (name "OE") (class "Default")
      (node (ref "CHARMEM") (pin "51") (pinfunction "OEL#_51") (pintype "unspecified"))
      (node (ref "FAT-SPACER") (pin "46") (pinfunction "I/O_46") (pintype "unspecified"))
      (node (ref "HIGH-MEM") (pin "22") (pinfunction "OE#_22") (pintype "unspecified"))
      (node (ref "LOW-MEM") (pin "22") (pinfunction "OE#_22") (pintype "unspecified"))
      (node (ref "R50") (pin "1") (pinfunction "1_1") (pintype "input"))
      (node (ref "VIDEOMEM") (pin "51") (pinfunction "OEL#_51") (pintype "unspecified"))
    )
    (net (code "162") (name "PCLK") (class "Default")
      (node (ref "R12") (pin "2") (pinfunction "2_2") (pintype "input"))
      (node (ref "U3") (pin "2") (pinfunction "A_2") (pintype "unspecified"))
    )
    (net (code "163") (name "RDY6502") (class "Default")
      (node (ref "FAT-SPACER") (pin "97") (pinfunction "I/O_97") (pintype "unspecified"))
      (node (ref "R33") (pin "1") (pinfunction "1_1") (pintype "input"))
      (node (ref "R49") (pin "1") (pinfunction "1_1") (pintype "input"))
    )
    (net (code "164") (name "RDZ80") (class "Default")
      (node (ref "FAT-SPACER") (pin "5") (pinfunction "I/O_5") (pintype "unspecified"))
      (node (ref "R44") (pin "1") (pinfunction "1_1") (pintype "input"))
      (node (ref "Z80") (pin "18") (pinfunction "RD#_18") (pintype "unspecified"))
    )
    (net (code "165") (name "RED") (class "Default")
      (node (ref "FAT-SCUNK") (pin "75") (pinfunction "I/O_75") (pintype "unspecified"))
      (node (ref "U4") (pin "2") (pinfunction "A_2") (pintype "unspecified"))
    )
    (net (code "166") (name "RST6502") (class "Default")
      (node (ref "FAT-SPACER") (pin "96") (pinfunction "I/O_96") (pintype "unspecified"))
      (node (ref "R67") (pin "1") (pinfunction "1_1") (pintype "input"))
      (node (ref "W65C02S") (pin "38") (pinfunction "RESB_38") (pintype "unspecified"))
    )
    (net (code "167") (name "RSTZ80") (class "Default")
      (node (ref "FAT-SPACER") (pin "98") (pinfunction "I/O_98") (pintype "unspecified"))
      (node (ref "R48") (pin "1") (pinfunction "1_1") (pintype "input"))
      (node (ref "Z80") (pin "23") (pinfunction "RESET#_23") (pintype "unspecified"))
    )
    (net (code "168") (name "RWB6502") (class "Default")
      (node (ref "FAT-SPACER") (pin "93") (pinfunction "I/O_93") (pintype "unspecified"))
      (node (ref "R64") (pin "1") (pinfunction "1_1") (pintype "input"))
      (node (ref "W65C02S") (pin "32") (pinfunction "RWB_32") (pintype "unspecified"))
    )
    (net (code "169") (name "RWCAT") (class "Default")
      (node (ref "FAT-CAT") (pin "24") (pinfunction "(SCK1/ADC1/PTCY)PC1_24") (pintype "bidirectional"))
      (node (ref "FAT-SPACER") (pin "31") (pinfunction "I/O_31") (pintype "unspecified"))
      (node (ref "R63") (pin "1") (pinfunction "1_1") (pintype "input"))
    )
    (net (code "170") (name "RWCM") (class "Default")
      (node (ref "CHARMEM") (pin "47") (pinfunction "R/WL#_47") (pintype "unspecified"))
      (node (ref "FAT-SPACER") (pin "49") (pinfunction "I/O_49") (pintype "unspecified"))
      (node (ref "R55") (pin "1") (pinfunction "1_1") (pintype "input"))
    )
    (net (code "171") (name "RWVM") (class "Default")
      (node (ref "FAT-SPACER") (pin "45") (pinfunction "I/O_45") (pintype "unspecified"))
      (node (ref "R61") (pin "1") (pinfunction "1_1") (pintype "input"))
      (node (ref "VIDEOMEM") (pin "47") (pinfunction "R/WL#_47") (pintype "unspecified"))
    )
    (net (code "172") (name "RX") (class "Default")
      (node (ref "FAT-CAT") (pin "30") (pinfunction "(RXD0/OC3A/PTCXY)PD0_30") (pintype "bidirectional"))
      (node (ref "FTDI") (pin "4") (pinfunction "4_4") (pintype "bidirectional"))
    )
    (net (code "173") (name "S-TCK") (class "Default")
      (node (ref "FAT-SCUNK") (pin "62") (pinfunction "I/O/TCK_62") (pintype "unspecified"))
      (node (ref "JTAG-SCUNK") (pin "1") (pinfunction "1_1") (pintype "unspecified"))
    )
    (net (code "174") (name "S-TDI") (class "Default")
      (node (ref "FAT-SCUNK") (pin "4") (pinfunction "I/O/TDI_4") (pintype "unspecified"))
      (node (ref "JTAG-SCUNK") (pin "9") (pinfunction "9_9") (pintype "unspecified"))
      (node (ref "R21") (pin "1") (pinfunction "1_1") (pintype "input"))
    )
    (net (code "175") (name "S-TDO") (class "Default")
      (node (ref "FAT-SCUNK") (pin "73") (pinfunction "I/O/TDO_73") (pintype "unspecified"))
      (node (ref "JTAG-SCUNK") (pin "3") (pinfunction "3_3") (pintype "unspecified"))
    )
    (net (code "176") (name "S-TMS") (class "Default")
      (node (ref "FAT-SCUNK") (pin "15") (pinfunction "I/O/TMS_15") (pintype "unspecified"))
      (node (ref "JTAG-SCUNK") (pin "5") (pinfunction "5_5") (pintype "unspecified"))
      (node (ref "R22") (pin "1") (pinfunction "1_1") (pintype "input"))
    )
    (net (code "177") (name "SBE") (class "Default")
      (node (ref "FAT-SCUNK") (pin "96") (pinfunction "I/O_96") (pintype "unspecified"))
      (node (ref "R2") (pin "1") (pinfunction "1_1") (pintype "input"))
    )
    (net (code "178") (name "SC") (class "Default")
      (node (ref "FAT-CAT") (pin "26") (pinfunction "(ADC3/PTCY)PC3_26") (pintype "bidirectional"))
      (node (ref "FAT-SPACER") (pin "29") (pinfunction "I/O_29") (pintype "unspecified"))
    )
    (net (code "179") (name "SCK") (class "Default")
      (node (ref "BOOTLD") (pin "1") (pinfunction "1_1") (pintype "unspecified"))
      (node (ref "FAT-CAT") (pin "17") (pinfunction "(XCK0/SCK0/PTCXY)PB5_17") (pintype "bidirectional"))
      (node (ref "R37") (pin "1") (pinfunction "1_1") (pintype "input"))
    )
    (net (code "180") (name "SCK_LLS") (class "Default")
      (node (ref "LVLSHF") (pin "6") (pinfunction "2Y_6") (pintype "unspecified"))
      (node (ref "SD") (pin "5") (pinfunction "CLK_5") (pintype "unspecified"))
    )
    (net (code "181") (name "SI") (class "Default")
      (node (ref "FAT-CAT") (pin "28") (pinfunction "(SCL0/ADC5/PTCY)PC5_28") (pintype "bidirectional"))
      (node (ref "FAT-SPACER") (pin "27") (pinfunction "I/O_27") (pintype "unspecified"))
    )
    (net (code "182") (name "SO") (class "Default")
      (node (ref "FAT-CAT") (pin "27") (pinfunction "(SDA0/ADC4/PTCY)PC4_27") (pintype "bidirectional"))
      (node (ref "FAT-SPACER") (pin "28") (pinfunction "I/O_28") (pintype "unspecified"))
    )
    (net (code "183") (name "SOUND") (class "Default")
      (node (ref "FAT-CAT") (pin "2") (pinfunction "(XCK0/T0/PTCXY)PD4_2") (pintype "bidirectional"))
      (node (ref "U2") (pin "2") (pinfunction "A_2") (pintype "unspecified"))
    )
    (net (code "184") (name "SP-TCK") (class "Default")
      (node (ref "FAT-SPACER") (pin "62") (pinfunction "I/O/TCK_62") (pintype "unspecified"))
      (node (ref "JTAG-SPACER") (pin "1") (pinfunction "1_1") (pintype "unspecified"))
    )
    (net (code "185") (name "SP-TDI") (class "Default")
      (node (ref "FAT-SPACER") (pin "4") (pinfunction "I/O/TDI_4") (pintype "unspecified"))
      (node (ref "JTAG-SPACER") (pin "9") (pinfunction "9_9") (pintype "unspecified"))
      (node (ref "R27") (pin "1") (pinfunction "1_1") (pintype "input"))
    )
    (net (code "186") (name "SP-TDO") (class "Default")
      (node (ref "FAT-SPACER") (pin "73") (pinfunction "I/O/TDO_73") (pintype "unspecified"))
      (node (ref "JTAG-SPACER") (pin "3") (pinfunction "3_3") (pintype "unspecified"))
    )
    (net (code "187") (name "SP-TMS") (class "Default")
      (node (ref "FAT-SPACER") (pin "15") (pinfunction "I/O/TMS_15") (pintype "unspecified"))
      (node (ref "JTAG-SPACER") (pin "5") (pinfunction "5_5") (pintype "unspecified"))
      (node (ref "R28") (pin "1") (pinfunction "1_1") (pintype "input"))
    )
    (net (code "188") (name "SPBE") (class "Default")
      (node (ref "FAT-SPACER") (pin "41") (pinfunction "I/0/PD2_41") (pintype "unspecified"))
      (node (ref "R29") (pin "2") (pinfunction "2_2") (pintype "input"))
    )
    (net (code "189") (name "SPRST") (class "Default")
      (node (ref "FAT-SPACER") (pin "22") (pinfunction "I/O_22") (pintype "unspecified"))
      (node (ref "Q2") (pin "3") (pinfunction "C_3") (pintype "input"))
      (node (ref "R30") (pin "1") (pinfunction "1_1") (pintype "input"))
      (node (ref "U10") (pin "1") (pinfunction "OE_1") (pintype "unspecified"))
    )
    (net (code "190") (name "SRST") (class "Default")
      (node (ref "FAT-SCUNK") (pin "76") (pinfunction "I/O_76") (pintype "unspecified"))
      (node (ref "Q1") (pin "3") (pinfunction "C_3") (pintype "input"))
      (node (ref "R4") (pin "1") (pinfunction "1_1") (pintype "input"))
      (node (ref "U3") (pin "1") (pinfunction "OE_1") (pintype "unspecified"))
    )
    (net (code "191") (name "TX") (class "Default")
      (node (ref "FAT-CAT") (pin "31") (pinfunction "(TXD0/OC4A/PTCXY)PD1_31") (pintype "bidirectional"))
      (node (ref "FTDI") (pin "5") (pinfunction "5_5") (pintype "bidirectional"))
    )
    (net (code "192") (name "VBUS") (class "Default")
      (node (ref "CLAMP1") (pin "1") (pinfunction "C_1") (pintype "unspecified"))
      (node (ref "F1") (pin "1") (pinfunction "1_1") (pintype "unspecified"))
      (node (ref "USB-C") (pin "A4") (pinfunction "VBUS_A4") (pintype "unspecified"))
      (node (ref "USB-C") (pin "A9") (pinfunction "VBUS_A9") (pintype "unspecified"))
      (node (ref "USB-C") (pin "B4") (pinfunction "VBUS_B4") (pintype "unspecified"))
      (node (ref "USB-C") (pin "B9") (pinfunction "VBUS_B9") (pintype "unspecified"))
    )
    (net (code "193") (name "VBUSY") (class "Default")
      (node (ref "FAT-SPACER") (pin "42") (pinfunction "I/O_42") (pintype "unspecified"))
      (node (ref "R62") (pin "1") (pinfunction "1_1") (pintype "input"))
      (node (ref "VIDEOMEM") (pin "48") (pinfunction "BUSYL#_48") (pintype "unspecified"))
    )
    (net (code "194") (name "VCC") (class "Default")
      (node (ref "BOOTLD") (pin "2") (pinfunction "2_2") (pintype "unspecified"))
      (node (ref "BT1") (pin "20") (pinfunction "VCC_20") (pintype "unspecified"))
      (node (ref "BT2") (pin "20") (pinfunction "VCC_20") (pintype "unspecified"))
      (node (ref "BT3") (pin "20") (pinfunction "VCC_20") (pintype "unspecified"))
      (node (ref "BUFFER1") (pin "20") (pinfunction "VCC_20") (pintype "unspecified"))
      (node (ref "C1") (pin "2") (pinfunction "2_2") (pintype "input"))
      (node (ref "C10") (pin "1") (pinfunction "+_1") (pintype "bidirectional"))
      (node (ref "C11") (pin "2") (pinfunction "2_2") (pintype "input"))
      (node (ref "C12") (pin "2") (pinfunction "2_2") (pintype "input"))
      (node (ref "C13") (pin "2") (pinfunction "2_2") (pintype "input"))
      (node (ref "C15") (pin "2") (pinfunction "2_2") (pintype "input"))
      (node (ref "C19") (pin "2") (pinfunction "2_2") (pintype "input"))
      (node (ref "C2") (pin "2") (pinfunction "2_2") (pintype "input"))
      (node (ref "C20") (pin "2") (pinfunction "2_2") (pintype "input"))
      (node (ref "C21") (pin "2") (pinfunction "2_2") (pintype "input"))
      (node (ref "C22") (pin "2") (pinfunction "2_2") (pintype "input"))
      (node (ref "C23") (pin "2") (pinfunction "2_2") (pintype "input"))
      (node (ref "C24") (pin "2") (pinfunction "2_2") (pintype "input"))
      (node (ref "C25") (pin "2") (pinfunction "2_2") (pintype "input"))
      (node (ref "C26") (pin "2") (pinfunction "2_2") (pintype "input"))
      (node (ref "C27") (pin "2") (pinfunction "2_2") (pintype "input"))
      (node (ref "C28") (pin "2") (pinfunction "2_2") (pintype "input"))
      (node (ref "C29") (pin "2") (pinfunction "2_2") (pintype "input"))
      (node (ref "C3") (pin "2") (pinfunction "2_2") (pintype "input"))
      (node (ref "C30") (pin "2") (pinfunction "2_2") (pintype "input"))
      (node (ref "C31") (pin "2") (pinfunction "2_2") (pintype "input"))
      (node (ref "C32") (pin "2") (pinfunction "2_2") (pintype "input"))
      (node (ref "C33") (pin "2") (pinfunction "2_2") (pintype "input"))
      (node (ref "C34") (pin "2") (pinfunction "2_2") (pintype "input"))
      (node (ref "C35") (pin "2") (pinfunction "2_2") (pintype "input"))
      (node (ref "C36") (pin "2") (pinfunction "2_2") (pintype "input"))
      (node (ref "C37") (pin "2") (pinfunction "2_2") (pintype "input"))
      (node (ref "C38") (pin "2") (pinfunction "2_2") (pintype "input"))
      (node (ref "C39") (pin "2") (pinfunction "2_2") (pintype "input"))
      (node (ref "C4") (pin "2") (pinfunction "2_2") (pintype "input"))
      (node (ref "C40") (pin "2") (pinfunction "2_2") (pintype "input"))
      (node (ref "C41") (pin "2") (pinfunction "2_2") (pintype "input"))
      (node (ref "C42") (pin "2") (pinfunction "2_2") (pintype "input"))
      (node (ref "C43") (pin "2") (pinfunction "2_2") (pintype "input"))
      (node (ref "C44") (pin "2") (pinfunction "2_2") (pintype "input"))
      (node (ref "C45") (pin "2") (pinfunction "2_2") (pintype "input"))
      (node (ref "C46") (pin "2") (pinfunction "2_2") (pintype "input"))
      (node (ref "C47") (pin "2") (pinfunction "2_2") (pintype "input"))
      (node (ref "C48") (pin "2") (pinfunction "2_2") (pintype "input"))
      (node (ref "C49") (pin "2") (pinfunction "2_2") (pintype "input"))
      (node (ref "C5") (pin "2") (pinfunction "2_2") (pintype "input"))
      (node (ref "C50") (pin "2") (pinfunction "2_2") (pintype "input"))
      (node (ref "C51") (pin "2") (pinfunction "2_2") (pintype "input"))
      (node (ref "C52") (pin "2") (pinfunction "2_2") (pintype "input"))
      (node (ref "C53") (pin "2") (pinfunction "2_2") (pintype "input"))
      (node (ref "C54") (pin "2") (pinfunction "2_2") (pintype "input"))
      (node (ref "C55") (pin "2") (pinfunction "2_2") (pintype "input"))
      (node (ref "C56") (pin "2") (pinfunction "2_2") (pintype "input"))
      (node (ref "C57") (pin "2") (pinfunction "2_2") (pintype "input"))
      (node (ref "C58") (pin "2") (pinfunction "2_2") (pintype "input"))
      (node (ref "C59") (pin "2") (pinfunction "2_2") (pintype "input"))
      (node (ref "C6") (pin "2") (pinfunction "2_2") (pintype "input"))
      (node (ref "C60") (pin "2") (pinfunction "2_2") (pintype "input"))
      (node (ref "C61") (pin "2") (pinfunction "2_2") (pintype "input"))
      (node (ref "C62") (pin "2") (pinfunction "2_2") (pintype "input"))
      (node (ref "C63") (pin "2") (pinfunction "2_2") (pintype "input"))
      (node (ref "C64") (pin "2") (pinfunction "2_2") (pintype "input"))
      (node (ref "C65") (pin "2") (pinfunction "2_2") (pintype "input"))
      (node (ref "C66") (pin "2") (pinfunction "2_2") (pintype "input"))
      (node (ref "C67") (pin "2") (pinfunction "2_2") (pintype "input"))
      (node (ref "C69") (pin "2") (pinfunction "2_2") (pintype "input"))
      (node (ref "C7") (pin "1") (pinfunction "1_1") (pintype "input"))
      (node (ref "C8") (pin "2") (pinfunction "2_2") (pintype "input"))
      (node (ref "C9") (pin "2") (pinfunction "2_2") (pintype "input"))
      (node (ref "CHARMEM") (pin "45") (pinfunction "VCC_45") (pintype "unspecified"))
      (node (ref "F1") (pin "2") (pinfunction "2_2") (pintype "unspecified"))
      (node (ref "F2") (pin "1") (pinfunction "1_1") (pintype "unspecified"))
      (node (ref "FAT-CAT") (pin "18") (pinfunction "AVCC_18") (pintype "bidirectional"))
      (node (ref "FAT-CAT") (pin "4") (pinfunction "VCC_4") (pintype "bidirectional"))
      (node (ref "FAT-CAVIA") (pin "18") (pinfunction "VCCIO_18") (pintype "unspecified"))
      (node (ref "FAT-CAVIA") (pin "3") (pinfunction "VCCIO_3") (pintype "unspecified"))
      (node (ref "FAT-CAVIA") (pin "34") (pinfunction "VCCIO_34") (pintype "unspecified"))
      (node (ref "FAT-CAVIA") (pin "39") (pinfunction "VCCINT_39") (pintype "unspecified"))
      (node (ref "FAT-CAVIA") (pin "51") (pinfunction "VCCIO_51") (pintype "unspecified"))
      (node (ref "FAT-CAVIA") (pin "66") (pinfunction "VCCIO_66") (pintype "unspecified"))
      (node (ref "FAT-CAVIA") (pin "82") (pinfunction "VCCIO_82") (pintype "unspecified"))
      (node (ref "FAT-CAVIA") (pin "91") (pinfunction "VCCINT_91") (pintype "unspecified"))
      (node (ref "FAT-SCUNK") (pin "18") (pinfunction "VCCIO_18") (pintype "unspecified"))
      (node (ref "FAT-SCUNK") (pin "3") (pinfunction "VCCIO_3") (pintype "unspecified"))
      (node (ref "FAT-SCUNK") (pin "34") (pinfunction "VCCIO_34") (pintype "unspecified"))
      (node (ref "FAT-SCUNK") (pin "39") (pinfunction "VCCINT_39") (pintype "unspecified"))
      (node (ref "FAT-SCUNK") (pin "51") (pinfunction "VCCIO_51") (pintype "unspecified"))
      (node (ref "FAT-SCUNK") (pin "66") (pinfunction "VCCIO_66") (pintype "unspecified"))
      (node (ref "FAT-SCUNK") (pin "82") (pinfunction "VCCIO_82") (pintype "unspecified"))
      (node (ref "FAT-SCUNK") (pin "91") (pinfunction "VCCINT_91") (pintype "unspecified"))
      (node (ref "FAT-SPACER") (pin "18") (pinfunction "VCCIO_18") (pintype "unspecified"))
      (node (ref "FAT-SPACER") (pin "3") (pinfunction "VCCIO_3") (pintype "unspecified"))
      (node (ref "FAT-SPACER") (pin "34") (pinfunction "VCCIO_34") (pintype "unspecified"))
      (node (ref "FAT-SPACER") (pin "39") (pinfunction "VCCINT_39") (pintype "unspecified"))
      (node (ref "FAT-SPACER") (pin "51") (pinfunction "VCCIO_51") (pintype "unspecified"))
      (node (ref "FAT-SPACER") (pin "66") (pinfunction "VCCIO_66") (pintype "unspecified"))
      (node (ref "FAT-SPACER") (pin "82") (pinfunction "VCCIO_82") (pintype "unspecified"))
      (node (ref "FAT-SPACER") (pin "91") (pinfunction "VCCINT_91") (pintype "unspecified"))
      (node (ref "FTDI") (pin "3") (pinfunction "3_3") (pintype "bidirectional"))
      (node (ref "HIGH-MEM") (pin "28") (pinfunction "VCC_28") (pintype "unspecified"))
      (node (ref "JTAG-CAVIA") (pin "4") (pinfunction "4_4") (pintype "unspecified"))
      (node (ref "JTAG-SCUNK") (pin "4") (pinfunction "4_4") (pintype "unspecified"))
      (node (ref "JTAG-SPACER") (pin "4") (pinfunction "4_4") (pintype "unspecified"))
      (node (ref "LDO") (pin "3") (pinfunction "IN_3") (pintype "passive"))
      (node (ref "LOW-MEM") (pin "28") (pinfunction "VCC_28") (pintype "unspecified"))
      (node (ref "OR") (pin "5") (pinfunction "VCC_5") (pintype "unspecified"))
      (node (ref "OSC1") (pin "4") (pinfunction "VDD_4") (pintype "input"))
      (node (ref "OSC2") (pin "4") (pinfunction "VDD_4") (pintype "unspecified"))
      (node (ref "PS/2") (pin "1") (pinfunction "VCC_1") (pintype "unspecified"))
      (node (ref "R1") (pin "2") (pinfunction "2_2") (pintype "input"))
      (node (ref "R13") (pin "1") (pinfunction "1_1") (pintype "input"))
      (node (ref "R15") (pin "2") (pinfunction "2_2") (pintype "input"))
      (node (ref "R16") (pin "2") (pinfunction "2_2") (pintype "input"))
      (node (ref "R18") (pin "2") (pinfunction "2_2") (pintype "input"))
      (node (ref "R19") (pin "2") (pinfunction "2_2") (pintype "input"))
      (node (ref "R20") (pin "2") (pinfunction "2_2") (pintype "input"))
      (node (ref "R21") (pin "2") (pinfunction "2_2") (pintype "input"))
      (node (ref "R22") (pin "2") (pinfunction "2_2") (pintype "input"))
      (node (ref "R27") (pin "2") (pinfunction "2_2") (pintype "input"))
      (node (ref "R28") (pin "2") (pinfunction "2_2") (pintype "input"))
      (node (ref "R30") (pin "2") (pinfunction "2_2") (pintype "input"))
      (node (ref "R32") (pin "1") (pinfunction "1_1") (pintype "input"))
      (node (ref "R34") (pin "1") (pinfunction "1_1") (pintype "input"))
      (node (ref "R35") (pin "2") (pinfunction "2_2") (pintype "input"))
      (node (ref "R4") (pin "2") (pinfunction "2_2") (pintype "input"))
      (node (ref "R41") (pin "2") (pinfunction "2_2") (pintype "input"))
      (node (ref "R42") (pin "2") (pinfunction "2_2") (pintype "input"))
      (node (ref "R43") (pin "2") (pinfunction "2_2") (pintype "input"))
      (node (ref "R44") (pin "2") (pinfunction "2_2") (pintype "input"))
      (node (ref "R45") (pin "2") (pinfunction "2_2") (pintype "input"))
      (node (ref "R46") (pin "2") (pinfunction "2_2") (pintype "input"))
      (node (ref "R47") (pin "2") (pinfunction "2_2") (pintype "input"))
      (node (ref "R48") (pin "2") (pinfunction "2_2") (pintype "input"))
      (node (ref "R49") (pin "2") (pinfunction "2_2") (pintype "input"))
      (node (ref "R50") (pin "2") (pinfunction "2_2") (pintype "input"))
      (node (ref "R51") (pin "1") (pinfunction "1_1") (pintype "input"))
      (node (ref "R52") (pin "2") (pinfunction "2_2") (pintype "input"))
      (node (ref "R53") (pin "1") (pinfunction "1_1") (pintype "input"))
      (node (ref "R54") (pin "2") (pinfunction "2_2") (pintype "input"))
      (node (ref "R55") (pin "2") (pinfunction "2_2") (pintype "input"))
      (node (ref "R56") (pin "2") (pinfunction "2_2") (pintype "input"))
      (node (ref "R57") (pin "2") (pinfunction "2_2") (pintype "input"))
      (node (ref "R58") (pin "2") (pinfunction "2_2") (pintype "input"))
      (node (ref "R59") (pin "2") (pinfunction "2_2") (pintype "input"))
      (node (ref "R60") (pin "2") (pinfunction "2_2") (pintype "input"))
      (node (ref "R61") (pin "2") (pinfunction "2_2") (pintype "input"))
      (node (ref "R62") (pin "2") (pinfunction "2_2") (pintype "input"))
      (node (ref "R63") (pin "2") (pinfunction "2_2") (pintype "input"))
      (node (ref "R64") (pin "2") (pinfunction "2_2") (pintype "input"))
      (node (ref "R65") (pin "2") (pinfunction "2_2") (pintype "input"))
      (node (ref "R66") (pin "2") (pinfunction "2_2") (pintype "input"))
      (node (ref "R67") (pin "2") (pinfunction "2_2") (pintype "input"))
      (node (ref "RN1") (pin "1") (pinfunction "1_1") (pintype "input"))
      (node (ref "RN2") (pin "1") (pinfunction "1_1") (pintype "input"))
      (node (ref "RN3") (pin "1") (pinfunction "1_1") (pintype "input"))
      (node (ref "RN4") (pin "5") (pinfunction "5_5") (pintype "input"))
      (node (ref "RN4") (pin "6") (pinfunction "6_6") (pintype "input"))
      (node (ref "RN4") (pin "7") (pinfunction "7_7") (pintype "input"))
      (node (ref "RN4") (pin "8") (pinfunction "8_8") (pintype "input"))
      (node (ref "RN5") (pin "5") (pinfunction "5_5") (pintype "input"))
      (node (ref "RN5") (pin "6") (pinfunction "6_6") (pintype "input"))
      (node (ref "RN5") (pin "7") (pinfunction "7_7") (pintype "input"))
      (node (ref "RN5") (pin "8") (pinfunction "8_8") (pintype "input"))
      (node (ref "U1") (pin "5") (pinfunction "VCC_5") (pintype "unspecified"))
      (node (ref "U10") (pin "5") (pinfunction "VCC_5") (pintype "unspecified"))
      (node (ref "U2") (pin "5") (pinfunction "VCC_5") (pintype "unspecified"))
      (node (ref "U3") (pin "5") (pinfunction "VCC_5") (pintype "unspecified"))
      (node (ref "U4") (pin "5") (pinfunction "VCC_5") (pintype "unspecified"))
      (node (ref "U5") (pin "5") (pinfunction "VCC_5") (pintype "unspecified"))
      (node (ref "U6") (pin "5") (pinfunction "VCC_5") (pintype "unspecified"))
      (node (ref "U7") (pin "5") (pinfunction "VCC_5") (pintype "unspecified"))
      (node (ref "U8") (pin "5") (pinfunction "VCC_5") (pintype "unspecified"))
      (node (ref "U9") (pin "5") (pinfunction "VCC_5") (pintype "unspecified"))
      (node (ref "VIDEOMEM") (pin "45") (pinfunction "VCC_45") (pintype "unspecified"))
      (node (ref "W65C02S") (pin "3") (pinfunction "VDD_3") (pintype "unspecified"))
      (node (ref "W65C02S") (pin "31") (pinfunction "VDD_31") (pintype "unspecified"))
      (node (ref "Z80") (pin "6") (pinfunction "+5V_6") (pintype "unspecified"))
    )
    (net (code "195") (name "VMA0") (class "Default")
      (node (ref "FAT-CAVIA") (pin "9") (pinfunction "I/O_9") (pintype "unspecified"))
      (node (ref "VIDEOMEM") (pin "38") (pinfunction "A0R_38") (pintype "unspecified"))
    )
    (net (code "196") (name "VMA1") (class "Default")
      (node (ref "FAT-CAVIA") (pin "10") (pinfunction "I/O_10") (pintype "unspecified"))
      (node (ref "VIDEOMEM") (pin "37") (pinfunction "A1R_37") (pintype "unspecified"))
    )
    (net (code "197") (name "VMA2") (class "Default")
      (node (ref "FAT-CAVIA") (pin "13") (pinfunction "I/O_13") (pintype "unspecified"))
      (node (ref "VIDEOMEM") (pin "36") (pinfunction "A2R_36") (pintype "unspecified"))
    )
    (net (code "198") (name "VMA3") (class "Default")
      (node (ref "FAT-CAVIA") (pin "14") (pinfunction "I/O_14") (pintype "unspecified"))
      (node (ref "VIDEOMEM") (pin "35") (pinfunction "A3R_35") (pintype "unspecified"))
    )
    (net (code "199") (name "VMA4") (class "Default")
      (node (ref "FAT-CAVIA") (pin "16") (pinfunction "I/O_16") (pintype "unspecified"))
      (node (ref "VIDEOMEM") (pin "34") (pinfunction "A4R_34") (pintype "unspecified"))
    )
    (net (code "200") (name "VMA5") (class "Default")
      (node (ref "FAT-CAVIA") (pin "17") (pinfunction "I/O_17") (pintype "unspecified"))
      (node (ref "VIDEOMEM") (pin "33") (pinfunction "A5R_33") (pintype "unspecified"))
    )
    (net (code "201") (name "VMA6") (class "Default")
      (node (ref "FAT-CAVIA") (pin "19") (pinfunction "I/O_19") (pintype "unspecified"))
      (node (ref "VIDEOMEM") (pin "32") (pinfunction "A6R_32") (pintype "unspecified"))
    )
    (net (code "202") (name "VMA7") (class "Default")
      (node (ref "FAT-CAVIA") (pin "20") (pinfunction "I/O_20") (pintype "unspecified"))
      (node (ref "VIDEOMEM") (pin "31") (pinfunction "A7R_31") (pintype "unspecified"))
    )
    (net (code "203") (name "VMA8") (class "Default")
      (node (ref "FAT-CAVIA") (pin "21") (pinfunction "I/O_21") (pintype "unspecified"))
      (node (ref "VIDEOMEM") (pin "30") (pinfunction "A8R_30") (pintype "unspecified"))
    )
    (net (code "204") (name "VMA9") (class "Default")
      (node (ref "FAT-CAVIA") (pin "23") (pinfunction "I/O_23") (pintype "unspecified"))
      (node (ref "VIDEOMEM") (pin "29") (pinfunction "A9R_29") (pintype "unspecified"))
    )
    (net (code "205") (name "VMA10") (class "Default")
      (node (ref "FAT-CAVIA") (pin "8") (pinfunction "I/O_8") (pintype "unspecified"))
      (node (ref "VIDEOMEM") (pin "40") (pinfunction "A10R_40") (pintype "unspecified"))
    )
    (net (code "206") (name "VSP") (class "Default")
      (node (ref "FAT-SCUNK") (pin "97") (pinfunction "I/O_97") (pintype "unspecified"))
      (node (ref "U8") (pin "2") (pinfunction "A_2") (pintype "unspecified"))
    )
    (net (code "207") (name "WAITZ80") (class "Default")
      (node (ref "FAT-SPACER") (pin "100") (pinfunction "I/O_100") (pintype "unspecified"))
      (node (ref "R46") (pin "1") (pinfunction "1_1") (pintype "input"))
      (node (ref "Z80") (pin "21") (pinfunction "WAIT#_21") (pintype "unspecified"))
    )
    (net (code "208") (name "WEHM") (class "Default")
      (node (ref "FAT-SPACER") (pin "50") (pinfunction "I/O_50") (pintype "unspecified"))
      (node (ref "HIGH-MEM") (pin "27") (pinfunction "WE#_27") (pintype "unspecified"))
      (node (ref "R56") (pin "1") (pinfunction "1_1") (pintype "input"))
    )
    (net (code "209") (name "WELM") (class "Default")
      (node (ref "FAT-SPACER") (pin "53") (pinfunction "I/O_53") (pintype "unspecified"))
      (node (ref "LOW-MEM") (pin "27") (pinfunction "WE#_27") (pintype "unspecified"))
      (node (ref "R58") (pin "1") (pinfunction "1_1") (pintype "input"))
    )
    (net (code "210") (name "WRZ80") (class "Default")
      (node (ref "FAT-SPACER") (pin "2") (pinfunction "I/O_2") (pintype "unspecified"))
      (node (ref "R45") (pin "1") (pinfunction "1_1") (pintype "input"))
      (node (ref "Z80") (pin "19") (pinfunction "WR#_19") (pintype "unspecified"))
    )
    (net (code "211") (name "XA0") (class "Default")
      (node (ref "BT2") (pin "11") (pinfunction "B8_11") (pintype "unspecified"))
      (node (ref "EXP1") (pin "11") (pinfunction "11_11") (pintype "unspecified"))
    )
    (net (code "212") (name "XA1") (class "Default")
      (node (ref "BT2") (pin "12") (pinfunction "B7_12") (pintype "unspecified"))
      (node (ref "EXP1") (pin "12") (pinfunction "12_12") (pintype "unspecified"))
    )
    (net (code "213") (name "XA2") (class "Default")
      (node (ref "BT2") (pin "13") (pinfunction "B6_13") (pintype "unspecified"))
      (node (ref "EXP1") (pin "13") (pinfunction "13_13") (pintype "unspecified"))
    )
    (net (code "214") (name "XA3") (class "Default")
      (node (ref "BT2") (pin "14") (pinfunction "B5_14") (pintype "unspecified"))
      (node (ref "EXP1") (pin "14") (pinfunction "14_14") (pintype "unspecified"))
    )
    (net (code "215") (name "XA4") (class "Default")
      (node (ref "BT2") (pin "15") (pinfunction "B4_15") (pintype "unspecified"))
      (node (ref "EXP1") (pin "15") (pinfunction "15_15") (pintype "unspecified"))
    )
    (net (code "216") (name "XA5") (class "Default")
      (node (ref "BT2") (pin "16") (pinfunction "B3_16") (pintype "unspecified"))
      (node (ref "EXP1") (pin "16") (pinfunction "16_16") (pintype "unspecified"))
    )
    (net (code "217") (name "XA6") (class "Default")
      (node (ref "BT2") (pin "17") (pinfunction "B2_17") (pintype "unspecified"))
      (node (ref "EXP1") (pin "17") (pinfunction "17_17") (pintype "unspecified"))
    )
    (net (code "218") (name "XA7") (class "Default")
      (node (ref "BT2") (pin "18") (pinfunction "B1_18") (pintype "unspecified"))
      (node (ref "EXP1") (pin "18") (pinfunction "18_18") (pintype "unspecified"))
    )
    (net (code "219") (name "XA8") (class "Default")
      (node (ref "BT3") (pin "11") (pinfunction "B8_11") (pintype "unspecified"))
      (node (ref "EXP1") (pin "19") (pinfunction "19_19") (pintype "unspecified"))
    )
    (net (code "220") (name "XA9") (class "Default")
      (node (ref "BT3") (pin "12") (pinfunction "B7_12") (pintype "unspecified"))
      (node (ref "EXP1") (pin "20") (pinfunction "20_20") (pintype "unspecified"))
    )
    (net (code "221") (name "XA10") (class "Default")
      (node (ref "BT3") (pin "13") (pinfunction "B6_13") (pintype "unspecified"))
      (node (ref "EXP1") (pin "21") (pinfunction "21_21") (pintype "unspecified"))
    )
    (net (code "222") (name "XA11") (class "Default")
      (node (ref "BT3") (pin "14") (pinfunction "B5_14") (pintype "unspecified"))
      (node (ref "EXP1") (pin "22") (pinfunction "22_22") (pintype "unspecified"))
    )
    (net (code "223") (name "XA12") (class "Default")
      (node (ref "BT3") (pin "15") (pinfunction "B4_15") (pintype "unspecified"))
      (node (ref "EXP1") (pin "23") (pinfunction "23_23") (pintype "unspecified"))
    )
    (net (code "224") (name "XA13") (class "Default")
      (node (ref "BT3") (pin "16") (pinfunction "B3_16") (pintype "unspecified"))
      (node (ref "EXP1") (pin "24") (pinfunction "24_24") (pintype "unspecified"))
    )
    (net (code "225") (name "XA14") (class "Default")
      (node (ref "BT3") (pin "17") (pinfunction "B2_17") (pintype "unspecified"))
      (node (ref "EXP1") (pin "25") (pinfunction "25_25") (pintype "unspecified"))
    )
    (net (code "226") (name "XA15") (class "Default")
      (node (ref "BT3") (pin "18") (pinfunction "B1_18") (pintype "unspecified"))
      (node (ref "EXP1") (pin "26") (pinfunction "26_26") (pintype "unspecified"))
    )
    (net (code "227") (name "XBUSACK") (class "Default")
      (node (ref "BT2") (pin "1") (pinfunction "DIR_1") (pintype "unspecified"))
      (node (ref "BT3") (pin "1") (pinfunction "DIR_1") (pintype "unspecified"))
      (node (ref "BUFFER1") (pin "6") (pinfunction "1A3_6") (pintype "unspecified"))
      (node (ref "FAT-CAT") (pin "3") (pinfunction "PE0(PTCXY/SDA1/ICP4/ACO)_3") (pintype "bidirectional"))
      (node (ref "FAT-SPACER") (pin "1") (pinfunction "I/O/PD1_1") (pintype "unspecified"))
      (node (ref "OR") (pin "1") (pinfunction "A_1") (pintype "unspecified"))
      (node (ref "R53") (pin "2") (pinfunction "2_2") (pintype "input"))
    )
    (net (code "228") (name "XBUSREQ") (class "Default")
      (node (ref "BUFFER1") (pin "15") (pinfunction "2A3_15") (pintype "unspecified"))
      (node (ref "EXP1") (pin "5") (pinfunction "5_5") (pintype "unspecified"))
      (node (ref "RN4") (pin "1") (pinfunction "1_1") (pintype "input"))
    )
    (net (code "229") (name "XCLK") (class "Default")
      (node (ref "BUFFER1") (pin "4") (pinfunction "1A2_4") (pintype "unspecified"))
      (node (ref "FAT-SPACER") (pin "16") (pinfunction "I/O_16") (pintype "unspecified"))
    )
    (net (code "230") (name "XD0") (class "Default")
      (node (ref "BT1") (pin "11") (pinfunction "B8_11") (pintype "unspecified"))
      (node (ref "EXP1") (pin "27") (pinfunction "27_27") (pintype "unspecified"))
    )
    (net (code "231") (name "XD1") (class "Default")
      (node (ref "BT1") (pin "12") (pinfunction "B7_12") (pintype "unspecified"))
      (node (ref "EXP1") (pin "28") (pinfunction "28_28") (pintype "unspecified"))
    )
    (net (code "232") (name "XD2") (class "Default")
      (node (ref "BT1") (pin "13") (pinfunction "B6_13") (pintype "unspecified"))
      (node (ref "EXP1") (pin "29") (pinfunction "29_29") (pintype "unspecified"))
    )
    (net (code "233") (name "XD3") (class "Default")
      (node (ref "BT1") (pin "14") (pinfunction "B5_14") (pintype "unspecified"))
      (node (ref "EXP1") (pin "30") (pinfunction "30_30") (pintype "unspecified"))
    )
    (net (code "234") (name "XD4") (class "Default")
      (node (ref "BT1") (pin "15") (pinfunction "B4_15") (pintype "unspecified"))
      (node (ref "EXP1") (pin "31") (pinfunction "31_31") (pintype "unspecified"))
    )
    (net (code "235") (name "XD5") (class "Default")
      (node (ref "BT1") (pin "16") (pinfunction "B3_16") (pintype "unspecified"))
      (node (ref "EXP1") (pin "32") (pinfunction "32_32") (pintype "unspecified"))
    )
    (net (code "236") (name "XD6") (class "Default")
      (node (ref "BT1") (pin "17") (pinfunction "B2_17") (pintype "unspecified"))
      (node (ref "EXP1") (pin "33") (pinfunction "33_33") (pintype "unspecified"))
    )
    (net (code "237") (name "XD7") (class "Default")
      (node (ref "BT1") (pin "18") (pinfunction "B1_18") (pintype "unspecified"))
      (node (ref "EXP1") (pin "34") (pinfunction "34_34") (pintype "unspecified"))
    )
    (net (code "238") (name "XE") (class "Default")
      (node (ref "BT1") (pin "19") (pinfunction "OE#_19") (pintype "unspecified"))
      (node (ref "BT2") (pin "19") (pinfunction "OE#_19") (pintype "unspecified"))
      (node (ref "BT3") (pin "19") (pinfunction "OE#_19") (pintype "unspecified"))
      (node (ref "EXP1") (pin "4") (pinfunction "4_4") (pintype "unspecified"))
      (node (ref "FAT-SPACER") (pin "90") (pinfunction "INPUT/OE2/GCLK2_90") (pintype "unspecified"))
      (node (ref "RN5") (pin "1") (pinfunction "1_1") (pintype "input"))
    )
    (net (code "239") (name "XIN") (class "Default")
      (node (ref "BUFFER1") (pin "8") (pinfunction "1A4_8") (pintype "unspecified"))
      (node (ref "EXP1") (pin "39") (pinfunction "39_39") (pintype "unspecified"))
      (node (ref "RN5") (pin "2") (pinfunction "2_2") (pintype "input"))
    )
    (net (code "240") (name "XIRQ") (class "Default")
      (node (ref "BUFFER1") (pin "17") (pinfunction "2A4_17") (pintype "unspecified"))
      (node (ref "EXP1") (pin "8") (pinfunction "8_8") (pintype "unspecified"))
      (node (ref "RN5") (pin "4") (pinfunction "4_4") (pintype "input"))
    )
    (net (code "241") (name "XRD") (class "Default")
      (node (ref "BUFFER1") (pin "13") (pinfunction "2A2_13") (pintype "unspecified"))
      (node (ref "EXP1") (pin "9") (pinfunction "9_9") (pintype "unspecified"))
      (node (ref "RN4") (pin "3") (pinfunction "3_3") (pintype "input"))
    )
    (net (code "242") (name "XSLC") (class "Default")
      (node (ref "BUFFER1") (pin "2") (pinfunction "1A1_2") (pintype "unspecified"))
      (node (ref "FAT-SPACER") (pin "20") (pinfunction "I/O_20") (pintype "unspecified"))
      (node (ref "R51") (pin "2") (pinfunction "2_2") (pintype "input"))
    )
    (net (code "243") (name "XWR") (class "Default")
      (node (ref "BUFFER1") (pin "11") (pinfunction "2A1_11") (pintype "unspecified"))
      (node (ref "EXP1") (pin "10") (pinfunction "10_10") (pintype "unspecified"))
      (node (ref "RN4") (pin "4") (pinfunction "4_4") (pintype "input"))
    )
    (net (code "244") (name "unconnected-(CHARMEM-BUSYR#-Pad42)") (class "Default")
      (node (ref "CHARMEM") (pin "42") (pinfunction "BUSYR#_42") (pintype "unspecified+no_connect"))
    )
    (net (code "245") (name "unconnected-(CHARMEM-INTL#-Pad49)") (class "Default")
      (node (ref "CHARMEM") (pin "49") (pinfunction "INTL#_49") (pintype "unspecified+no_connect"))
    )
    (net (code "246") (name "unconnected-(CHARMEM-INTR#-Pad41)") (class "Default")
      (node (ref "CHARMEM") (pin "41") (pinfunction "INTR#_41") (pintype "unspecified+no_connect"))
    )
    (net (code "247") (name "unconnected-(CHARMEM-N{slash}C-Pad18)") (class "Default")
      (node (ref "CHARMEM") (pin "18") (pinfunction "N/C_18") (pintype "unspecified+no_connect"))
    )
    (net (code "248") (name "unconnected-(CHARMEM-N{slash}C-Pad28)") (class "Default")
      (node (ref "CHARMEM") (pin "28") (pinfunction "N/C_28") (pintype "unspecified+no_connect"))
    )
    (net (code "249") (name "unconnected-(FAT-CAT-(XTAL2{slash}TOSC2)PB7-Pad8)") (class "Default")
      (node (ref "FAT-CAT") (pin "8") (pinfunction "(XTAL2/TOSC2)PB7_8") (pintype "bidirectional+no_connect"))
    )
    (net (code "250") (name "unconnected-(FAT-CAVIA-I{slash}0{slash}GCLK3-Pad85)") (class "Default")
      (node (ref "FAT-CAVIA") (pin "85") (pinfunction "I/0/GCLK3_85") (pintype "unspecified+no_connect"))
    )
    (net (code "251") (name "unconnected-(FAT-CAVIA-I{slash}O-Pad2)") (class "Default")
      (node (ref "FAT-CAVIA") (pin "2") (pinfunction "I/O_2") (pintype "unspecified+no_connect"))
    )
    (net (code "252") (name "unconnected-(FAT-CAVIA-I{slash}O-Pad5)") (class "Default")
      (node (ref "FAT-CAVIA") (pin "5") (pinfunction "I/O_5") (pintype "unspecified+no_connect"))
    )
    (net (code "253") (name "unconnected-(FAT-CAVIA-I{slash}O-Pad7)") (class "Default")
      (node (ref "FAT-CAVIA") (pin "7") (pinfunction "I/O_7") (pintype "unspecified+no_connect"))
    )
    (net (code "254") (name "unconnected-(FAT-CAVIA-I{slash}O-Pad12)") (class "Default")
      (node (ref "FAT-CAVIA") (pin "12") (pinfunction "I/O_12") (pintype "unspecified+no_connect"))
    )
    (net (code "255") (name "unconnected-(FAT-CAVIA-I{slash}O-Pad22)") (class "Default")
      (node (ref "FAT-CAVIA") (pin "22") (pinfunction "I/O_22") (pintype "unspecified+no_connect"))
    )
    (net (code "256") (name "unconnected-(FAT-CAVIA-I{slash}O-Pad37)") (class "Default")
      (node (ref "FAT-CAVIA") (pin "37") (pinfunction "I/O_37") (pintype "unspecified+no_connect"))
    )
    (net (code "257") (name "unconnected-(FAT-CAVIA-I{slash}O-Pad49)") (class "Default")
      (node (ref "FAT-CAVIA") (pin "49") (pinfunction "I/O_49") (pintype "unspecified+no_connect"))
    )
    (net (code "258") (name "unconnected-(FAT-CAVIA-I{slash}O-Pad50)") (class "Default")
      (node (ref "FAT-CAVIA") (pin "50") (pinfunction "I/O_50") (pintype "unspecified+no_connect"))
    )
    (net (code "259") (name "unconnected-(FAT-CAVIA-I{slash}O-Pad52)") (class "Default")
      (node (ref "FAT-CAVIA") (pin "52") (pinfunction "I/O_52") (pintype "unspecified+no_connect"))
    )
    (net (code "260") (name "unconnected-(FAT-CAVIA-I{slash}O-Pad53)") (class "Default")
      (node (ref "FAT-CAVIA") (pin "53") (pinfunction "I/O_53") (pintype "unspecified+no_connect"))
    )
    (net (code "261") (name "unconnected-(FAT-CAVIA-I{slash}O-Pad54)") (class "Default")
      (node (ref "FAT-CAVIA") (pin "54") (pinfunction "I/O_54") (pintype "unspecified+no_connect"))
    )
    (net (code "262") (name "unconnected-(FAT-CAVIA-I{slash}O-Pad55)") (class "Default")
      (node (ref "FAT-CAVIA") (pin "55") (pinfunction "I/O_55") (pintype "unspecified+no_connect"))
    )
    (net (code "263") (name "unconnected-(FAT-CAVIA-I{slash}O-Pad56)") (class "Default")
      (node (ref "FAT-CAVIA") (pin "56") (pinfunction "I/O_56") (pintype "unspecified+no_connect"))
    )
    (net (code "264") (name "unconnected-(FAT-CAVIA-I{slash}O-Pad57)") (class "Default")
      (node (ref "FAT-CAVIA") (pin "57") (pinfunction "I/O_57") (pintype "unspecified+no_connect"))
    )
    (net (code "265") (name "unconnected-(FAT-CAVIA-I{slash}O-Pad58)") (class "Default")
      (node (ref "FAT-CAVIA") (pin "58") (pinfunction "I/O_58") (pintype "unspecified+no_connect"))
    )
    (net (code "266") (name "unconnected-(FAT-CAVIA-I{slash}O-Pad60)") (class "Default")
      (node (ref "FAT-CAVIA") (pin "60") (pinfunction "I/O_60") (pintype "unspecified+no_connect"))
    )
    (net (code "267") (name "unconnected-(FAT-CAVIA-I{slash}O-Pad61)") (class "Default")
      (node (ref "FAT-CAVIA") (pin "61") (pinfunction "I/O_61") (pintype "unspecified+no_connect"))
    )
    (net (code "268") (name "unconnected-(FAT-CAVIA-I{slash}O-Pad67)") (class "Default")
      (node (ref "FAT-CAVIA") (pin "67") (pinfunction "I/O_67") (pintype "unspecified+no_connect"))
    )
    (net (code "269") (name "unconnected-(FAT-CAVIA-I{slash}O-Pad68)") (class "Default")
      (node (ref "FAT-CAVIA") (pin "68") (pinfunction "I/O_68") (pintype "unspecified+no_connect"))
    )
    (net (code "270") (name "unconnected-(FAT-CAVIA-I{slash}O-Pad69)") (class "Default")
      (node (ref "FAT-CAVIA") (pin "69") (pinfunction "I/O_69") (pintype "unspecified+no_connect"))
    )
    (net (code "271") (name "unconnected-(FAT-CAVIA-I{slash}O-Pad70)") (class "Default")
      (node (ref "FAT-CAVIA") (pin "70") (pinfunction "I/O_70") (pintype "unspecified+no_connect"))
    )
    (net (code "272") (name "unconnected-(FAT-CAVIA-I{slash}O-Pad71)") (class "Default")
      (node (ref "FAT-CAVIA") (pin "71") (pinfunction "I/O_71") (pintype "unspecified+no_connect"))
    )
    (net (code "273") (name "unconnected-(FAT-CAVIA-I{slash}O-Pad72)") (class "Default")
      (node (ref "FAT-CAVIA") (pin "72") (pinfunction "I/O_72") (pintype "unspecified+no_connect"))
    )
    (net (code "274") (name "unconnected-(FAT-CAVIA-I{slash}O-Pad79)") (class "Default")
      (node (ref "FAT-CAVIA") (pin "79") (pinfunction "I/O_79") (pintype "unspecified+no_connect"))
    )
    (net (code "275") (name "unconnected-(FAT-CAVIA-I{slash}O-Pad80)") (class "Default")
      (node (ref "FAT-CAVIA") (pin "80") (pinfunction "I/O_80") (pintype "unspecified+no_connect"))
    )
    (net (code "276") (name "unconnected-(FAT-CAVIA-I{slash}O-Pad81)") (class "Default")
      (node (ref "FAT-CAVIA") (pin "81") (pinfunction "I/O_81") (pintype "unspecified+no_connect"))
    )
    (net (code "277") (name "unconnected-(FAT-CAVIA-I{slash}O-Pad83)") (class "Default")
      (node (ref "FAT-CAVIA") (pin "83") (pinfunction "I/O_83") (pintype "unspecified+no_connect"))
    )
    (net (code "278") (name "unconnected-(FAT-CAVIA-I{slash}O-Pad84)") (class "Default")
      (node (ref "FAT-CAVIA") (pin "84") (pinfunction "I/O_84") (pintype "unspecified+no_connect"))
    )
    (net (code "279") (name "unconnected-(FAT-CAVIA-I{slash}O-Pad94)") (class "Default")
      (node (ref "FAT-CAVIA") (pin "94") (pinfunction "I/O_94") (pintype "unspecified+no_connect"))
    )
    (net (code "280") (name "unconnected-(FAT-CAVIA-I{slash}O-Pad96)") (class "Default")
      (node (ref "FAT-CAVIA") (pin "96") (pinfunction "I/O_96") (pintype "unspecified+no_connect"))
    )
    (net (code "281") (name "unconnected-(FAT-CAVIA-I{slash}O-Pad97)") (class "Default")
      (node (ref "FAT-CAVIA") (pin "97") (pinfunction "I/O_97") (pintype "unspecified+no_connect"))
    )
    (net (code "282") (name "unconnected-(FAT-CAVIA-I{slash}O-Pad98)") (class "Default")
      (node (ref "FAT-CAVIA") (pin "98") (pinfunction "I/O_98") (pintype "unspecified+no_connect"))
    )
    (net (code "283") (name "unconnected-(FAT-CAVIA-I{slash}O-Pad99)") (class "Default")
      (node (ref "FAT-CAVIA") (pin "99") (pinfunction "I/O_99") (pintype "unspecified+no_connect"))
    )
    (net (code "284") (name "unconnected-(FAT-CAVIA-I{slash}O-Pad100)") (class "Default")
      (node (ref "FAT-CAVIA") (pin "100") (pinfunction "I/O_100") (pintype "unspecified+no_connect"))
    )
    (net (code "285") (name "unconnected-(FAT-CAVIA-I{slash}O{slash}PD1-Pad1)") (class "Default")
      (node (ref "FAT-CAVIA") (pin "1") (pinfunction "I/O/PD1_1") (pintype "unspecified+no_connect"))
    )
    (net (code "286") (name "unconnected-(FAT-SCUNK-INPUT{slash}GCLR-Pad89)") (class "Default")
      (node (ref "FAT-SCUNK") (pin "89") (pinfunction "INPUT/GCLR_89") (pintype "unspecified+no_connect"))
    )
    (net (code "287") (name "unconnected-(FAT-SCUNK-INPUT{slash}OE1-Pad88)") (class "Default")
      (node (ref "FAT-SCUNK") (pin "88") (pinfunction "INPUT/OE1_88") (pintype "unspecified+no_connect"))
    )
    (net (code "288") (name "unconnected-(FAT-SCUNK-INPUT{slash}OE2{slash}GCLK2-Pad90)") (class "Default")
      (node (ref "FAT-SCUNK") (pin "90") (pinfunction "INPUT/OE2/GCLK2_90") (pintype "unspecified+no_connect"))
    )
    (net (code "289") (name "unconnected-(FAT-SCUNK-I{slash}0{slash}GCLK3-Pad85)") (class "Default")
      (node (ref "FAT-SCUNK") (pin "85") (pinfunction "I/0/GCLK3_85") (pintype "unspecified+no_connect"))
    )
    (net (code "290") (name "unconnected-(FAT-SCUNK-I{slash}0{slash}PD2-Pad41)") (class "Default")
      (node (ref "FAT-SCUNK") (pin "41") (pinfunction "I/0/PD2_41") (pintype "unspecified+no_connect"))
    )
    (net (code "291") (name "unconnected-(FAT-SCUNK-I{slash}O-Pad2)") (class "Default")
      (node (ref "FAT-SCUNK") (pin "2") (pinfunction "I/O_2") (pintype "unspecified+no_connect"))
    )
    (net (code "292") (name "unconnected-(FAT-SCUNK-I{slash}O-Pad5)") (class "Default")
      (node (ref "FAT-SCUNK") (pin "5") (pinfunction "I/O_5") (pintype "unspecified+no_connect"))
    )
    (net (code "293") (name "unconnected-(FAT-SCUNK-I{slash}O-Pad6)") (class "Default")
      (node (ref "FAT-SCUNK") (pin "6") (pinfunction "I/O_6") (pintype "unspecified+no_connect"))
    )
    (net (code "294") (name "unconnected-(FAT-SCUNK-I{slash}O-Pad7)") (class "Default")
      (node (ref "FAT-SCUNK") (pin "7") (pinfunction "I/O_7") (pintype "unspecified+no_connect"))
    )
    (net (code "295") (name "unconnected-(FAT-SCUNK-I{slash}O-Pad8)") (class "Default")
      (node (ref "FAT-SCUNK") (pin "8") (pinfunction "I/O_8") (pintype "unspecified+no_connect"))
    )
    (net (code "296") (name "unconnected-(FAT-SCUNK-I{slash}O-Pad9)") (class "Default")
      (node (ref "FAT-SCUNK") (pin "9") (pinfunction "I/O_9") (pintype "unspecified+no_connect"))
    )
    (net (code "297") (name "unconnected-(FAT-SCUNK-I{slash}O-Pad10)") (class "Default")
      (node (ref "FAT-SCUNK") (pin "10") (pinfunction "I/O_10") (pintype "unspecified+no_connect"))
    )
    (net (code "298") (name "unconnected-(FAT-SCUNK-I{slash}O-Pad12)") (class "Default")
      (node (ref "FAT-SCUNK") (pin "12") (pinfunction "I/O_12") (pintype "unspecified+no_connect"))
    )
    (net (code "299") (name "unconnected-(FAT-SCUNK-I{slash}O-Pad13)") (class "Default")
      (node (ref "FAT-SCUNK") (pin "13") (pinfunction "I/O_13") (pintype "unspecified+no_connect"))
    )
    (net (code "300") (name "unconnected-(FAT-SCUNK-I{slash}O-Pad14)") (class "Default")
      (node (ref "FAT-SCUNK") (pin "14") (pinfunction "I/O_14") (pintype "unspecified+no_connect"))
    )
    (net (code "301") (name "unconnected-(FAT-SCUNK-I{slash}O-Pad16)") (class "Default")
      (node (ref "FAT-SCUNK") (pin "16") (pinfunction "I/O_16") (pintype "unspecified+no_connect"))
    )
    (net (code "302") (name "unconnected-(FAT-SCUNK-I{slash}O-Pad27)") (class "Default")
      (node (ref "FAT-SCUNK") (pin "27") (pinfunction "I/O_27") (pintype "unspecified+no_connect"))
    )
    (net (code "303") (name "unconnected-(FAT-SCUNK-I{slash}O-Pad28)") (class "Default")
      (node (ref "FAT-SCUNK") (pin "28") (pinfunction "I/O_28") (pintype "unspecified+no_connect"))
    )
    (net (code "304") (name "unconnected-(FAT-SCUNK-I{slash}O-Pad29)") (class "Default")
      (node (ref "FAT-SCUNK") (pin "29") (pinfunction "I/O_29") (pintype "unspecified+no_connect"))
    )
    (net (code "305") (name "unconnected-(FAT-SCUNK-I{slash}O-Pad30)") (class "Default")
      (node (ref "FAT-SCUNK") (pin "30") (pinfunction "I/O_30") (pintype "unspecified+no_connect"))
    )
    (net (code "306") (name "unconnected-(FAT-SCUNK-I{slash}O-Pad31)") (class "Default")
      (node (ref "FAT-SCUNK") (pin "31") (pinfunction "I/O_31") (pintype "unspecified+no_connect"))
    )
    (net (code "307") (name "unconnected-(FAT-SCUNK-I{slash}O-Pad32)") (class "Default")
      (node (ref "FAT-SCUNK") (pin "32") (pinfunction "I/O_32") (pintype "unspecified+no_connect"))
    )
    (net (code "308") (name "unconnected-(FAT-SCUNK-I{slash}O-Pad33)") (class "Default")
      (node (ref "FAT-SCUNK") (pin "33") (pinfunction "I/O_33") (pintype "unspecified+no_connect"))
    )
    (net (code "309") (name "unconnected-(FAT-SCUNK-I{slash}O-Pad35)") (class "Default")
      (node (ref "FAT-SCUNK") (pin "35") (pinfunction "I/O_35") (pintype "unspecified+no_connect"))
    )
    (net (code "310") (name "unconnected-(FAT-SCUNK-I{slash}O-Pad36)") (class "Default")
      (node (ref "FAT-SCUNK") (pin "36") (pinfunction "I/O_36") (pintype "unspecified+no_connect"))
    )
    (net (code "311") (name "unconnected-(FAT-SCUNK-I{slash}O-Pad37)") (class "Default")
      (node (ref "FAT-SCUNK") (pin "37") (pinfunction "I/O_37") (pintype "unspecified+no_connect"))
    )
    (net (code "312") (name "unconnected-(FAT-SCUNK-I{slash}O-Pad40)") (class "Default")
      (node (ref "FAT-SCUNK") (pin "40") (pinfunction "I/O_40") (pintype "unspecified+no_connect"))
    )
    (net (code "313") (name "unconnected-(FAT-SCUNK-I{slash}O-Pad44)") (class "Default")
      (node (ref "FAT-SCUNK") (pin "44") (pinfunction "I/O_44") (pintype "unspecified+no_connect"))
    )
    (net (code "314") (name "unconnected-(FAT-SCUNK-I{slash}O-Pad53)") (class "Default")
      (node (ref "FAT-SCUNK") (pin "53") (pinfunction "I/O_53") (pintype "unspecified+no_connect"))
    )
    (net (code "315") (name "unconnected-(FAT-SCUNK-I{slash}O-Pad54)") (class "Default")
      (node (ref "FAT-SCUNK") (pin "54") (pinfunction "I/O_54") (pintype "unspecified+no_connect"))
    )
    (net (code "316") (name "unconnected-(FAT-SCUNK-I{slash}O-Pad55)") (class "Default")
      (node (ref "FAT-SCUNK") (pin "55") (pinfunction "I/O_55") (pintype "unspecified+no_connect"))
    )
    (net (code "317") (name "unconnected-(FAT-SCUNK-I{slash}O-Pad56)") (class "Default")
      (node (ref "FAT-SCUNK") (pin "56") (pinfunction "I/O_56") (pintype "unspecified+no_connect"))
    )
    (net (code "318") (name "unconnected-(FAT-SCUNK-I{slash}O-Pad57)") (class "Default")
      (node (ref "FAT-SCUNK") (pin "57") (pinfunction "I/O_57") (pintype "unspecified+no_connect"))
    )
    (net (code "319") (name "unconnected-(FAT-SCUNK-I{slash}O-Pad58)") (class "Default")
      (node (ref "FAT-SCUNK") (pin "58") (pinfunction "I/O_58") (pintype "unspecified+no_connect"))
    )
    (net (code "320") (name "unconnected-(FAT-SCUNK-I{slash}O-Pad60)") (class "Default")
      (node (ref "FAT-SCUNK") (pin "60") (pinfunction "I/O_60") (pintype "unspecified+no_connect"))
    )
    (net (code "321") (name "unconnected-(FAT-SCUNK-I{slash}O-Pad61)") (class "Default")
      (node (ref "FAT-SCUNK") (pin "61") (pinfunction "I/O_61") (pintype "unspecified+no_connect"))
    )
    (net (code "322") (name "unconnected-(FAT-SCUNK-I{slash}O-Pad63)") (class "Default")
      (node (ref "FAT-SCUNK") (pin "63") (pinfunction "I/O_63") (pintype "unspecified+no_connect"))
    )
    (net (code "323") (name "unconnected-(FAT-SCUNK-I{slash}O-Pad65)") (class "Default")
      (node (ref "FAT-SCUNK") (pin "65") (pinfunction "I/O_65") (pintype "unspecified+no_connect"))
    )
    (net (code "324") (name "unconnected-(FAT-SCUNK-I{slash}O-Pad67)") (class "Default")
      (node (ref "FAT-SCUNK") (pin "67") (pinfunction "I/O_67") (pintype "unspecified+no_connect"))
    )
    (net (code "325") (name "unconnected-(FAT-SCUNK-I{slash}O-Pad77)") (class "Default")
      (node (ref "FAT-SCUNK") (pin "77") (pinfunction "I/O_77") (pintype "unspecified+no_connect"))
    )
    (net (code "326") (name "unconnected-(FAT-SCUNK-I{slash}O-Pad78)") (class "Default")
      (node (ref "FAT-SCUNK") (pin "78") (pinfunction "I/O_78") (pintype "unspecified+no_connect"))
    )
    (net (code "327") (name "unconnected-(FAT-SCUNK-I{slash}O-Pad79)") (class "Default")
      (node (ref "FAT-SCUNK") (pin "79") (pinfunction "I/O_79") (pintype "unspecified+no_connect"))
    )
    (net (code "328") (name "unconnected-(FAT-SCUNK-I{slash}O-Pad80)") (class "Default")
      (node (ref "FAT-SCUNK") (pin "80") (pinfunction "I/O_80") (pintype "unspecified+no_connect"))
    )
    (net (code "329") (name "unconnected-(FAT-SCUNK-I{slash}O-Pad83)") (class "Default")
      (node (ref "FAT-SCUNK") (pin "83") (pinfunction "I/O_83") (pintype "unspecified+no_connect"))
    )
    (net (code "330") (name "unconnected-(FAT-SCUNK-I{slash}O-Pad84)") (class "Default")
      (node (ref "FAT-SCUNK") (pin "84") (pinfunction "I/O_84") (pintype "unspecified+no_connect"))
    )
    (net (code "331") (name "unconnected-(FAT-SCUNK-I{slash}O-Pad92)") (class "Default")
      (node (ref "FAT-SCUNK") (pin "92") (pinfunction "I/O_92") (pintype "unspecified+no_connect"))
    )
    (net (code "332") (name "unconnected-(FAT-SCUNK-I{slash}O-Pad94)") (class "Default")
      (node (ref "FAT-SCUNK") (pin "94") (pinfunction "I/O_94") (pintype "unspecified+no_connect"))
    )
    (net (code "333") (name "unconnected-(FAT-SCUNK-I{slash}O-Pad99)") (class "Default")
      (node (ref "FAT-SCUNK") (pin "99") (pinfunction "I/O_99") (pintype "unspecified+no_connect"))
    )
    (net (code "334") (name "unconnected-(FAT-SCUNK-I{slash}O{slash}PD1-Pad1)") (class "Default")
      (node (ref "FAT-SCUNK") (pin "1") (pinfunction "I/O/PD1_1") (pintype "unspecified+no_connect"))
    )
    (net (code "335") (name "unconnected-(FAT-SPACER-INPUT{slash}GCLR-Pad89)") (class "Default")
      (node (ref "FAT-SPACER") (pin "89") (pinfunction "INPUT/GCLR_89") (pintype "unspecified+no_connect"))
    )
    (net (code "336") (name "unconnected-(FAT-SPACER-INPUT{slash}OE1-Pad88)") (class "Default")
      (node (ref "FAT-SPACER") (pin "88") (pinfunction "INPUT/OE1_88") (pintype "unspecified+no_connect"))
    )
    (net (code "337") (name "unconnected-(FAT-SPACER-I{slash}0{slash}GCLK3-Pad85)") (class "Default")
      (node (ref "FAT-SPACER") (pin "85") (pinfunction "I/0/GCLK3_85") (pintype "unspecified+no_connect"))
    )
    (net (code "338") (name "unconnected-(FAT-SPACER-I{slash}O-Pad8)") (class "Default")
      (node (ref "FAT-SPACER") (pin "8") (pinfunction "I/O_8") (pintype "unspecified+no_connect"))
    )
    (net (code "339") (name "unconnected-(FAT-SPACER-I{slash}O-Pad9)") (class "Default")
      (node (ref "FAT-SPACER") (pin "9") (pinfunction "I/O_9") (pintype "unspecified+no_connect"))
    )
    (net (code "340") (name "unconnected-(FAT-SPACER-I{slash}O-Pad10)") (class "Default")
      (node (ref "FAT-SPACER") (pin "10") (pinfunction "I/O_10") (pintype "unspecified+no_connect"))
    )
    (net (code "341") (name "unconnected-(FAT-SPACER-I{slash}O-Pad12)") (class "Default")
      (node (ref "FAT-SPACER") (pin "12") (pinfunction "I/O_12") (pintype "unspecified+no_connect"))
    )
    (net (code "342") (name "unconnected-(FAT-SPACER-I{slash}O-Pad13)") (class "Default")
      (node (ref "FAT-SPACER") (pin "13") (pinfunction "I/O_13") (pintype "unspecified+no_connect"))
    )
    (net (code "343") (name "unconnected-(FTDI-Pad2)") (class "Default")
      (node (ref "FTDI") (pin "2") (pinfunction "2_2") (pintype "bidirectional+no_connect"))
    )
    (net (code "344") (name "unconnected-(JTAG-CAVIA-Pad6)") (class "Default")
      (node (ref "JTAG-CAVIA") (pin "6") (pinfunction "6_6") (pintype "unspecified+no_connect"))
    )
    (net (code "345") (name "unconnected-(JTAG-CAVIA-Pad7)") (class "Default")
      (node (ref "JTAG-CAVIA") (pin "7") (pinfunction "7_7") (pintype "unspecified+no_connect"))
    )
    (net (code "346") (name "unconnected-(JTAG-CAVIA-Pad8)") (class "Default")
      (node (ref "JTAG-CAVIA") (pin "8") (pinfunction "8_8") (pintype "unspecified+no_connect"))
    )
    (net (code "347") (name "unconnected-(JTAG-SCUNK-Pad6)") (class "Default")
      (node (ref "JTAG-SCUNK") (pin "6") (pinfunction "6_6") (pintype "unspecified+no_connect"))
    )
    (net (code "348") (name "unconnected-(JTAG-SCUNK-Pad7)") (class "Default")
      (node (ref "JTAG-SCUNK") (pin "7") (pinfunction "7_7") (pintype "unspecified+no_connect"))
    )
    (net (code "349") (name "unconnected-(JTAG-SCUNK-Pad8)") (class "Default")
      (node (ref "JTAG-SCUNK") (pin "8") (pinfunction "8_8") (pintype "unspecified+no_connect"))
    )
    (net (code "350") (name "unconnected-(JTAG-SPACER-Pad6)") (class "Default")
      (node (ref "JTAG-SPACER") (pin "6") (pinfunction "6_6") (pintype "unspecified+no_connect"))
    )
    (net (code "351") (name "unconnected-(JTAG-SPACER-Pad7)") (class "Default")
      (node (ref "JTAG-SPACER") (pin "7") (pinfunction "7_7") (pintype "unspecified+no_connect"))
    )
    (net (code "352") (name "unconnected-(JTAG-SPACER-Pad8)") (class "Default")
      (node (ref "JTAG-SPACER") (pin "8") (pinfunction "8_8") (pintype "unspecified+no_connect"))
    )
    (net (code "353") (name "unconnected-(OSC1-OE#-Pad1)") (class "Default")
      (node (ref "OSC1") (pin "1") (pinfunction "OE#_1") (pintype "input+no_connect"))
    )
    (net (code "354") (name "unconnected-(OSC2-Tri-state-Pad1)") (class "Default")
      (node (ref "OSC2") (pin "1") (pinfunction "Tri-state_1") (pintype "unspecified+no_connect"))
    )
    (net (code "355") (name "unconnected-(SD-CD-Pad9)") (class "Default")
      (node (ref "SD") (pin "9") (pinfunction "CD_9") (pintype "unspecified+no_connect"))
    )
    (net (code "356") (name "unconnected-(SD-DAT1-Pad8)") (class "Default")
      (node (ref "SD") (pin "8") (pinfunction "DAT1_8") (pintype "unspecified+no_connect"))
    )
    (net (code "357") (name "unconnected-(SD-DAT2-Pad1)") (class "Default")
      (node (ref "SD") (pin "1") (pinfunction "DAT2_1") (pintype "unspecified+no_connect"))
    )
    (net (code "358") (name "unconnected-(U1-N.C-Pad1)") (class "Default")
      (node (ref "U1") (pin "1") (pinfunction "N.C_1") (pintype "unspecified+no_connect"))
    )
    (net (code "359") (name "unconnected-(USB-C-DN1-PadA7)") (class "Default")
      (node (ref "USB-C") (pin "A7") (pinfunction "DN1_A7") (pintype "unspecified+no_connect"))
    )
    (net (code "360") (name "unconnected-(USB-C-DN2-PadB7)") (class "Default")
      (node (ref "USB-C") (pin "B7") (pinfunction "DN2_B7") (pintype "unspecified+no_connect"))
    )
    (net (code "361") (name "unconnected-(USB-C-DP1-PadA6)") (class "Default")
      (node (ref "USB-C") (pin "A6") (pinfunction "DP1_A6") (pintype "unspecified+no_connect"))
    )
    (net (code "362") (name "unconnected-(USB-C-DP2-PadB6)") (class "Default")
      (node (ref "USB-C") (pin "B6") (pinfunction "DP2_B6") (pintype "unspecified+no_connect"))
    )
    (net (code "363") (name "unconnected-(USB-C-SUB1-PadA8)") (class "Default")
      (node (ref "USB-C") (pin "A8") (pinfunction "SUB1_A8") (pintype "unspecified+no_connect"))
    )
    (net (code "364") (name "unconnected-(USB-C-SUB2-PadB8)") (class "Default")
      (node (ref "USB-C") (pin "B8") (pinfunction "SUB2_B8") (pintype "unspecified+no_connect"))
    )
    (net (code "365") (name "unconnected-(VGA-Pad4)") (class "Default")
      (node (ref "VGA") (pin "4") (pinfunction "4_4") (pintype "bidirectional+no_connect"))
    )
    (net (code "366") (name "unconnected-(VGA-Pad9)") (class "Default")
      (node (ref "VGA") (pin "9") (pinfunction "9_9") (pintype "bidirectional+no_connect"))
    )
    (net (code "367") (name "unconnected-(VGA-Pad11)") (class "Default")
      (node (ref "VGA") (pin "11") (pinfunction "11_11") (pintype "bidirectional+no_connect"))
    )
    (net (code "368") (name "unconnected-(VGA-Pad12)") (class "Default")
      (node (ref "VGA") (pin "12") (pinfunction "12_12") (pintype "bidirectional+no_connect"))
    )
    (net (code "369") (name "unconnected-(VGA-Pad15)") (class "Default")
      (node (ref "VGA") (pin "15") (pinfunction "15_15") (pintype "bidirectional+no_connect"))
    )
    (net (code "370") (name "unconnected-(VIDEOMEM-BUSYR#-Pad42)") (class "Default")
      (node (ref "VIDEOMEM") (pin "42") (pinfunction "BUSYR#_42") (pintype "unspecified+no_connect"))
    )
    (net (code "371") (name "unconnected-(VIDEOMEM-INTL#-Pad49)") (class "Default")
      (node (ref "VIDEOMEM") (pin "49") (pinfunction "INTL#_49") (pintype "unspecified+no_connect"))
    )
    (net (code "372") (name "unconnected-(VIDEOMEM-INTR#-Pad41)") (class "Default")
      (node (ref "VIDEOMEM") (pin "41") (pinfunction "INTR#_41") (pintype "unspecified+no_connect"))
    )
    (net (code "373") (name "unconnected-(VIDEOMEM-N{slash}C-Pad18)") (class "Default")
      (node (ref "VIDEOMEM") (pin "18") (pinfunction "N/C_18") (pintype "unspecified+no_connect"))
    )
    (net (code "374") (name "unconnected-(VIDEOMEM-N{slash}C-Pad28)") (class "Default")
      (node (ref "VIDEOMEM") (pin "28") (pinfunction "N/C_28") (pintype "unspecified+no_connect"))
    )
    (net (code "375") (name "unconnected-(W65C02S-MLB-Pad44)") (class "Default")
      (node (ref "W65C02S") (pin "44") (pinfunction "MLB_44") (pintype "unspecified+no_connect"))
    )
    (net (code "376") (name "unconnected-(W65C02S-NC-Pad6)") (class "Default")
      (node (ref "W65C02S") (pin "6") (pinfunction "NC_6") (pintype "unspecified+no_connect"))
    )
    (net (code "377") (name "unconnected-(W65C02S-NC-Pad33)") (class "Default")
      (node (ref "W65C02S") (pin "33") (pinfunction "NC_33") (pintype "unspecified+no_connect"))
    )
    (net (code "378") (name "unconnected-(W65C02S-PHI1O-Pad42)") (class "Default")
      (node (ref "W65C02S") (pin "42") (pinfunction "PHI1O_42") (pintype "unspecified+no_connect"))
    )
    (net (code "379") (name "unconnected-(W65C02S-PHI2O-Pad37)") (class "Default")
      (node (ref "W65C02S") (pin "37") (pinfunction "PHI2O_37") (pintype "unspecified+no_connect"))
    )
    (net (code "380") (name "unconnected-(W65C02S-SYNC-Pad2)") (class "Default")
      (node (ref "W65C02S") (pin "2") (pinfunction "SYNC_2") (pintype "unspecified+no_connect"))
    )
    (net (code "381") (name "unconnected-(W65C02S-VPB-Pad40)") (class "Default")
      (node (ref "W65C02S") (pin "40") (pinfunction "VPB_40") (pintype "unspecified+no_connect"))
    )
    (net (code "382") (name "unconnected-(Z80-BUSACK#-Pad20)") (class "Default")
      (node (ref "Z80") (pin "20") (pinfunction "BUSACK#_20") (pintype "unspecified+no_connect"))
    )
    (net (code "383") (name "unconnected-(Z80-HALT#-Pad14)") (class "Default")
      (node (ref "Z80") (pin "14") (pinfunction "HALT#_14") (pintype "unspecified+no_connect"))
    )
    (net (code "384") (name "unconnected-(Z80-IORQ#-Pad16)") (class "Default")
      (node (ref "Z80") (pin "16") (pinfunction "IORQ#_16") (pintype "unspecified+no_connect"))
    )
    (net (code "385") (name "unconnected-(Z80-M1#-Pad24)") (class "Default")
      (node (ref "Z80") (pin "24") (pinfunction "M1#_24") (pintype "unspecified+no_connect"))
    )
    (net (code "386") (name "unconnected-(Z80-NC-Pad11)") (class "Default")
      (node (ref "Z80") (pin "11") (pinfunction "NC_11") (pintype "unspecified+no_connect"))
    )
    (net (code "387") (name "unconnected-(Z80-NC-Pad17)") (class "Default")
      (node (ref "Z80") (pin "17") (pinfunction "NC_17") (pintype "unspecified+no_connect"))
    )
    (net (code "388") (name "unconnected-(Z80-NC-Pad33)") (class "Default")
      (node (ref "Z80") (pin "33") (pinfunction "NC_33") (pintype "unspecified+no_connect"))
    )
    (net (code "389") (name "unconnected-(Z80-NC-Pad39)") (class "Default")
      (node (ref "Z80") (pin "39") (pinfunction "NC_39") (pintype "unspecified+no_connect"))
    )
    (net (code "390") (name "unconnected-(Z80-REFH#-Pad25)") (class "Default")
      (node (ref "Z80") (pin "25") (pinfunction "REFH#_25") (pintype "unspecified+no_connect"))
    )
  )
)
